# pc_badge_hrv.net
KiCad netlist of a schematic drawn in EAGLE
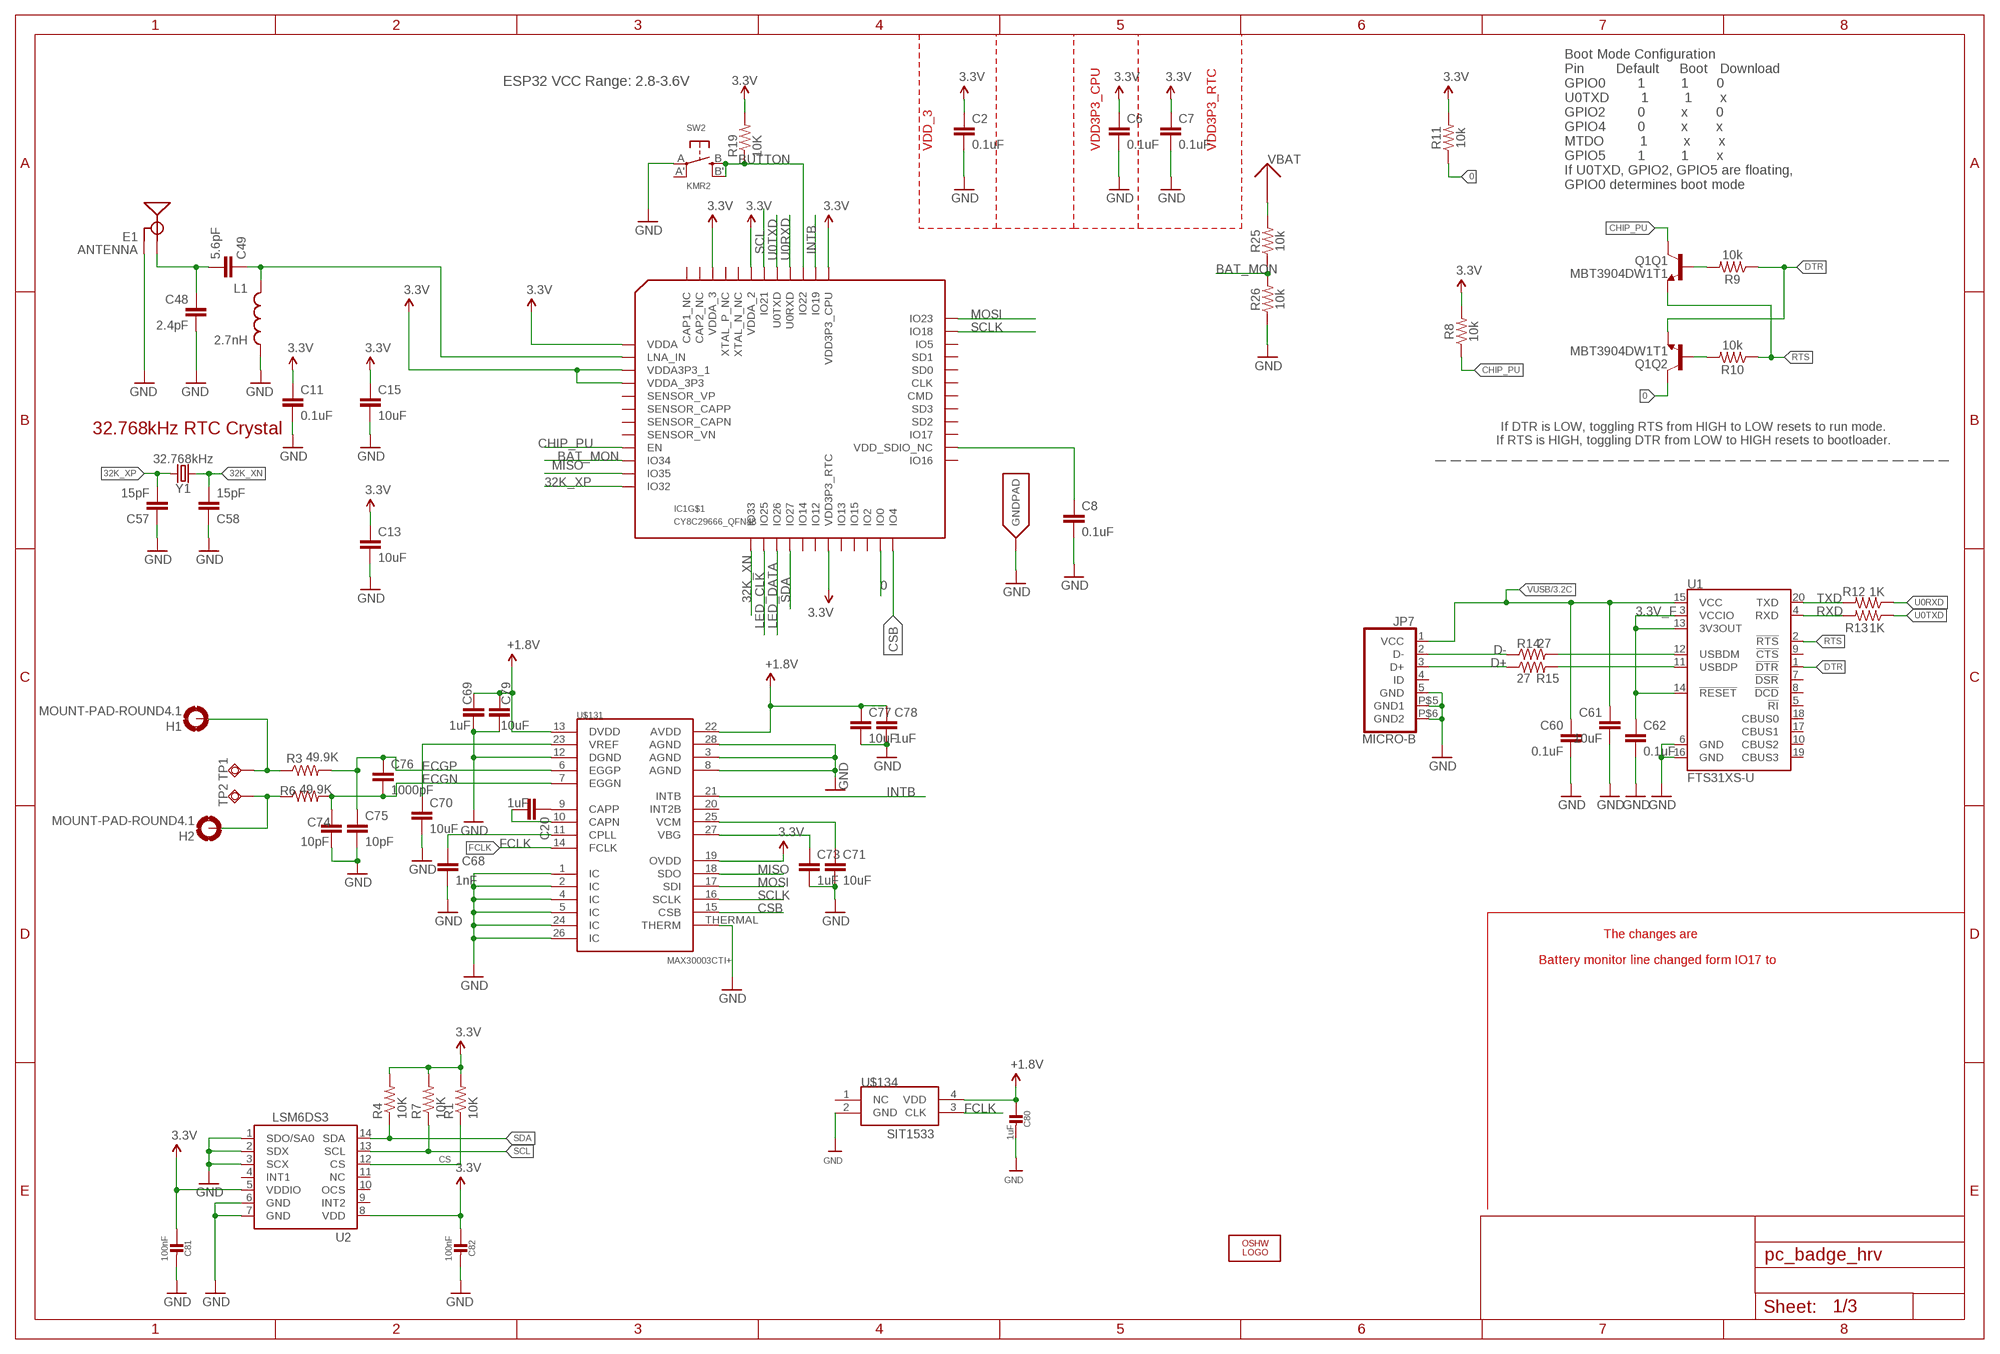
[diagram p0: schematic, sheet 1]
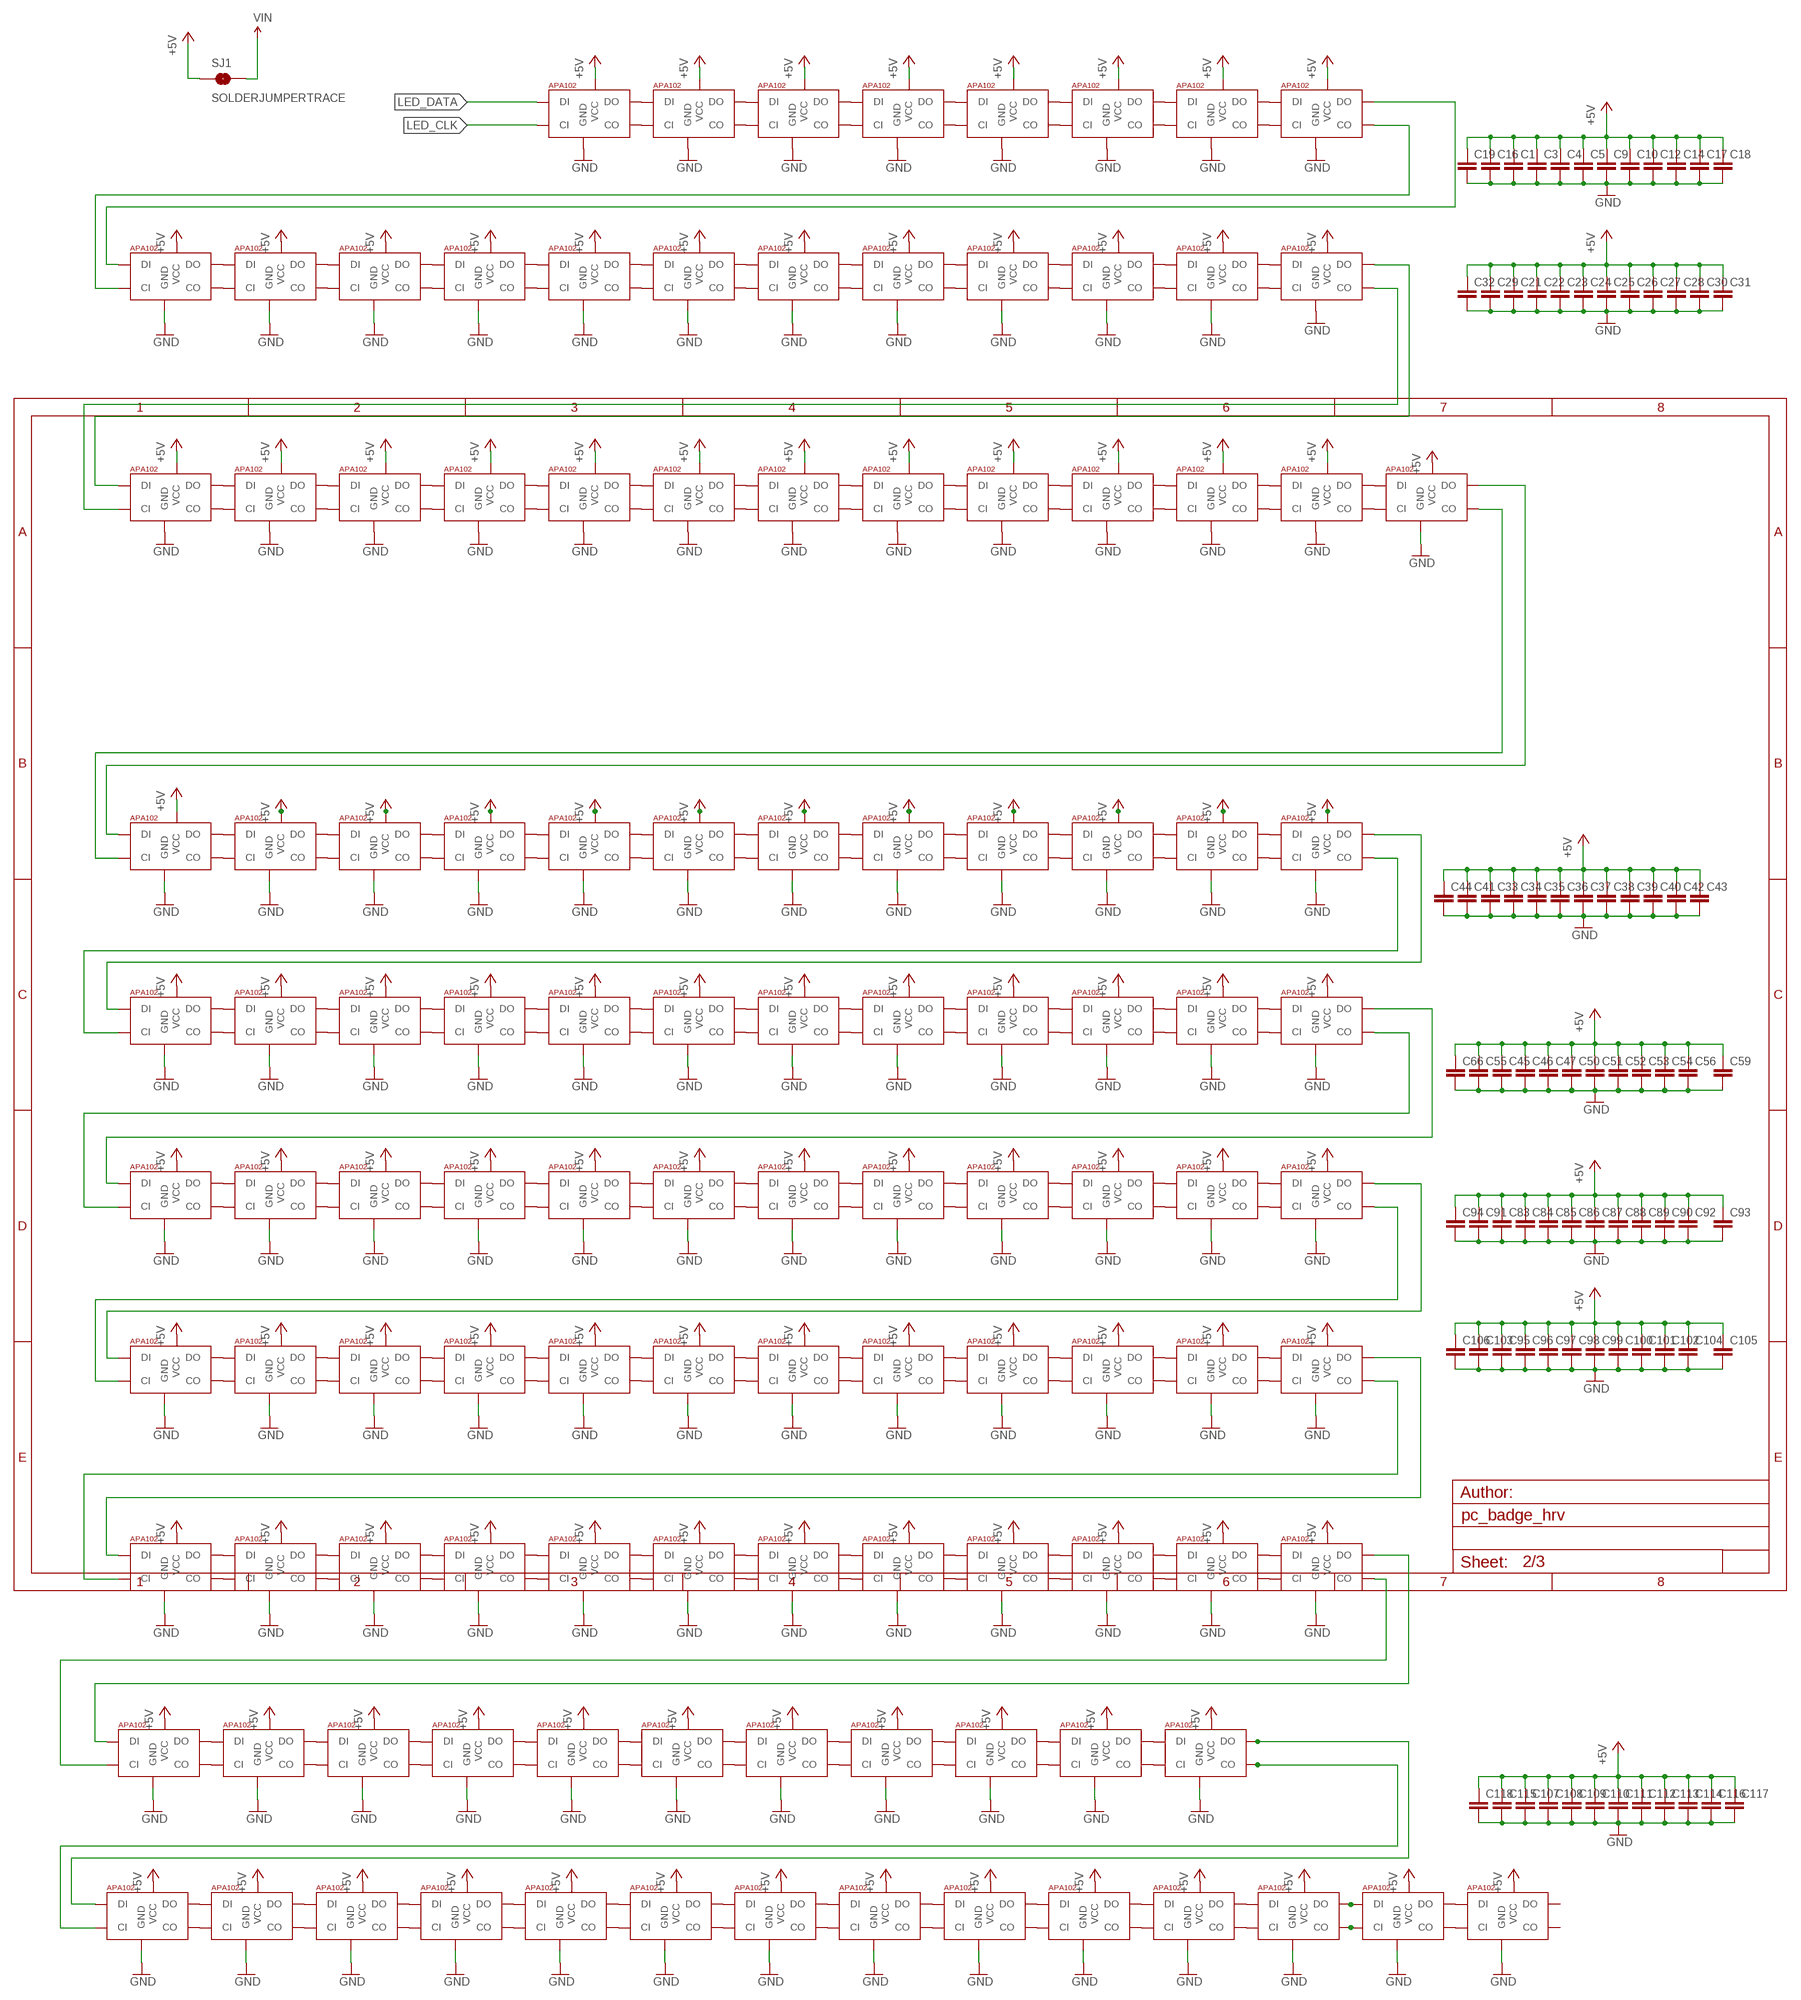
[diagram p1: schematic, sheet 2]
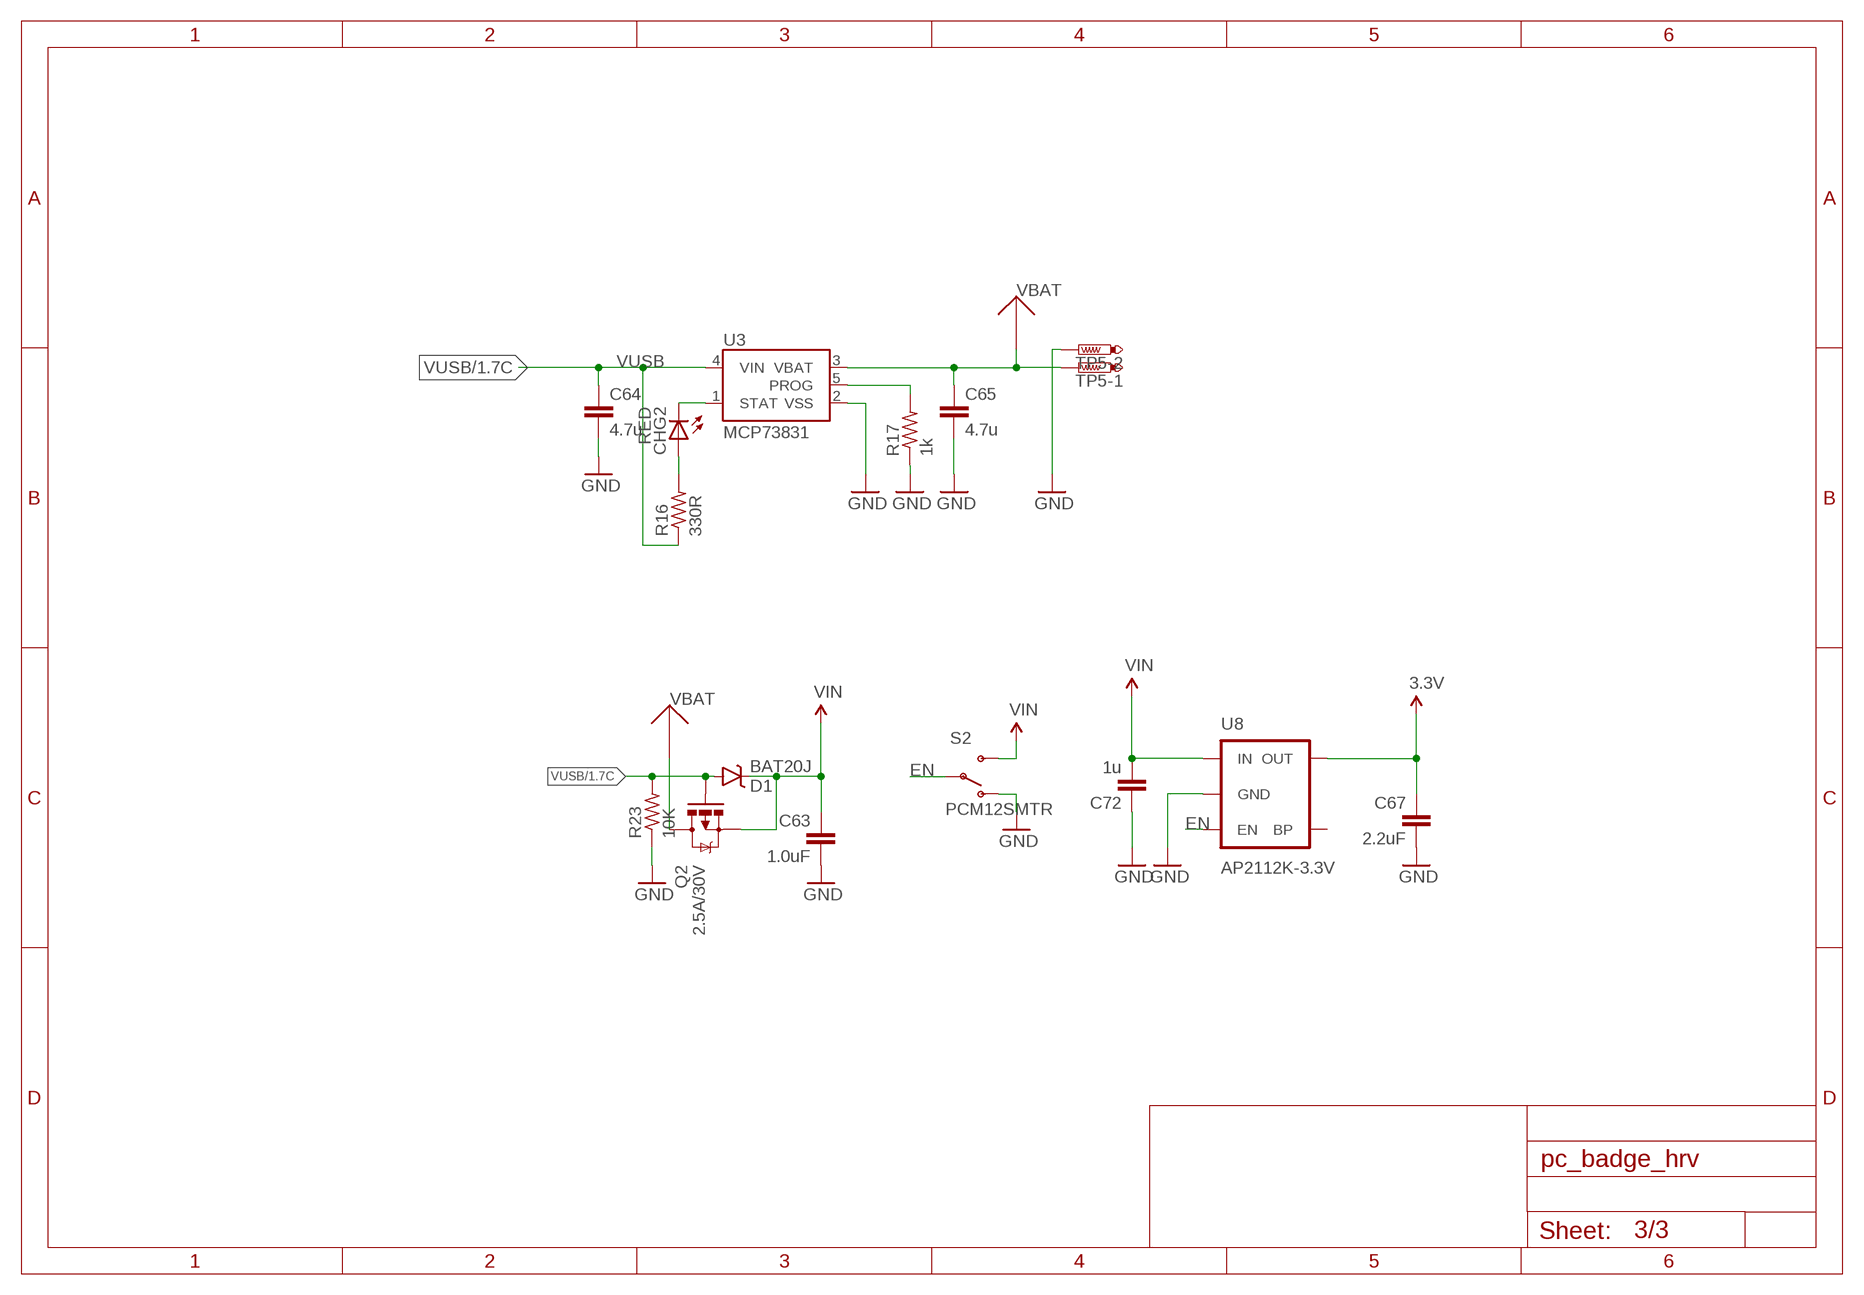
[diagram p2: schematic, sheet 3]

(export (version "E")
  (design (tool "Eeschema 10.0.6"))
  (components
    (comp (ref "C1")
      (value "C-EUC0402K")
      (footprint "eagle-import:C0402K")
      (libsource (lib "eagle-import") (part "C-EUC0402K"))
    )
    (comp (ref "C3")
      (value "C-EUC0402K")
      (footprint "eagle-import:C0402K")
      (libsource (lib "eagle-import") (part "C-EUC0402K"))
    )
    (comp (ref "C4")
      (value "C-EUC0402K")
      (footprint "eagle-import:C0402K")
      (libsource (lib "eagle-import") (part "C-EUC0402K"))
    )
    (comp (ref "C5")
      (value "C-EUC0402K")
      (footprint "eagle-import:C0402K")
      (libsource (lib "eagle-import") (part "C-EUC0402K"))
    )
    (comp (ref "C9")
      (value "C-EUC0402K")
      (footprint "eagle-import:C0402K")
      (libsource (lib "eagle-import") (part "C-EUC0402K"))
    )
    (comp (ref "C10")
      (value "C-EUC0402K")
      (footprint "eagle-import:C0402K")
      (libsource (lib "eagle-import") (part "C-EUC0402K"))
    )
    (comp (ref "C12")
      (value "C-EUC0402K")
      (footprint "eagle-import:C0402K")
      (libsource (lib "eagle-import") (part "C-EUC0402K"))
    )
    (comp (ref "C14")
      (value "C-EUC0402K")
      (footprint "eagle-import:C0402K")
      (libsource (lib "eagle-import") (part "C-EUC0402K"))
    )
    (comp (ref "C16")
      (value "C-EUC0402K")
      (footprint "eagle-import:C0402K")
      (libsource (lib "eagle-import") (part "C-EUC0402K"))
    )
    (comp (ref "C17")
      (value "C-EUC0402K")
      (footprint "eagle-import:C0402K")
      (libsource (lib "eagle-import") (part "C-EUC0402K"))
    )
    (comp (ref "C18")
      (value "C-EUC0402K")
      (footprint "eagle-import:C0402K")
      (libsource (lib "eagle-import") (part "C-EUC0402K"))
    )
    (comp (ref "C19")
      (value "C-EUC0402K")
      (footprint "eagle-import:C0402K")
      (libsource (lib "eagle-import") (part "C-EUC0402K"))
    )
    (comp (ref "C21")
      (value "C-EUC0402K")
      (footprint "eagle-import:C0402K")
      (libsource (lib "eagle-import") (part "C-EUC0402K"))
    )
    (comp (ref "C22")
      (value "C-EUC0402K")
      (footprint "eagle-import:C0402K")
      (libsource (lib "eagle-import") (part "C-EUC0402K"))
    )
    (comp (ref "C23")
      (value "C-EUC0402K")
      (footprint "eagle-import:C0402K")
      (libsource (lib "eagle-import") (part "C-EUC0402K"))
    )
    (comp (ref "C24")
      (value "C-EUC0402K")
      (footprint "eagle-import:C0402K")
      (libsource (lib "eagle-import") (part "C-EUC0402K"))
    )
    (comp (ref "C25")
      (value "C-EUC0402K")
      (footprint "eagle-import:C0402K")
      (libsource (lib "eagle-import") (part "C-EUC0402K"))
    )
    (comp (ref "C26")
      (value "C-EUC0402K")
      (footprint "eagle-import:C0402K")
      (libsource (lib "eagle-import") (part "C-EUC0402K"))
    )
    (comp (ref "C27")
      (value "C-EUC0402K")
      (footprint "eagle-import:C0402K")
      (libsource (lib "eagle-import") (part "C-EUC0402K"))
    )
    (comp (ref "C28")
      (value "C-EUC0402K")
      (footprint "eagle-import:C0402K")
      (libsource (lib "eagle-import") (part "C-EUC0402K"))
    )
    (comp (ref "C29")
      (value "C-EUC0402K")
      (footprint "eagle-import:C0402K")
      (libsource (lib "eagle-import") (part "C-EUC0402K"))
    )
    (comp (ref "C30")
      (value "C-EUC0402K")
      (footprint "eagle-import:C0402K")
      (libsource (lib "eagle-import") (part "C-EUC0402K"))
    )
    (comp (ref "C31")
      (value "C-EUC0402K")
      (footprint "eagle-import:C0402K")
      (libsource (lib "eagle-import") (part "C-EUC0402K"))
    )
    (comp (ref "C32")
      (value "C-EUC0402K")
      (footprint "eagle-import:C0402K")
      (libsource (lib "eagle-import") (part "C-EUC0402K"))
    )
    (comp (ref "C33")
      (value "C-EUC0402K")
      (footprint "eagle-import:C0402K")
      (libsource (lib "eagle-import") (part "C-EUC0402K"))
    )
    (comp (ref "C34")
      (value "C-EUC0402K")
      (footprint "eagle-import:C0402K")
      (libsource (lib "eagle-import") (part "C-EUC0402K"))
    )
    (comp (ref "C35")
      (value "C-EUC0402K")
      (footprint "eagle-import:C0402K")
      (libsource (lib "eagle-import") (part "C-EUC0402K"))
    )
    (comp (ref "C36")
      (value "C-EUC0402K")
      (footprint "eagle-import:C0402K")
      (libsource (lib "eagle-import") (part "C-EUC0402K"))
    )
    (comp (ref "C37")
      (value "C-EUC0402K")
      (footprint "eagle-import:C0402K")
      (libsource (lib "eagle-import") (part "C-EUC0402K"))
    )
    (comp (ref "C38")
      (value "C-EUC0402K")
      (footprint "eagle-import:C0402K")
      (libsource (lib "eagle-import") (part "C-EUC0402K"))
    )
    (comp (ref "C39")
      (value "C-EUC0402K")
      (footprint "eagle-import:C0402K")
      (libsource (lib "eagle-import") (part "C-EUC0402K"))
    )
    (comp (ref "C40")
      (value "C-EUC0402K")
      (footprint "eagle-import:C0402K")
      (libsource (lib "eagle-import") (part "C-EUC0402K"))
    )
    (comp (ref "C41")
      (value "C-EUC0402K")
      (footprint "eagle-import:C0402K")
      (libsource (lib "eagle-import") (part "C-EUC0402K"))
    )
    (comp (ref "C42")
      (value "C-EUC0402K")
      (footprint "eagle-import:C0402K")
      (libsource (lib "eagle-import") (part "C-EUC0402K"))
    )
    (comp (ref "C43")
      (value "C-EUC0402K")
      (footprint "eagle-import:C0402K")
      (libsource (lib "eagle-import") (part "C-EUC0402K"))
    )
    (comp (ref "C44")
      (value "C-EUC0402K")
      (footprint "eagle-import:C0402K")
      (libsource (lib "eagle-import") (part "C-EUC0402K"))
    )
    (comp (ref "C45")
      (value "C-EUC0402K")
      (footprint "eagle-import:C0402K")
      (libsource (lib "eagle-import") (part "C-EUC0402K"))
    )
    (comp (ref "C46")
      (value "C-EUC0402K")
      (footprint "eagle-import:C0402K")
      (libsource (lib "eagle-import") (part "C-EUC0402K"))
    )
    (comp (ref "C47")
      (value "C-EUC0402K")
      (footprint "eagle-import:C0402K")
      (libsource (lib "eagle-import") (part "C-EUC0402K"))
    )
    (comp (ref "C50")
      (value "C-EUC0402K")
      (footprint "eagle-import:C0402K")
      (libsource (lib "eagle-import") (part "C-EUC0402K"))
    )
    (comp (ref "C51")
      (value "C-EUC0402K")
      (footprint "eagle-import:C0402K")
      (libsource (lib "eagle-import") (part "C-EUC0402K"))
    )
    (comp (ref "C52")
      (value "C-EUC0402K")
      (footprint "eagle-import:C0402K")
      (libsource (lib "eagle-import") (part "C-EUC0402K"))
    )
    (comp (ref "C53")
      (value "C-EUC0402K")
      (footprint "eagle-import:C0402K")
      (libsource (lib "eagle-import") (part "C-EUC0402K"))
    )
    (comp (ref "C54")
      (value "C-EUC0402K")
      (footprint "eagle-import:C0402K")
      (libsource (lib "eagle-import") (part "C-EUC0402K"))
    )
    (comp (ref "C55")
      (value "C-EUC0402K")
      (footprint "eagle-import:C0402K")
      (libsource (lib "eagle-import") (part "C-EUC0402K"))
    )
    (comp (ref "C56")
      (value "C-EUC0402K")
      (footprint "eagle-import:C0402K")
      (libsource (lib "eagle-import") (part "C-EUC0402K"))
    )
    (comp (ref "C59")
      (value "C-EUC0402K")
      (footprint "eagle-import:C0402K")
      (libsource (lib "eagle-import") (part "C-EUC0402K"))
    )
    (comp (ref "C66")
      (value "C-EUC0402K")
      (footprint "eagle-import:C0402K")
      (libsource (lib "eagle-import") (part "C-EUC0402K"))
    )
    (comp (ref "C83")
      (value "C-EUC0402K")
      (footprint "eagle-import:C0402K")
      (libsource (lib "eagle-import") (part "C-EUC0402K"))
    )
    (comp (ref "C84")
      (value "C-EUC0402K")
      (footprint "eagle-import:C0402K")
      (libsource (lib "eagle-import") (part "C-EUC0402K"))
    )
    (comp (ref "C85")
      (value "C-EUC0402K")
      (footprint "eagle-import:C0402K")
      (libsource (lib "eagle-import") (part "C-EUC0402K"))
    )
    (comp (ref "C86")
      (value "C-EUC0402K")
      (footprint "eagle-import:C0402K")
      (libsource (lib "eagle-import") (part "C-EUC0402K"))
    )
    (comp (ref "C87")
      (value "C-EUC0402K")
      (footprint "eagle-import:C0402K")
      (libsource (lib "eagle-import") (part "C-EUC0402K"))
    )
    (comp (ref "C88")
      (value "C-EUC0402K")
      (footprint "eagle-import:C0402K")
      (libsource (lib "eagle-import") (part "C-EUC0402K"))
    )
    (comp (ref "C89")
      (value "C-EUC0402K")
      (footprint "eagle-import:C0402K")
      (libsource (lib "eagle-import") (part "C-EUC0402K"))
    )
    (comp (ref "C90")
      (value "C-EUC0402K")
      (footprint "eagle-import:C0402K")
      (libsource (lib "eagle-import") (part "C-EUC0402K"))
    )
    (comp (ref "C91")
      (value "C-EUC0402K")
      (footprint "eagle-import:C0402K")
      (libsource (lib "eagle-import") (part "C-EUC0402K"))
    )
    (comp (ref "C92")
      (value "C-EUC0402K")
      (footprint "eagle-import:C0402K")
      (libsource (lib "eagle-import") (part "C-EUC0402K"))
    )
    (comp (ref "C93")
      (value "C-EUC0402K")
      (footprint "eagle-import:C0402K")
      (libsource (lib "eagle-import") (part "C-EUC0402K"))
    )
    (comp (ref "C94")
      (value "C-EUC0402K")
      (footprint "eagle-import:C0402K")
      (libsource (lib "eagle-import") (part "C-EUC0402K"))
    )
    (comp (ref "C95")
      (value "C-EUC0402K")
      (footprint "eagle-import:C0402K")
      (libsource (lib "eagle-import") (part "C-EUC0402K"))
    )
    (comp (ref "C96")
      (value "C-EUC0402K")
      (footprint "eagle-import:C0402K")
      (libsource (lib "eagle-import") (part "C-EUC0402K"))
    )
    (comp (ref "C97")
      (value "C-EUC0402K")
      (footprint "eagle-import:C0402K")
      (libsource (lib "eagle-import") (part "C-EUC0402K"))
    )
    (comp (ref "C98")
      (value "C-EUC0402K")
      (footprint "eagle-import:C0402K")
      (libsource (lib "eagle-import") (part "C-EUC0402K"))
    )
    (comp (ref "C99")
      (value "C-EUC0402K")
      (footprint "eagle-import:C0402K")
      (libsource (lib "eagle-import") (part "C-EUC0402K"))
    )
    (comp (ref "C100")
      (value "C-EUC0402K")
      (footprint "eagle-import:C0402K")
      (libsource (lib "eagle-import") (part "C-EUC0402K"))
    )
    (comp (ref "C101")
      (value "C-EUC0402K")
      (footprint "eagle-import:C0402K")
      (libsource (lib "eagle-import") (part "C-EUC0402K"))
    )
    (comp (ref "C102")
      (value "C-EUC0402K")
      (footprint "eagle-import:C0402K")
      (libsource (lib "eagle-import") (part "C-EUC0402K"))
    )
    (comp (ref "C103")
      (value "C-EUC0402K")
      (footprint "eagle-import:C0402K")
      (libsource (lib "eagle-import") (part "C-EUC0402K"))
    )
    (comp (ref "C104")
      (value "C-EUC0402K")
      (footprint "eagle-import:C0402K")
      (libsource (lib "eagle-import") (part "C-EUC0402K"))
    )
    (comp (ref "C105")
      (value "C-EUC0402K")
      (footprint "eagle-import:C0402K")
      (libsource (lib "eagle-import") (part "C-EUC0402K"))
    )
    (comp (ref "C106")
      (value "C-EUC0402K")
      (footprint "eagle-import:C0402K")
      (libsource (lib "eagle-import") (part "C-EUC0402K"))
    )
    (comp (ref "C107")
      (value "C-EUC0402K")
      (footprint "eagle-import:C0402K")
      (libsource (lib "eagle-import") (part "C-EUC0402K"))
    )
    (comp (ref "C108")
      (value "C-EUC0402K")
      (footprint "eagle-import:C0402K")
      (libsource (lib "eagle-import") (part "C-EUC0402K"))
    )
    (comp (ref "C109")
      (value "C-EUC0402K")
      (footprint "eagle-import:C0402K")
      (libsource (lib "eagle-import") (part "C-EUC0402K"))
    )
    (comp (ref "C110")
      (value "C-EUC0402K")
      (footprint "eagle-import:C0402K")
      (libsource (lib "eagle-import") (part "C-EUC0402K"))
    )
    (comp (ref "C111")
      (value "C-EUC0402K")
      (footprint "eagle-import:C0402K")
      (libsource (lib "eagle-import") (part "C-EUC0402K"))
    )
    (comp (ref "C112")
      (value "C-EUC0402K")
      (footprint "eagle-import:C0402K")
      (libsource (lib "eagle-import") (part "C-EUC0402K"))
    )
    (comp (ref "C113")
      (value "C-EUC0402K")
      (footprint "eagle-import:C0402K")
      (libsource (lib "eagle-import") (part "C-EUC0402K"))
    )
    (comp (ref "C114")
      (value "C-EUC0402K")
      (footprint "eagle-import:C0402K")
      (libsource (lib "eagle-import") (part "C-EUC0402K"))
    )
    (comp (ref "C115")
      (value "C-EUC0402K")
      (footprint "eagle-import:C0402K")
      (libsource (lib "eagle-import") (part "C-EUC0402K"))
    )
    (comp (ref "C116")
      (value "C-EUC0402K")
      (footprint "eagle-import:C0402K")
      (libsource (lib "eagle-import") (part "C-EUC0402K"))
    )
    (comp (ref "C117")
      (value "C-EUC0402K")
      (footprint "eagle-import:C0402K")
      (libsource (lib "eagle-import") (part "C-EUC0402K"))
    )
    (comp (ref "C118")
      (value "C-EUC0402K")
      (footprint "eagle-import:C0402K")
      (libsource (lib "eagle-import") (part "C-EUC0402K"))
    )
    (comp (ref "SJ1")
      (value "SOLDERJUMPERTRACE")
      (footprint "eagle-import:SJ_2S-TRACE")
      (libsource (lib "eagle-import") (part "SOLDERJUMPERTRACE"))
    )
    (comp (ref "U$9")
      (value "APA1022020")
      (footprint "eagle-import:APA102_2020")
      (libsource (lib "eagle-import") (part "APA1022020"))
    )
    (comp (ref "U$10")
      (value "APA1022020")
      (footprint "eagle-import:APA102_2020")
      (libsource (lib "eagle-import") (part "APA1022020"))
    )
    (comp (ref "U$11")
      (value "APA1022020")
      (footprint "eagle-import:APA102_2020")
      (libsource (lib "eagle-import") (part "APA1022020"))
    )
    (comp (ref "U$12")
      (value "APA1022020")
      (footprint "eagle-import:APA102_2020")
      (libsource (lib "eagle-import") (part "APA1022020"))
    )
    (comp (ref "U$13")
      (value "APA1022020")
      (footprint "eagle-import:APA102_2020")
      (libsource (lib "eagle-import") (part "APA1022020"))
    )
    (comp (ref "U$14")
      (value "APA1022020")
      (footprint "eagle-import:APA102_2020")
      (libsource (lib "eagle-import") (part "APA1022020"))
    )
    (comp (ref "U$15")
      (value "APA1022020")
      (footprint "eagle-import:APA102_2020")
      (libsource (lib "eagle-import") (part "APA1022020"))
    )
    (comp (ref "U$18")
      (value "APA1022020")
      (footprint "eagle-import:APA102_2020")
      (libsource (lib "eagle-import") (part "APA1022020"))
    )
    (comp (ref "U$19")
      (value "APA1022020")
      (footprint "eagle-import:APA102_2020")
      (libsource (lib "eagle-import") (part "APA1022020"))
    )
    (comp (ref "U$20")
      (value "APA1022020")
      (footprint "eagle-import:APA102_2020")
      (libsource (lib "eagle-import") (part "APA1022020"))
    )
    (comp (ref "U$21")
      (value "APA1022020")
      (footprint "eagle-import:APA102_2020")
      (libsource (lib "eagle-import") (part "APA1022020"))
    )
    (comp (ref "U$22")
      (value "APA1022020")
      (footprint "eagle-import:APA102_2020")
      (libsource (lib "eagle-import") (part "APA1022020"))
    )
    (comp (ref "U$24")
      (value "APA1022020")
      (footprint "eagle-import:APA102_2020")
      (libsource (lib "eagle-import") (part "APA1022020"))
    )
    (comp (ref "U$25")
      (value "APA1022020")
      (footprint "eagle-import:APA102_2020")
      (libsource (lib "eagle-import") (part "APA1022020"))
    )
    (comp (ref "U$27")
      (value "APA1022020")
      (footprint "eagle-import:APA102_2020")
      (libsource (lib "eagle-import") (part "APA1022020"))
    )
    (comp (ref "U$28")
      (value "APA1022020")
      (footprint "eagle-import:APA102_2020")
      (libsource (lib "eagle-import") (part "APA1022020"))
    )
    (comp (ref "U$29")
      (value "APA1022020")
      (footprint "eagle-import:APA102_2020")
      (libsource (lib "eagle-import") (part "APA1022020"))
    )
    (comp (ref "U$30")
      (value "APA1022020")
      (footprint "eagle-import:APA102_2020")
      (libsource (lib "eagle-import") (part "APA1022020"))
    )
    (comp (ref "U$31")
      (value "APA1022020")
      (footprint "eagle-import:APA102_2020")
      (libsource (lib "eagle-import") (part "APA1022020"))
    )
    (comp (ref "U$32")
      (value "APA1022020")
      (footprint "eagle-import:APA102_2020")
      (libsource (lib "eagle-import") (part "APA1022020"))
    )
    (comp (ref "U$33")
      (value "APA1022020")
      (footprint "eagle-import:APA102_2020")
      (libsource (lib "eagle-import") (part "APA1022020"))
    )
    (comp (ref "U$34")
      (value "APA1022020")
      (footprint "eagle-import:APA102_2020")
      (libsource (lib "eagle-import") (part "APA1022020"))
    )
    (comp (ref "U$35")
      (value "APA1022020")
      (footprint "eagle-import:APA102_2020")
      (libsource (lib "eagle-import") (part "APA1022020"))
    )
    (comp (ref "U$36")
      (value "APA1022020")
      (footprint "eagle-import:APA102_2020")
      (libsource (lib "eagle-import") (part "APA1022020"))
    )
    (comp (ref "U$37")
      (value "APA1022020")
      (footprint "eagle-import:APA102_2020")
      (libsource (lib "eagle-import") (part "APA1022020"))
    )
    (comp (ref "U$38")
      (value "APA1022020")
      (footprint "eagle-import:APA102_2020")
      (libsource (lib "eagle-import") (part "APA1022020"))
    )
    (comp (ref "U$39")
      (value "APA1022020")
      (footprint "eagle-import:APA102_2020")
      (libsource (lib "eagle-import") (part "APA1022020"))
    )
    (comp (ref "U$40")
      (value "APA1022020")
      (footprint "eagle-import:APA102_2020")
      (libsource (lib "eagle-import") (part "APA1022020"))
    )
    (comp (ref "U$41")
      (value "APA1022020")
      (footprint "eagle-import:APA102_2020")
      (libsource (lib "eagle-import") (part "APA1022020"))
    )
    (comp (ref "U$42")
      (value "APA1022020")
      (footprint "eagle-import:APA102_2020")
      (libsource (lib "eagle-import") (part "APA1022020"))
    )
    (comp (ref "U$43")
      (value "APA1022020")
      (footprint "eagle-import:APA102_2020")
      (libsource (lib "eagle-import") (part "APA1022020"))
    )
    (comp (ref "U$44")
      (value "APA1022020")
      (footprint "eagle-import:APA102_2020")
      (libsource (lib "eagle-import") (part "APA1022020"))
    )
    (comp (ref "U$45")
      (value "APA1022020")
      (footprint "eagle-import:APA102_2020")
      (libsource (lib "eagle-import") (part "APA1022020"))
    )
    (comp (ref "U$46")
      (value "APA1022020")
      (footprint "eagle-import:APA102_2020")
      (libsource (lib "eagle-import") (part "APA1022020"))
    )
    (comp (ref "U$47")
      (value "APA1022020")
      (footprint "eagle-import:APA102_2020")
      (libsource (lib "eagle-import") (part "APA1022020"))
    )
    (comp (ref "U$48")
      (value "APA1022020")
      (footprint "eagle-import:APA102_2020")
      (libsource (lib "eagle-import") (part "APA1022020"))
    )
    (comp (ref "U$49")
      (value "APA1022020")
      (footprint "eagle-import:APA102_2020")
      (libsource (lib "eagle-import") (part "APA1022020"))
    )
    (comp (ref "U$50")
      (value "APA1022020")
      (footprint "eagle-import:APA102_2020")
      (libsource (lib "eagle-import") (part "APA1022020"))
    )
    (comp (ref "U$51")
      (value "APA1022020")
      (footprint "eagle-import:APA102_2020")
      (libsource (lib "eagle-import") (part "APA1022020"))
    )
    (comp (ref "U$52")
      (value "APA1022020")
      (footprint "eagle-import:APA102_2020")
      (libsource (lib "eagle-import") (part "APA1022020"))
    )
    (comp (ref "U$53")
      (value "APA1022020")
      (footprint "eagle-import:APA102_2020")
      (libsource (lib "eagle-import") (part "APA1022020"))
    )
    (comp (ref "U$54")
      (value "APA1022020")
      (footprint "eagle-import:APA102_2020")
      (libsource (lib "eagle-import") (part "APA1022020"))
    )
    (comp (ref "U$55")
      (value "APA1022020")
      (footprint "eagle-import:APA102_2020")
      (libsource (lib "eagle-import") (part "APA1022020"))
    )
    (comp (ref "U$56")
      (value "APA1022020")
      (footprint "eagle-import:APA102_2020")
      (libsource (lib "eagle-import") (part "APA1022020"))
    )
    (comp (ref "U$57")
      (value "APA1022020")
      (footprint "eagle-import:APA102_2020")
      (libsource (lib "eagle-import") (part "APA1022020"))
    )
    (comp (ref "U$58")
      (value "APA1022020")
      (footprint "eagle-import:APA102_2020")
      (libsource (lib "eagle-import") (part "APA1022020"))
    )
    (comp (ref "U$59")
      (value "APA1022020")
      (footprint "eagle-import:APA102_2020")
      (libsource (lib "eagle-import") (part "APA1022020"))
    )
    (comp (ref "U$60")
      (value "APA1022020")
      (footprint "eagle-import:APA102_2020")
      (libsource (lib "eagle-import") (part "APA1022020"))
    )
    (comp (ref "U$61")
      (value "APA1022020")
      (footprint "eagle-import:APA102_2020")
      (libsource (lib "eagle-import") (part "APA1022020"))
    )
    (comp (ref "U$62")
      (value "APA1022020")
      (footprint "eagle-import:APA102_2020")
      (libsource (lib "eagle-import") (part "APA1022020"))
    )
    (comp (ref "U$63")
      (value "APA1022020")
      (footprint "eagle-import:APA102_2020")
      (libsource (lib "eagle-import") (part "APA1022020"))
    )
    (comp (ref "U$64")
      (value "APA1022020")
      (footprint "eagle-import:APA102_2020")
      (libsource (lib "eagle-import") (part "APA1022020"))
    )
    (comp (ref "U$65")
      (value "APA1022020")
      (footprint "eagle-import:APA102_2020")
      (libsource (lib "eagle-import") (part "APA1022020"))
    )
    (comp (ref "U$66")
      (value "APA1022020")
      (footprint "eagle-import:APA102_2020")
      (libsource (lib "eagle-import") (part "APA1022020"))
    )
    (comp (ref "U$67")
      (value "APA1022020")
      (footprint "eagle-import:APA102_2020")
      (libsource (lib "eagle-import") (part "APA1022020"))
    )
    (comp (ref "U$68")
      (value "APA1022020")
      (footprint "eagle-import:APA102_2020")
      (libsource (lib "eagle-import") (part "APA1022020"))
    )
    (comp (ref "U$69")
      (value "APA1022020")
      (footprint "eagle-import:APA102_2020")
      (libsource (lib "eagle-import") (part "APA1022020"))
    )
    (comp (ref "U$70")
      (value "APA1022020")
      (footprint "eagle-import:APA102_2020")
      (libsource (lib "eagle-import") (part "APA1022020"))
    )
    (comp (ref "U$71")
      (value "APA1022020")
      (footprint "eagle-import:APA102_2020")
      (libsource (lib "eagle-import") (part "APA1022020"))
    )
    (comp (ref "U$72")
      (value "APA1022020")
      (footprint "eagle-import:APA102_2020")
      (libsource (lib "eagle-import") (part "APA1022020"))
    )
    (comp (ref "U$73")
      (value "APA1022020")
      (footprint "eagle-import:APA102_2020")
      (libsource (lib "eagle-import") (part "APA1022020"))
    )
    (comp (ref "U$74")
      (value "APA1022020")
      (footprint "eagle-import:APA102_2020")
      (libsource (lib "eagle-import") (part "APA1022020"))
    )
    (comp (ref "U$75")
      (value "APA1022020")
      (footprint "eagle-import:APA102_2020")
      (libsource (lib "eagle-import") (part "APA1022020"))
    )
    (comp (ref "U$76")
      (value "APA1022020")
      (footprint "eagle-import:APA102_2020")
      (libsource (lib "eagle-import") (part "APA1022020"))
    )
    (comp (ref "U$77")
      (value "APA1022020")
      (footprint "eagle-import:APA102_2020")
      (libsource (lib "eagle-import") (part "APA1022020"))
    )
    (comp (ref "U$78")
      (value "APA1022020")
      (footprint "eagle-import:APA102_2020")
      (libsource (lib "eagle-import") (part "APA1022020"))
    )
    (comp (ref "U$79")
      (value "APA1022020")
      (footprint "eagle-import:APA102_2020")
      (libsource (lib "eagle-import") (part "APA1022020"))
    )
    (comp (ref "U$80")
      (value "APA1022020")
      (footprint "eagle-import:APA102_2020")
      (libsource (lib "eagle-import") (part "APA1022020"))
    )
    (comp (ref "U$81")
      (value "APA1022020")
      (footprint "eagle-import:APA102_2020")
      (libsource (lib "eagle-import") (part "APA1022020"))
    )
    (comp (ref "U$82")
      (value "APA1022020")
      (footprint "eagle-import:APA102_2020")
      (libsource (lib "eagle-import") (part "APA1022020"))
    )
    (comp (ref "U$83")
      (value "APA1022020")
      (footprint "eagle-import:APA102_2020")
      (libsource (lib "eagle-import") (part "APA1022020"))
    )
    (comp (ref "U$84")
      (value "APA1022020")
      (footprint "eagle-import:APA102_2020")
      (libsource (lib "eagle-import") (part "APA1022020"))
    )
    (comp (ref "U$85")
      (value "APA1022020")
      (footprint "eagle-import:APA102_2020")
      (libsource (lib "eagle-import") (part "APA1022020"))
    )
    (comp (ref "U$86")
      (value "APA1022020")
      (footprint "eagle-import:APA102_2020")
      (libsource (lib "eagle-import") (part "APA1022020"))
    )
    (comp (ref "U$87")
      (value "APA1022020")
      (footprint "eagle-import:APA102_2020")
      (libsource (lib "eagle-import") (part "APA1022020"))
    )
    (comp (ref "U$88")
      (value "APA1022020")
      (footprint "eagle-import:APA102_2020")
      (libsource (lib "eagle-import") (part "APA1022020"))
    )
    (comp (ref "U$89")
      (value "APA1022020")
      (footprint "eagle-import:APA102_2020")
      (libsource (lib "eagle-import") (part "APA1022020"))
    )
    (comp (ref "U$90")
      (value "APA1022020")
      (footprint "eagle-import:APA102_2020")
      (libsource (lib "eagle-import") (part "APA1022020"))
    )
    (comp (ref "U$91")
      (value "APA1022020")
      (footprint "eagle-import:APA102_2020")
      (libsource (lib "eagle-import") (part "APA1022020"))
    )
    (comp (ref "U$92")
      (value "APA1022020")
      (footprint "eagle-import:APA102_2020")
      (libsource (lib "eagle-import") (part "APA1022020"))
    )
    (comp (ref "U$93")
      (value "APA1022020")
      (footprint "eagle-import:APA102_2020")
      (libsource (lib "eagle-import") (part "APA1022020"))
    )
    (comp (ref "U$94")
      (value "APA1022020")
      (footprint "eagle-import:APA102_2020")
      (libsource (lib "eagle-import") (part "APA1022020"))
    )
    (comp (ref "U$95")
      (value "APA1022020")
      (footprint "eagle-import:APA102_2020")
      (libsource (lib "eagle-import") (part "APA1022020"))
    )
    (comp (ref "U$96")
      (value "APA1022020")
      (footprint "eagle-import:APA102_2020")
      (libsource (lib "eagle-import") (part "APA1022020"))
    )
    (comp (ref "U$97")
      (value "APA1022020")
      (footprint "eagle-import:APA102_2020")
      (libsource (lib "eagle-import") (part "APA1022020"))
    )
    (comp (ref "U$98")
      (value "APA1022020")
      (footprint "eagle-import:APA102_2020")
      (libsource (lib "eagle-import") (part "APA1022020"))
    )
    (comp (ref "U$99")
      (value "APA1022020")
      (footprint "eagle-import:APA102_2020")
      (libsource (lib "eagle-import") (part "APA1022020"))
    )
    (comp (ref "U$100")
      (value "APA1022020")
      (footprint "eagle-import:APA102_2020")
      (libsource (lib "eagle-import") (part "APA1022020"))
    )
    (comp (ref "U$101")
      (value "APA1022020")
      (footprint "eagle-import:APA102_2020")
      (libsource (lib "eagle-import") (part "APA1022020"))
    )
    (comp (ref "U$102")
      (value "APA1022020")
      (footprint "eagle-import:APA102_2020")
      (libsource (lib "eagle-import") (part "APA1022020"))
    )
    (comp (ref "U$103")
      (value "APA1022020")
      (footprint "eagle-import:APA102_2020")
      (libsource (lib "eagle-import") (part "APA1022020"))
    )
    (comp (ref "U$104")
      (value "APA1022020")
      (footprint "eagle-import:APA102_2020")
      (libsource (lib "eagle-import") (part "APA1022020"))
    )
    (comp (ref "U$105")
      (value "APA1022020")
      (footprint "eagle-import:APA102_2020")
      (libsource (lib "eagle-import") (part "APA1022020"))
    )
    (comp (ref "U$106")
      (value "APA1022020")
      (footprint "eagle-import:APA102_2020")
      (libsource (lib "eagle-import") (part "APA1022020"))
    )
    (comp (ref "U$107")
      (value "APA1022020")
      (footprint "eagle-import:APA102_2020")
      (libsource (lib "eagle-import") (part "APA1022020"))
    )
    (comp (ref "U$108")
      (value "APA1022020")
      (footprint "eagle-import:APA102_2020")
      (libsource (lib "eagle-import") (part "APA1022020"))
    )
    (comp (ref "U$109")
      (value "APA1022020")
      (footprint "eagle-import:APA102_2020")
      (libsource (lib "eagle-import") (part "APA1022020"))
    )
    (comp (ref "U$110")
      (value "APA1022020")
      (footprint "eagle-import:APA102_2020")
      (libsource (lib "eagle-import") (part "APA1022020"))
    )
    (comp (ref "U$111")
      (value "APA1022020")
      (footprint "eagle-import:APA102_2020")
      (libsource (lib "eagle-import") (part "APA1022020"))
    )
    (comp (ref "U$112")
      (value "APA1022020")
      (footprint "eagle-import:APA102_2020")
      (libsource (lib "eagle-import") (part "APA1022020"))
    )
    (comp (ref "U$113")
      (value "APA1022020")
      (footprint "eagle-import:APA102_2020")
      (libsource (lib "eagle-import") (part "APA1022020"))
    )
    (comp (ref "U$114")
      (value "APA1022020")
      (footprint "eagle-import:APA102_2020")
      (libsource (lib "eagle-import") (part "APA1022020"))
    )
    (comp (ref "U$115")
      (value "APA1022020")
      (footprint "eagle-import:APA102_2020")
      (libsource (lib "eagle-import") (part "APA1022020"))
    )
    (comp (ref "U$116")
      (value "APA1022020")
      (footprint "eagle-import:APA102_2020")
      (libsource (lib "eagle-import") (part "APA1022020"))
    )
    (comp (ref "U$117")
      (value "APA1022020")
      (footprint "eagle-import:APA102_2020")
      (libsource (lib "eagle-import") (part "APA1022020"))
    )
    (comp (ref "U$118")
      (value "APA1022020")
      (footprint "eagle-import:APA102_2020")
      (libsource (lib "eagle-import") (part "APA1022020"))
    )
    (comp (ref "U$119")
      (value "APA1022020")
      (footprint "eagle-import:APA102_2020")
      (libsource (lib "eagle-import") (part "APA1022020"))
    )
    (comp (ref "U$120")
      (value "APA1022020")
      (footprint "eagle-import:APA102_2020")
      (libsource (lib "eagle-import") (part "APA1022020"))
    )
    (comp (ref "U$121")
      (value "APA1022020")
      (footprint "eagle-import:APA102_2020")
      (libsource (lib "eagle-import") (part "APA1022020"))
    )
    (comp (ref "U$122")
      (value "APA1022020")
      (footprint "eagle-import:APA102_2020")
      (libsource (lib "eagle-import") (part "APA1022020"))
    )
    (comp (ref "U$123")
      (value "APA1022020")
      (footprint "eagle-import:APA102_2020")
      (libsource (lib "eagle-import") (part "APA1022020"))
    )
    (comp (ref "U$124")
      (value "APA1022020")
      (footprint "eagle-import:APA102_2020")
      (libsource (lib "eagle-import") (part "APA1022020"))
    )
    (comp (ref "U$125")
      (value "APA1022020")
      (footprint "eagle-import:APA102_2020")
      (libsource (lib "eagle-import") (part "APA1022020"))
    )
    (comp (ref "U$126")
      (value "APA1022020")
      (footprint "eagle-import:APA102_2020")
      (libsource (lib "eagle-import") (part "APA1022020"))
    )
    (comp (ref "U$127")
      (value "APA1022020")
      (footprint "eagle-import:APA102_2020")
      (libsource (lib "eagle-import") (part "APA1022020"))
    )
    (comp (ref "U$128")
      (value "APA1022020")
      (footprint "eagle-import:APA102_2020")
      (libsource (lib "eagle-import") (part "APA1022020"))
    )
    (comp (ref "U$129")
      (value "APA1022020")
      (footprint "eagle-import:APA102_2020")
      (libsource (lib "eagle-import") (part "APA1022020"))
    )
    (comp (ref "U$130")
      (value "APA1022020")
      (footprint "eagle-import:APA102_2020")
      (libsource (lib "eagle-import") (part "APA1022020"))
    )
    (comp (ref "C2")
      (value "0.1uF")
      (footprint "eagle-import:0402")
      (libsource (lib "eagle-import") (part "0.1UF-0402-16V-10%"))
    )
    (comp (ref "C6")
      (value "0.1uF")
      (footprint "eagle-import:0402")
      (libsource (lib "eagle-import") (part "0.1UF-0402-16V-10%"))
    )
    (comp (ref "C7")
      (value "0.1uF")
      (footprint "eagle-import:0402")
      (libsource (lib "eagle-import") (part "0.1UF-0402-16V-10%"))
    )
    (comp (ref "C8")
      (value "0.1uF")
      (footprint "eagle-import:0402")
      (libsource (lib "eagle-import") (part "0.1UF-0402-16V-10%"))
    )
    (comp (ref "C11")
      (value "0.1uF")
      (footprint "eagle-import:0402")
      (libsource (lib "eagle-import") (part "0.1UF-0402-16V-10%"))
    )
    (comp (ref "C13")
      (value "10uF")
      (footprint "eagle-import:0603")
      (libsource (lib "eagle-import") (part "10UF-0603-6.3V-20%"))
    )
    (comp (ref "C15")
      (value "10uF")
      (footprint "eagle-import:0603")
      (libsource (lib "eagle-import") (part "10UF-0603-6.3V-20%"))
    )
    (comp (ref "C20")
      (value "1uF")
      (footprint "eagle-import:C0402")
      (libsource (lib "eagle-import") (part "C-EUC0402"))
    )
    (comp (ref "C48")
      (value "2.4pF")
      (footprint "eagle-import:0603")
      (libsource (lib "eagle-import") (part "2.4PF-0603-50V-5%"))
    )
    (comp (ref "C49")
      (value "5.6pF")
      (footprint "eagle-import:0603")
      (libsource (lib "eagle-import") (part "5.6PF-50V-5%(0603)"))
    )
    (comp (ref "C57")
      (value "15pF")
      (footprint "eagle-import:0603")
      (libsource (lib "eagle-import") (part "15PF-0603-50V-5%"))
    )
    (comp (ref "C58")
      (value "15pF")
      (footprint "eagle-import:0603")
      (libsource (lib "eagle-import") (part "15PF-0603-50V-5%"))
    )
    (comp (ref "C60")
      (value "0.1uF")
      (footprint "eagle-import:C0402")
      (libsource (lib "eagle-import") (part "C-EUC0402"))
    )
    (comp (ref "C61")
      (value "10uF")
      (footprint "eagle-import:C0805")
      (libsource (lib "eagle-import") (part "C-EUC0805"))
    )
    (comp (ref "C62")
      (value "0.1uF")
      (footprint "eagle-import:C0402")
      (libsource (lib "eagle-import") (part "C-EUC0402"))
    )
    (comp (ref "C68")
      (value "1nF")
      (footprint "eagle-import:C0402")
      (libsource (lib "eagle-import") (part "C-EUC0402"))
    )
    (comp (ref "C69")
      (value "1uF")
      (footprint "eagle-import:C0402")
      (libsource (lib "eagle-import") (part "C-EUC0402"))
    )
    (comp (ref "C70")
      (value "10uF")
      (footprint "eagle-import:C0402")
      (libsource (lib "eagle-import") (part "C-EUC0402"))
    )
    (comp (ref "C71")
      (value "10uF")
      (footprint "eagle-import:C0402")
      (libsource (lib "eagle-import") (part "C-EUC0402"))
    )
    (comp (ref "C73")
      (value "1uF")
      (footprint "eagle-import:C0402")
      (libsource (lib "eagle-import") (part "C-EUC0402"))
    )
    (comp (ref "C74")
      (value "10pF")
      (footprint "eagle-import:C0402")
      (libsource (lib "eagle-import") (part "C-EUC0402"))
    )
    (comp (ref "C75")
      (value "10pF")
      (footprint "eagle-import:C0402")
      (libsource (lib "eagle-import") (part "C-EUC0402"))
    )
    (comp (ref "C76")
      (value "1000pF")
      (footprint "eagle-import:C0402")
      (libsource (lib "eagle-import") (part "C-EUC0402"))
    )
    (comp (ref "C77")
      (value "10uF")
      (footprint "eagle-import:C0402")
      (libsource (lib "eagle-import") (part "C-EUC0402"))
    )
    (comp (ref "C78")
      (value "1uF")
      (footprint "eagle-import:C0402")
      (libsource (lib "eagle-import") (part "C-EUC0402"))
    )
    (comp (ref "C79")
      (value "10uF")
      (footprint "eagle-import:C0402")
      (libsource (lib "eagle-import") (part "C-EUC0402"))
    )
    (comp (ref "C80")
      (value "1uF")
      (footprint "eagle-import:_0402")
      (libsource (lib "eagle-import") (part "CAP_CERAMIC_0402"))
    )
    (comp (ref "C81")
      (value "100nF")
      (footprint "eagle-import:_0402")
      (libsource (lib "eagle-import") (part "CAP_CERAMIC_0402"))
    )
    (comp (ref "C82")
      (value "100nF")
      (footprint "eagle-import:_0402")
      (libsource (lib "eagle-import") (part "CAP_CERAMIC_0402"))
    )
    (comp (ref "E1")
      (value "ANTENNA")
      (footprint "eagle-import:TRACE_ANTENNA_2.4GHZ_25.7MM_TUNED")
      (libsource (lib "eagle-import") (part "ANTENNATRACE-TUNED"))
    )
    (comp (ref "H1")
      (value "MOUNT-PAD-ROUND4.1")
      (footprint "eagle-import:4,1-PAD")
      (libsource (lib "eagle-import") (part "MOUNT-PAD-ROUND4.1"))
    )
    (comp (ref "H2")
      (value "MOUNT-PAD-ROUND4.1")
      (footprint "eagle-import:4,1-PAD")
      (libsource (lib "eagle-import") (part "MOUNT-PAD-ROUND4.1"))
    )
    (comp (ref "IC1")
      (value "CY8C29666_QFN48")
      (footprint "eagle-import:QFN48")
      (libsource (lib "eagle-import") (part "CY8C29666_QFN48"))
    )
    (comp (ref "JP7")
      (value "MICRO-B")
      (footprint "eagle-import:MICRO-B")
      (libsource (lib "eagle-import") (part "MICRO-B"))
    )
    (comp (ref "L1")
      (value "2.7nH")
      (footprint "eagle-import:0603")
      (libsource (lib "eagle-import") (part "INDUCTOR0603"))
    )
    (comp (ref "LOGO3")
      (value "OSHW_LOGO_FILLX0200-NT")
      (footprint "eagle-import:OSHW_FILLX200_NOTEXT")
      (libsource (lib "eagle-import") (part "OSHW_LOGO_FILLX0200-NT"))
    )
    (comp (ref "Q1")
      (value "MBT3904DW1T1")
      (footprint "eagle-import:SC70-6")
      (libsource (lib "eagle-import") (part "MBT3904DW1T1"))
    )
    (comp (ref "R1")
      (value "10K")
      (footprint "eagle-import:0402-RES")
      (libsource (lib "eagle-import") (part "RESISTOR0402-RES"))
    )
    (comp (ref "R3")
      (value "49.9K")
      (footprint "eagle-import:0402-RES")
      (libsource (lib "eagle-import") (part "RESISTOR0402-RES"))
    )
    (comp (ref "R4")
      (value "10K")
      (footprint "eagle-import:0402-RES")
      (libsource (lib "eagle-import") (part "RESISTOR0402-RES"))
    )
    (comp (ref "R6")
      (value "49.9K")
      (footprint "eagle-import:0402-RES")
      (libsource (lib "eagle-import") (part "RESISTOR0402-RES"))
    )
    (comp (ref "R7")
      (value "10K")
      (footprint "eagle-import:0402-RES")
      (libsource (lib "eagle-import") (part "RESISTOR0402-RES"))
    )
    (comp (ref "R8")
      (value "10k")
      (footprint "eagle-import:0603")
      (libsource (lib "eagle-import") (part "10KOHM-1/10W-1%(0603)0603"))
    )
    (comp (ref "R9")
      (value "10k")
      (footprint "eagle-import:0603")
      (libsource (lib "eagle-import") (part "10KOHM-0603-1/10W-1%"))
    )
    (comp (ref "R10")
      (value "10k")
      (footprint "eagle-import:0603")
      (libsource (lib "eagle-import") (part "10KOHM-0603-1/10W-1%"))
    )
    (comp (ref "R11")
      (value "10k")
      (footprint "eagle-import:0603")
      (libsource (lib "eagle-import") (part "10KOHM-1/10W-1%(0603)0603"))
    )
    (comp (ref "R12")
      (value "1K")
      (footprint "eagle-import:R0402")
      (libsource (lib "eagle-import") (part "R-US_R0402"))
    )
    (comp (ref "R13")
      (value "1K")
      (footprint "eagle-import:R0402")
      (libsource (lib "eagle-import") (part "R-US_R0402"))
    )
    (comp (ref "R14")
      (value "27")
      (footprint "eagle-import:R0402")
      (libsource (lib "eagle-import") (part "R-US_R0402"))
    )
    (comp (ref "R15")
      (value "27")
      (footprint "eagle-import:R0402")
      (libsource (lib "eagle-import") (part "R-US_R0402"))
    )
    (comp (ref "R19")
      (value "10K")
      (footprint "eagle-import:R0402")
      (libsource (lib "eagle-import") (part "R-US_R0402"))
    )
    (comp (ref "R25")
      (value "10k")
      (footprint "eagle-import:0603")
      (libsource (lib "eagle-import") (part "10KOHM-1/10W-1%(0603)0603"))
    )
    (comp (ref "R26")
      (value "10k")
      (footprint "eagle-import:0603")
      (libsource (lib "eagle-import") (part "10KOHM-1/10W-1%(0603)0603"))
    )
    (comp (ref "SW2")
      (value "KMR2")
      (footprint "eagle-import:BTN_KMR2_4.6X2.8")
      (libsource (lib "eagle-import") (part "SWITCH_TACT_SMT4.6X2.8"))
    )
    (comp (ref "TP1")
      (value "TPSQTP11R")
      (footprint "eagle-import:TP11R")
      (libsource (lib "eagle-import") (part "TPSQTP11R"))
    )
    (comp (ref "TP2")
      (value "TPSQTP11R")
      (footprint "eagle-import:TP11R")
      (libsource (lib "eagle-import") (part "TPSQTP11R"))
    )
    (comp (ref "U$131")
      (value "MAX30003CTI+")
      (footprint "eagle-import:QFN-28")
      (libsource (lib "eagle-import") (part "MAX30003"))
    )
    (comp (ref "U$134")
      (value "SIT1533")
      (footprint "eagle-import:SIT1533")
      (libsource (lib "eagle-import") (part "SIT1533"))
    )
    (comp (ref "U1")
      (value "FTS31XS-U")
      (footprint "eagle-import:SSOP20_L")
      (libsource (lib "eagle-import") (part "FT231XS"))
    )
    (comp (ref "U2")
      (value "LSM6DS3")
      (footprint "eagle-import:LGA14L")
      (libsource (lib "eagle-import") (part "LSM6DS3"))
    )
    (comp (ref "Y1")
      (value "32.768kHz")
      (footprint "eagle-import:CRYSTAL-SMD-3.2X1.5MM")
      (libsource (lib "eagle-import") (part "CRYSTAL-32.768KHZSMD-3.2X1.5"))
    )
    (comp (ref "C63")
      (value "1.0uF")
      (footprint "eagle-import:C0402")
      (libsource (lib "eagle-import") (part "C-EUC0402"))
    )
    (comp (ref "C64")
      (value "4.7u")
      (footprint "eagle-import:C0805")
      (libsource (lib "eagle-import") (part "C-EUC0805"))
    )
    (comp (ref "C65")
      (value "4.7u")
      (footprint "eagle-import:C0805")
      (libsource (lib "eagle-import") (part "C-EUC0805"))
    )
    (comp (ref "C67")
      (value "2.2uF")
      (footprint "eagle-import:C0402")
      (libsource (lib "eagle-import") (part "C-EUC0402"))
    )
    (comp (ref "C72")
      (value "1u")
      (footprint "eagle-import:C0402")
      (libsource (lib "eagle-import") (part "C-EUC0402"))
    )
    (comp (ref "CHG2")
      (value "RED")
      (footprint "eagle-import:CHIPLED_0603")
      (libsource (lib "eagle-import") (part "LEDCHIPLED_0603"))
    )
    (comp (ref "D1")
      (value "BAT20J")
      (footprint "eagle-import:SOD-323")
      (libsource (lib "eagle-import") (part "DIODE-SCHOTTKY-BAT20J"))
    )
    (comp (ref "Q2")
      (value "2.5A/30V")
      (footprint "eagle-import:SOT23-3")
      (libsource (lib "eagle-import") (part "MOSFET-PCHANNELDMG2307L"))
    )
    (comp (ref "R16")
      (value "330R")
      (footprint "eagle-import:R0402")
      (libsource (lib "eagle-import") (part "R-US_R0402"))
    )
    (comp (ref "R17")
      (value "1k")
      (footprint "eagle-import:R0402")
      (libsource (lib "eagle-import") (part "R-US_R0402"))
    )
    (comp (ref "R23")
      (value "10K")
      (footprint "eagle-import:R0402")
      (libsource (lib "eagle-import") (part "R-US_R0402"))
    )
    (comp (ref "S2")
      (value "PCM12SMTR")
      (footprint "eagle-import:SWITCH-SPST-SMD-A")
      (libsource (lib "eagle-import") (part "SWITCH-SPDT-SMD-A"))
    )
    (comp (ref "TP5")
      (value "PTR2")
      (footprint "eagle-import:P2-38-17")
      (libsource (lib "eagle-import") (part "PTR2"))
    )
    (comp (ref "U3")
      (value "MCP73831")
      (footprint "eagle-import:SOT23-5")
      (libsource (lib "eagle-import") (part "MCP73831"))
    )
    (comp (ref "U8")
      (value "AP2112K-3.3V")
      (footprint "eagle-import:SOT23-5")
      (libsource (lib "eagle-import") (part "V_REG_LDOSMD"))
    )
  )
  (nets
    (net (code "1") (name "+1.8V") (class "Default")
      (node (ref "C69") (pin "1") (pinfunction "1_1") (pintype "passive"))
      (node (ref "C77") (pin "1") (pinfunction "1_1") (pintype "passive"))
      (node (ref "C78") (pin "1") (pinfunction "1_1") (pintype "passive"))
      (node (ref "C79") (pin "1") (pinfunction "1_1") (pintype "passive"))
      (node (ref "C80") (pin "1") (pinfunction "1_1") (pintype "passive"))
      (node (ref "U$131") (pin "13") (pinfunction "DVDD_13") (pintype "bidirectional"))
      (node (ref "U$131") (pin "22") (pinfunction "AVDD_22") (pintype "bidirectional"))
      (node (ref "U$134") (pin "4") (pinfunction "VDD_4") (pintype "bidirectional"))
    )
    (net (code "2") (name "+5V") (class "Default")
      (node (ref "C1") (pin "1") (pinfunction "1_1") (pintype "passive"))
      (node (ref "C10") (pin "1") (pinfunction "1_1") (pintype "passive"))
      (node (ref "C100") (pin "1") (pinfunction "1_1") (pintype "passive"))
      (node (ref "C101") (pin "1") (pinfunction "1_1") (pintype "passive"))
      (node (ref "C102") (pin "1") (pinfunction "1_1") (pintype "passive"))
      (node (ref "C103") (pin "1") (pinfunction "1_1") (pintype "passive"))
      (node (ref "C104") (pin "1") (pinfunction "1_1") (pintype "passive"))
      (node (ref "C105") (pin "1") (pinfunction "1_1") (pintype "passive"))
      (node (ref "C106") (pin "1") (pinfunction "1_1") (pintype "passive"))
      (node (ref "C107") (pin "1") (pinfunction "1_1") (pintype "passive"))
      (node (ref "C108") (pin "1") (pinfunction "1_1") (pintype "passive"))
      (node (ref "C109") (pin "1") (pinfunction "1_1") (pintype "passive"))
      (node (ref "C110") (pin "1") (pinfunction "1_1") (pintype "passive"))
      (node (ref "C111") (pin "1") (pinfunction "1_1") (pintype "passive"))
      (node (ref "C112") (pin "1") (pinfunction "1_1") (pintype "passive"))
      (node (ref "C113") (pin "1") (pinfunction "1_1") (pintype "passive"))
      (node (ref "C114") (pin "1") (pinfunction "1_1") (pintype "passive"))
      (node (ref "C115") (pin "1") (pinfunction "1_1") (pintype "passive"))
      (node (ref "C116") (pin "1") (pinfunction "1_1") (pintype "passive"))
      (node (ref "C117") (pin "1") (pinfunction "1_1") (pintype "passive"))
      (node (ref "C118") (pin "1") (pinfunction "1_1") (pintype "passive"))
      (node (ref "C12") (pin "1") (pinfunction "1_1") (pintype "passive"))
      (node (ref "C14") (pin "1") (pinfunction "1_1") (pintype "passive"))
      (node (ref "C16") (pin "1") (pinfunction "1_1") (pintype "passive"))
      (node (ref "C17") (pin "1") (pinfunction "1_1") (pintype "passive"))
      (node (ref "C18") (pin "1") (pinfunction "1_1") (pintype "passive"))
      (node (ref "C19") (pin "1") (pinfunction "1_1") (pintype "passive"))
      (node (ref "C21") (pin "1") (pinfunction "1_1") (pintype "passive"))
      (node (ref "C22") (pin "1") (pinfunction "1_1") (pintype "passive"))
      (node (ref "C23") (pin "1") (pinfunction "1_1") (pintype "passive"))
      (node (ref "C24") (pin "1") (pinfunction "1_1") (pintype "passive"))
      (node (ref "C25") (pin "1") (pinfunction "1_1") (pintype "passive"))
      (node (ref "C26") (pin "1") (pinfunction "1_1") (pintype "passive"))
      (node (ref "C27") (pin "1") (pinfunction "1_1") (pintype "passive"))
      (node (ref "C28") (pin "1") (pinfunction "1_1") (pintype "passive"))
      (node (ref "C29") (pin "1") (pinfunction "1_1") (pintype "passive"))
      (node (ref "C3") (pin "1") (pinfunction "1_1") (pintype "passive"))
      (node (ref "C30") (pin "1") (pinfunction "1_1") (pintype "passive"))
      (node (ref "C31") (pin "1") (pinfunction "1_1") (pintype "passive"))
      (node (ref "C32") (pin "1") (pinfunction "1_1") (pintype "passive"))
      (node (ref "C33") (pin "1") (pinfunction "1_1") (pintype "passive"))
      (node (ref "C34") (pin "1") (pinfunction "1_1") (pintype "passive"))
      (node (ref "C35") (pin "1") (pinfunction "1_1") (pintype "passive"))
      (node (ref "C36") (pin "1") (pinfunction "1_1") (pintype "passive"))
      (node (ref "C37") (pin "1") (pinfunction "1_1") (pintype "passive"))
      (node (ref "C38") (pin "1") (pinfunction "1_1") (pintype "passive"))
      (node (ref "C39") (pin "1") (pinfunction "1_1") (pintype "passive"))
      (node (ref "C4") (pin "1") (pinfunction "1_1") (pintype "passive"))
      (node (ref "C40") (pin "1") (pinfunction "1_1") (pintype "passive"))
      (node (ref "C41") (pin "1") (pinfunction "1_1") (pintype "passive"))
      (node (ref "C42") (pin "1") (pinfunction "1_1") (pintype "passive"))
      (node (ref "C43") (pin "1") (pinfunction "1_1") (pintype "passive"))
      (node (ref "C44") (pin "1") (pinfunction "1_1") (pintype "passive"))
      (node (ref "C45") (pin "1") (pinfunction "1_1") (pintype "passive"))
      (node (ref "C46") (pin "1") (pinfunction "1_1") (pintype "passive"))
      (node (ref "C47") (pin "1") (pinfunction "1_1") (pintype "passive"))
      (node (ref "C5") (pin "1") (pinfunction "1_1") (pintype "passive"))
      (node (ref "C50") (pin "1") (pinfunction "1_1") (pintype "passive"))
      (node (ref "C51") (pin "1") (pinfunction "1_1") (pintype "passive"))
      (node (ref "C52") (pin "1") (pinfunction "1_1") (pintype "passive"))
      (node (ref "C53") (pin "1") (pinfunction "1_1") (pintype "passive"))
      (node (ref "C54") (pin "1") (pinfunction "1_1") (pintype "passive"))
      (node (ref "C55") (pin "1") (pinfunction "1_1") (pintype "passive"))
      (node (ref "C56") (pin "1") (pinfunction "1_1") (pintype "passive"))
      (node (ref "C59") (pin "1") (pinfunction "1_1") (pintype "passive"))
      (node (ref "C66") (pin "1") (pinfunction "1_1") (pintype "passive"))
      (node (ref "C83") (pin "1") (pinfunction "1_1") (pintype "passive"))
      (node (ref "C84") (pin "1") (pinfunction "1_1") (pintype "passive"))
      (node (ref "C85") (pin "1") (pinfunction "1_1") (pintype "passive"))
      (node (ref "C86") (pin "1") (pinfunction "1_1") (pintype "passive"))
      (node (ref "C87") (pin "1") (pinfunction "1_1") (pintype "passive"))
      (node (ref "C88") (pin "1") (pinfunction "1_1") (pintype "passive"))
      (node (ref "C89") (pin "1") (pinfunction "1_1") (pintype "passive"))
      (node (ref "C9") (pin "1") (pinfunction "1_1") (pintype "passive"))
      (node (ref "C90") (pin "1") (pinfunction "1_1") (pintype "passive"))
      (node (ref "C91") (pin "1") (pinfunction "1_1") (pintype "passive"))
      (node (ref "C92") (pin "1") (pinfunction "1_1") (pintype "passive"))
      (node (ref "C93") (pin "1") (pinfunction "1_1") (pintype "passive"))
      (node (ref "C94") (pin "1") (pinfunction "1_1") (pintype "passive"))
      (node (ref "C95") (pin "1") (pinfunction "1_1") (pintype "passive"))
      (node (ref "C96") (pin "1") (pinfunction "1_1") (pintype "passive"))
      (node (ref "C97") (pin "1") (pinfunction "1_1") (pintype "passive"))
      (node (ref "C98") (pin "1") (pinfunction "1_1") (pintype "passive"))
      (node (ref "C99") (pin "1") (pinfunction "1_1") (pintype "passive"))
      (node (ref "SJ1") (pin "1") (pinfunction "1_1") (pintype "passive"))
      (node (ref "U$10") (pin "V_CC") (pinfunction "VCC_V_CC") (pintype "bidirectional"))
      (node (ref "U$100") (pin "V_CC") (pinfunction "VCC_V_CC") (pintype "bidirectional"))
      (node (ref "U$101") (pin "V_CC") (pinfunction "VCC_V_CC") (pintype "bidirectional"))
      (node (ref "U$102") (pin "V_CC") (pinfunction "VCC_V_CC") (pintype "bidirectional"))
      (node (ref "U$103") (pin "V_CC") (pinfunction "VCC_V_CC") (pintype "bidirectional"))
      (node (ref "U$104") (pin "V_CC") (pinfunction "VCC_V_CC") (pintype "bidirectional"))
      (node (ref "U$105") (pin "V_CC") (pinfunction "VCC_V_CC") (pintype "bidirectional"))
      (node (ref "U$106") (pin "V_CC") (pinfunction "VCC_V_CC") (pintype "bidirectional"))
      (node (ref "U$107") (pin "V_CC") (pinfunction "VCC_V_CC") (pintype "bidirectional"))
      (node (ref "U$108") (pin "V_CC") (pinfunction "VCC_V_CC") (pintype "bidirectional"))
      (node (ref "U$109") (pin "V_CC") (pinfunction "VCC_V_CC") (pintype "bidirectional"))
      (node (ref "U$11") (pin "V_CC") (pinfunction "VCC_V_CC") (pintype "bidirectional"))
      (node (ref "U$110") (pin "V_CC") (pinfunction "VCC_V_CC") (pintype "bidirectional"))
      (node (ref "U$111") (pin "V_CC") (pinfunction "VCC_V_CC") (pintype "bidirectional"))
      (node (ref "U$112") (pin "V_CC") (pinfunction "VCC_V_CC") (pintype "bidirectional"))
      (node (ref "U$113") (pin "V_CC") (pinfunction "VCC_V_CC") (pintype "bidirectional"))
      (node (ref "U$114") (pin "V_CC") (pinfunction "VCC_V_CC") (pintype "bidirectional"))
      (node (ref "U$115") (pin "V_CC") (pinfunction "VCC_V_CC") (pintype "bidirectional"))
      (node (ref "U$116") (pin "V_CC") (pinfunction "VCC_V_CC") (pintype "bidirectional"))
      (node (ref "U$117") (pin "V_CC") (pinfunction "VCC_V_CC") (pintype "bidirectional"))
      (node (ref "U$118") (pin "V_CC") (pinfunction "VCC_V_CC") (pintype "bidirectional"))
      (node (ref "U$119") (pin "V_CC") (pinfunction "VCC_V_CC") (pintype "bidirectional"))
      (node (ref "U$12") (pin "V_CC") (pinfunction "VCC_V_CC") (pintype "bidirectional"))
      (node (ref "U$120") (pin "V_CC") (pinfunction "VCC_V_CC") (pintype "bidirectional"))
      (node (ref "U$121") (pin "V_CC") (pinfunction "VCC_V_CC") (pintype "bidirectional"))
      (node (ref "U$122") (pin "V_CC") (pinfunction "VCC_V_CC") (pintype "bidirectional"))
      (node (ref "U$123") (pin "V_CC") (pinfunction "VCC_V_CC") (pintype "bidirectional"))
      (node (ref "U$124") (pin "V_CC") (pinfunction "VCC_V_CC") (pintype "bidirectional"))
      (node (ref "U$125") (pin "V_CC") (pinfunction "VCC_V_CC") (pintype "bidirectional"))
      (node (ref "U$126") (pin "V_CC") (pinfunction "VCC_V_CC") (pintype "bidirectional"))
      (node (ref "U$127") (pin "V_CC") (pinfunction "VCC_V_CC") (pintype "bidirectional"))
      (node (ref "U$128") (pin "V_CC") (pinfunction "VCC_V_CC") (pintype "bidirectional"))
      (node (ref "U$129") (pin "V_CC") (pinfunction "VCC_V_CC") (pintype "bidirectional"))
      (node (ref "U$13") (pin "V_CC") (pinfunction "VCC_V_CC") (pintype "bidirectional"))
      (node (ref "U$130") (pin "V_CC") (pinfunction "VCC_V_CC") (pintype "bidirectional"))
      (node (ref "U$14") (pin "V_CC") (pinfunction "VCC_V_CC") (pintype "bidirectional"))
      (node (ref "U$15") (pin "V_CC") (pinfunction "VCC_V_CC") (pintype "bidirectional"))
      (node (ref "U$18") (pin "V_CC") (pinfunction "VCC_V_CC") (pintype "bidirectional"))
      (node (ref "U$19") (pin "V_CC") (pinfunction "VCC_V_CC") (pintype "bidirectional"))
      (node (ref "U$20") (pin "V_CC") (pinfunction "VCC_V_CC") (pintype "bidirectional"))
      (node (ref "U$21") (pin "V_CC") (pinfunction "VCC_V_CC") (pintype "bidirectional"))
      (node (ref "U$22") (pin "V_CC") (pinfunction "VCC_V_CC") (pintype "bidirectional"))
      (node (ref "U$24") (pin "V_CC") (pinfunction "VCC_V_CC") (pintype "bidirectional"))
      (node (ref "U$25") (pin "V_CC") (pinfunction "VCC_V_CC") (pintype "bidirectional"))
      (node (ref "U$27") (pin "V_CC") (pinfunction "VCC_V_CC") (pintype "bidirectional"))
      (node (ref "U$28") (pin "V_CC") (pinfunction "VCC_V_CC") (pintype "bidirectional"))
      (node (ref "U$29") (pin "V_CC") (pinfunction "VCC_V_CC") (pintype "bidirectional"))
      (node (ref "U$30") (pin "V_CC") (pinfunction "VCC_V_CC") (pintype "bidirectional"))
      (node (ref "U$31") (pin "V_CC") (pinfunction "VCC_V_CC") (pintype "bidirectional"))
      (node (ref "U$32") (pin "V_CC") (pinfunction "VCC_V_CC") (pintype "bidirectional"))
      (node (ref "U$33") (pin "V_CC") (pinfunction "VCC_V_CC") (pintype "bidirectional"))
      (node (ref "U$34") (pin "V_CC") (pinfunction "VCC_V_CC") (pintype "bidirectional"))
      (node (ref "U$35") (pin "V_CC") (pinfunction "VCC_V_CC") (pintype "bidirectional"))
      (node (ref "U$36") (pin "V_CC") (pinfunction "VCC_V_CC") (pintype "bidirectional"))
      (node (ref "U$37") (pin "V_CC") (pinfunction "VCC_V_CC") (pintype "bidirectional"))
      (node (ref "U$38") (pin "V_CC") (pinfunction "VCC_V_CC") (pintype "bidirectional"))
      (node (ref "U$39") (pin "V_CC") (pinfunction "VCC_V_CC") (pintype "bidirectional"))
      (node (ref "U$40") (pin "V_CC") (pinfunction "VCC_V_CC") (pintype "bidirectional"))
      (node (ref "U$41") (pin "V_CC") (pinfunction "VCC_V_CC") (pintype "bidirectional"))
      (node (ref "U$42") (pin "V_CC") (pinfunction "VCC_V_CC") (pintype "bidirectional"))
      (node (ref "U$43") (pin "V_CC") (pinfunction "VCC_V_CC") (pintype "bidirectional"))
      (node (ref "U$44") (pin "V_CC") (pinfunction "VCC_V_CC") (pintype "bidirectional"))
      (node (ref "U$45") (pin "V_CC") (pinfunction "VCC_V_CC") (pintype "bidirectional"))
      (node (ref "U$46") (pin "V_CC") (pinfunction "VCC_V_CC") (pintype "bidirectional"))
      (node (ref "U$47") (pin "V_CC") (pinfunction "VCC_V_CC") (pintype "bidirectional"))
      (node (ref "U$48") (pin "V_CC") (pinfunction "VCC_V_CC") (pintype "bidirectional"))
      (node (ref "U$49") (pin "V_CC") (pinfunction "VCC_V_CC") (pintype "bidirectional"))
      (node (ref "U$50") (pin "V_CC") (pinfunction "VCC_V_CC") (pintype "bidirectional"))
      (node (ref "U$51") (pin "V_CC") (pinfunction "VCC_V_CC") (pintype "bidirectional"))
      (node (ref "U$52") (pin "V_CC") (pinfunction "VCC_V_CC") (pintype "bidirectional"))
      (node (ref "U$53") (pin "V_CC") (pinfunction "VCC_V_CC") (pintype "bidirectional"))
      (node (ref "U$54") (pin "V_CC") (pinfunction "VCC_V_CC") (pintype "bidirectional"))
      (node (ref "U$55") (pin "V_CC") (pinfunction "VCC_V_CC") (pintype "bidirectional"))
      (node (ref "U$56") (pin "V_CC") (pinfunction "VCC_V_CC") (pintype "bidirectional"))
      (node (ref "U$57") (pin "V_CC") (pinfunction "VCC_V_CC") (pintype "bidirectional"))
      (node (ref "U$58") (pin "V_CC") (pinfunction "VCC_V_CC") (pintype "bidirectional"))
      (node (ref "U$59") (pin "V_CC") (pinfunction "VCC_V_CC") (pintype "bidirectional"))
      (node (ref "U$60") (pin "V_CC") (pinfunction "VCC_V_CC") (pintype "bidirectional"))
      (node (ref "U$61") (pin "V_CC") (pinfunction "VCC_V_CC") (pintype "bidirectional"))
      (node (ref "U$62") (pin "V_CC") (pinfunction "VCC_V_CC") (pintype "bidirectional"))
      (node (ref "U$63") (pin "V_CC") (pinfunction "VCC_V_CC") (pintype "bidirectional"))
      (node (ref "U$64") (pin "V_CC") (pinfunction "VCC_V_CC") (pintype "bidirectional"))
      (node (ref "U$65") (pin "V_CC") (pinfunction "VCC_V_CC") (pintype "bidirectional"))
      (node (ref "U$66") (pin "V_CC") (pinfunction "VCC_V_CC") (pintype "bidirectional"))
      (node (ref "U$67") (pin "V_CC") (pinfunction "VCC_V_CC") (pintype "bidirectional"))
      (node (ref "U$68") (pin "V_CC") (pinfunction "VCC_V_CC") (pintype "bidirectional"))
      (node (ref "U$69") (pin "V_CC") (pinfunction "VCC_V_CC") (pintype "bidirectional"))
      (node (ref "U$70") (pin "V_CC") (pinfunction "VCC_V_CC") (pintype "bidirectional"))
      (node (ref "U$71") (pin "V_CC") (pinfunction "VCC_V_CC") (pintype "bidirectional"))
      (node (ref "U$72") (pin "V_CC") (pinfunction "VCC_V_CC") (pintype "bidirectional"))
      (node (ref "U$73") (pin "V_CC") (pinfunction "VCC_V_CC") (pintype "bidirectional"))
      (node (ref "U$74") (pin "V_CC") (pinfunction "VCC_V_CC") (pintype "bidirectional"))
      (node (ref "U$75") (pin "V_CC") (pinfunction "VCC_V_CC") (pintype "bidirectional"))
      (node (ref "U$76") (pin "V_CC") (pinfunction "VCC_V_CC") (pintype "bidirectional"))
      (node (ref "U$77") (pin "V_CC") (pinfunction "VCC_V_CC") (pintype "bidirectional"))
      (node (ref "U$78") (pin "V_CC") (pinfunction "VCC_V_CC") (pintype "bidirectional"))
      (node (ref "U$79") (pin "V_CC") (pinfunction "VCC_V_CC") (pintype "bidirectional"))
      (node (ref "U$80") (pin "V_CC") (pinfunction "VCC_V_CC") (pintype "bidirectional"))
      (node (ref "U$81") (pin "V_CC") (pinfunction "VCC_V_CC") (pintype "bidirectional"))
      (node (ref "U$82") (pin "V_CC") (pinfunction "VCC_V_CC") (pintype "bidirectional"))
      (node (ref "U$83") (pin "V_CC") (pinfunction "VCC_V_CC") (pintype "bidirectional"))
      (node (ref "U$84") (pin "V_CC") (pinfunction "VCC_V_CC") (pintype "bidirectional"))
      (node (ref "U$85") (pin "V_CC") (pinfunction "VCC_V_CC") (pintype "bidirectional"))
      (node (ref "U$86") (pin "V_CC") (pinfunction "VCC_V_CC") (pintype "bidirectional"))
      (node (ref "U$87") (pin "V_CC") (pinfunction "VCC_V_CC") (pintype "bidirectional"))
      (node (ref "U$88") (pin "V_CC") (pinfunction "VCC_V_CC") (pintype "bidirectional"))
      (node (ref "U$89") (pin "V_CC") (pinfunction "VCC_V_CC") (pintype "bidirectional"))
      (node (ref "U$9") (pin "V_CC") (pinfunction "VCC_V_CC") (pintype "bidirectional"))
      (node (ref "U$90") (pin "V_CC") (pinfunction "VCC_V_CC") (pintype "bidirectional"))
      (node (ref "U$91") (pin "V_CC") (pinfunction "VCC_V_CC") (pintype "bidirectional"))
      (node (ref "U$92") (pin "V_CC") (pinfunction "VCC_V_CC") (pintype "bidirectional"))
      (node (ref "U$93") (pin "V_CC") (pinfunction "VCC_V_CC") (pintype "bidirectional"))
      (node (ref "U$94") (pin "V_CC") (pinfunction "VCC_V_CC") (pintype "bidirectional"))
      (node (ref "U$95") (pin "V_CC") (pinfunction "VCC_V_CC") (pintype "bidirectional"))
      (node (ref "U$96") (pin "V_CC") (pinfunction "VCC_V_CC") (pintype "bidirectional"))
      (node (ref "U$97") (pin "V_CC") (pinfunction "VCC_V_CC") (pintype "bidirectional"))
      (node (ref "U$98") (pin "V_CC") (pinfunction "VCC_V_CC") (pintype "bidirectional"))
      (node (ref "U$99") (pin "V_CC") (pinfunction "VCC_V_CC") (pintype "bidirectional"))
    )
    (net (code "3") (name "0") (class "Default")
      (node (ref "IC1") (pin "23") (pinfunction "IO0_23") (pintype "bidirectional"))
      (node (ref "Q1") (pin "6") (pinfunction "C_6") (pintype "passive"))
      (node (ref "R11") (pin "1") (pinfunction "1_1") (pintype "passive"))
    )
    (net (code "4") (name "3.3V") (class "Default")
      (node (ref "C11") (pin "1") (pinfunction "1_1") (pintype "passive"))
      (node (ref "C13") (pin "1") (pinfunction "1_1") (pintype "passive"))
      (node (ref "C15") (pin "1") (pinfunction "1_1") (pintype "passive"))
      (node (ref "C2") (pin "1") (pinfunction "1_1") (pintype "passive"))
      (node (ref "C6") (pin "1") (pinfunction "1_1") (pintype "passive"))
      (node (ref "C67") (pin "1") (pinfunction "1_1") (pintype "passive"))
      (node (ref "C7") (pin "1") (pinfunction "1_1") (pintype "passive"))
      (node (ref "C81") (pin "1") (pinfunction "1_1") (pintype "passive"))
      (node (ref "C82") (pin "1") (pinfunction "1_1") (pintype "passive"))
      (node (ref "IC1") (pin "1") (pinfunction "VDDA_1") (pintype "bidirectional"))
      (node (ref "IC1") (pin "19") (pinfunction "VDD3P3_RTC_19") (pintype "bidirectional"))
      (node (ref "IC1") (pin "3") (pinfunction "VDDA3P3_1_3") (pintype "bidirectional"))
      (node (ref "IC1") (pin "37") (pinfunction "VDD3P3_CPU_37") (pintype "bidirectional"))
      (node (ref "IC1") (pin "4") (pinfunction "VDDA_3P3_4") (pintype "bidirectional"))
      (node (ref "IC1") (pin "43") (pinfunction "VDDA_2_43") (pintype "bidirectional"))
      (node (ref "IC1") (pin "46") (pinfunction "VDDA_3_46") (pintype "bidirectional"))
      (node (ref "R1") (pin "2") (pinfunction "2_2") (pintype "passive"))
      (node (ref "R11") (pin "2") (pinfunction "2_2") (pintype "passive"))
      (node (ref "R19") (pin "2") (pinfunction "2_2") (pintype "passive"))
      (node (ref "R4") (pin "2") (pinfunction "2_2") (pintype "passive"))
      (node (ref "R7") (pin "2") (pinfunction "2_2") (pintype "passive"))
      (node (ref "R8") (pin "2") (pinfunction "2_2") (pintype "passive"))
      (node (ref "U$131") (pin "19") (pinfunction "OVDD_19") (pintype "bidirectional"))
      (node (ref "U2") (pin "5") (pinfunction "VDDIO_5") (pintype "bidirectional"))
      (node (ref "U2") (pin "8") (pinfunction "VDD_8") (pintype "bidirectional"))
      (node (ref "U8") (pin "5") (pinfunction "OUT_5") (pintype "passive"))
    )
    (net (code "5") (name "3.3V_F") (class "Default")
      (node (ref "C62") (pin "1") (pinfunction "1_1") (pintype "passive"))
      (node (ref "U1") (pin "13") (pinfunction "3V3OUT_13") (pintype "bidirectional"))
      (node (ref "U1") (pin "14") (pinfunction "~{RESET}_14") (pintype "bidirectional"))
      (node (ref "U1") (pin "3") (pinfunction "VCCIO_3") (pintype "bidirectional"))
    )
    (net (code "6") (name "32K_XN") (class "Default")
      (node (ref "C58") (pin "2") (pinfunction "2_2") (pintype "passive"))
      (node (ref "IC1") (pin "13") (pinfunction "IO33_13") (pintype "bidirectional"))
      (node (ref "Y1") (pin "P$2") (pinfunction "2_P$2") (pintype "passive"))
    )
    (net (code "7") (name "32K_XP") (class "Default")
      (node (ref "C57") (pin "2") (pinfunction "2_2") (pintype "passive"))
      (node (ref "IC1") (pin "12") (pinfunction "IO32_12") (pintype "bidirectional"))
      (node (ref "Y1") (pin "P$1") (pinfunction "1_P$1") (pintype "passive"))
    )
    (net (code "8") (name "BAT_MON") (class "Default")
      (node (ref "IC1") (pin "10") (pinfunction "IO34_10") (pintype "bidirectional"))
      (node (ref "R25") (pin "1") (pinfunction "1_1") (pintype "passive"))
      (node (ref "R26") (pin "2") (pinfunction "2_2") (pintype "passive"))
    )
    (net (code "9") (name "BUTTON") (class "Default")
      (node (ref "IC1") (pin "39") (pinfunction "IO22_39") (pintype "bidirectional"))
      (node (ref "R19") (pin "1") (pinfunction "1_1") (pintype "passive"))
      (node (ref "SW2") (pin "B") (pinfunction "S_B") (pintype "passive"))
      (node (ref "SW2") (pin "B'") (pinfunction "S1_B'") (pintype "passive"))
    )
    (net (code "10") (name "CHIP_PU") (class "Default")
      (node (ref "IC1") (pin "9") (pinfunction "EN_9") (pintype "bidirectional"))
      (node (ref "Q1") (pin "3") (pinfunction "C_3") (pintype "passive"))
      (node (ref "R8") (pin "1") (pinfunction "1_1") (pintype "passive"))
    )
    (net (code "11") (name "CS") (class "Default")
      (node (ref "R1") (pin "1") (pinfunction "1_1") (pintype "passive"))
      (node (ref "U2") (pin "12") (pinfunction "CS_12") (pintype "bidirectional"))
    )
    (net (code "12") (name "CSB") (class "Default")
      (node (ref "IC1") (pin "24") (pinfunction "IO4_24") (pintype "bidirectional"))
      (node (ref "U$131") (pin "15") (pinfunction "CSB_15") (pintype "bidirectional"))
    )
    (net (code "13") (name "D+") (class "Default")
      (node (ref "JP7") (pin "3") (pinfunction "D+_3") (pintype "bidirectional"))
      (node (ref "R15") (pin "1") (pinfunction "1_1") (pintype "passive"))
    )
    (net (code "14") (name "D-") (class "Default")
      (node (ref "JP7") (pin "2") (pinfunction "D-_2") (pintype "bidirectional"))
      (node (ref "R14") (pin "1") (pinfunction "1_1") (pintype "passive"))
    )
    (net (code "15") (name "DTR") (class "Default")
      (node (ref "Q1") (pin "1") (pinfunction "E_1") (pintype "passive"))
      (node (ref "R9") (pin "1") (pinfunction "1_1") (pintype "passive"))
      (node (ref "U1") (pin "1") (pinfunction "~{DTR}_1") (pintype "bidirectional"))
    )
    (net (code "16") (name "ECGN") (class "Default")
      (node (ref "C74") (pin "1") (pinfunction "1_1") (pintype "passive"))
      (node (ref "C76") (pin "2") (pinfunction "2_2") (pintype "passive"))
      (node (ref "R6") (pin "2") (pinfunction "2_2") (pintype "passive"))
      (node (ref "U$131") (pin "7") (pinfunction "EGGN_7") (pintype "bidirectional"))
    )
    (net (code "17") (name "ECGP") (class "Default")
      (node (ref "C75") (pin "1") (pinfunction "1_1") (pintype "passive"))
      (node (ref "C76") (pin "1") (pinfunction "1_1") (pintype "passive"))
      (node (ref "R3") (pin "2") (pinfunction "2_2") (pintype "passive"))
      (node (ref "U$131") (pin "6") (pinfunction "EGGP_6") (pintype "bidirectional"))
    )
    (net (code "18") (name "EN") (class "Default")
      (node (ref "S2") (pin "2") (pinfunction "P_2") (pintype "passive"))
      (node (ref "U8") (pin "3") (pinfunction "EN_3") (pintype "input"))
    )
    (net (code "19") (name "FCLK") (class "Default")
      (node (ref "U$131") (pin "14") (pinfunction "FCLK_14") (pintype "bidirectional"))
      (node (ref "U$134") (pin "3") (pinfunction "CLK_3") (pintype "bidirectional"))
    )
    (net (code "20") (name "GND") (class "Default")
      (node (ref "C1") (pin "2") (pinfunction "2_2") (pintype "passive"))
      (node (ref "C10") (pin "2") (pinfunction "2_2") (pintype "passive"))
      (node (ref "C100") (pin "2") (pinfunction "2_2") (pintype "passive"))
      (node (ref "C101") (pin "2") (pinfunction "2_2") (pintype "passive"))
      (node (ref "C102") (pin "2") (pinfunction "2_2") (pintype "passive"))
      (node (ref "C103") (pin "2") (pinfunction "2_2") (pintype "passive"))
      (node (ref "C104") (pin "2") (pinfunction "2_2") (pintype "passive"))
      (node (ref "C105") (pin "2") (pinfunction "2_2") (pintype "passive"))
      (node (ref "C106") (pin "2") (pinfunction "2_2") (pintype "passive"))
      (node (ref "C107") (pin "2") (pinfunction "2_2") (pintype "passive"))
      (node (ref "C108") (pin "2") (pinfunction "2_2") (pintype "passive"))
      (node (ref "C109") (pin "2") (pinfunction "2_2") (pintype "passive"))
      (node (ref "C11") (pin "2") (pinfunction "2_2") (pintype "passive"))
      (node (ref "C110") (pin "2") (pinfunction "2_2") (pintype "passive"))
      (node (ref "C111") (pin "2") (pinfunction "2_2") (pintype "passive"))
      (node (ref "C112") (pin "2") (pinfunction "2_2") (pintype "passive"))
      (node (ref "C113") (pin "2") (pinfunction "2_2") (pintype "passive"))
      (node (ref "C114") (pin "2") (pinfunction "2_2") (pintype "passive"))
      (node (ref "C115") (pin "2") (pinfunction "2_2") (pintype "passive"))
      (node (ref "C116") (pin "2") (pinfunction "2_2") (pintype "passive"))
      (node (ref "C117") (pin "2") (pinfunction "2_2") (pintype "passive"))
      (node (ref "C118") (pin "2") (pinfunction "2_2") (pintype "passive"))
      (node (ref "C12") (pin "2") (pinfunction "2_2") (pintype "passive"))
      (node (ref "C13") (pin "2") (pinfunction "2_2") (pintype "passive"))
      (node (ref "C14") (pin "2") (pinfunction "2_2") (pintype "passive"))
      (node (ref "C15") (pin "2") (pinfunction "2_2") (pintype "passive"))
      (node (ref "C16") (pin "2") (pinfunction "2_2") (pintype "passive"))
      (node (ref "C17") (pin "2") (pinfunction "2_2") (pintype "passive"))
      (node (ref "C18") (pin "2") (pinfunction "2_2") (pintype "passive"))
      (node (ref "C19") (pin "2") (pinfunction "2_2") (pintype "passive"))
      (node (ref "C2") (pin "2") (pinfunction "2_2") (pintype "passive"))
      (node (ref "C21") (pin "2") (pinfunction "2_2") (pintype "passive"))
      (node (ref "C22") (pin "2") (pinfunction "2_2") (pintype "passive"))
      (node (ref "C23") (pin "2") (pinfunction "2_2") (pintype "passive"))
      (node (ref "C24") (pin "2") (pinfunction "2_2") (pintype "passive"))
      (node (ref "C25") (pin "2") (pinfunction "2_2") (pintype "passive"))
      (node (ref "C26") (pin "2") (pinfunction "2_2") (pintype "passive"))
      (node (ref "C27") (pin "2") (pinfunction "2_2") (pintype "passive"))
      (node (ref "C28") (pin "2") (pinfunction "2_2") (pintype "passive"))
      (node (ref "C29") (pin "2") (pinfunction "2_2") (pintype "passive"))
      (node (ref "C3") (pin "2") (pinfunction "2_2") (pintype "passive"))
      (node (ref "C30") (pin "2") (pinfunction "2_2") (pintype "passive"))
      (node (ref "C31") (pin "2") (pinfunction "2_2") (pintype "passive"))
      (node (ref "C32") (pin "2") (pinfunction "2_2") (pintype "passive"))
      (node (ref "C33") (pin "2") (pinfunction "2_2") (pintype "passive"))
      (node (ref "C34") (pin "2") (pinfunction "2_2") (pintype "passive"))
      (node (ref "C35") (pin "2") (pinfunction "2_2") (pintype "passive"))
      (node (ref "C36") (pin "2") (pinfunction "2_2") (pintype "passive"))
      (node (ref "C37") (pin "2") (pinfunction "2_2") (pintype "passive"))
      (node (ref "C38") (pin "2") (pinfunction "2_2") (pintype "passive"))
      (node (ref "C39") (pin "2") (pinfunction "2_2") (pintype "passive"))
      (node (ref "C4") (pin "2") (pinfunction "2_2") (pintype "passive"))
      (node (ref "C40") (pin "2") (pinfunction "2_2") (pintype "passive"))
      (node (ref "C41") (pin "2") (pinfunction "2_2") (pintype "passive"))
      (node (ref "C42") (pin "2") (pinfunction "2_2") (pintype "passive"))
      (node (ref "C43") (pin "2") (pinfunction "2_2") (pintype "passive"))
      (node (ref "C44") (pin "2") (pinfunction "2_2") (pintype "passive"))
      (node (ref "C45") (pin "2") (pinfunction "2_2") (pintype "passive"))
      (node (ref "C46") (pin "2") (pinfunction "2_2") (pintype "passive"))
      (node (ref "C47") (pin "2") (pinfunction "2_2") (pintype "passive"))
      (node (ref "C48") (pin "2") (pinfunction "2_2") (pintype "passive"))
      (node (ref "C5") (pin "2") (pinfunction "2_2") (pintype "passive"))
      (node (ref "C50") (pin "2") (pinfunction "2_2") (pintype "passive"))
      (node (ref "C51") (pin "2") (pinfunction "2_2") (pintype "passive"))
      (node (ref "C52") (pin "2") (pinfunction "2_2") (pintype "passive"))
      (node (ref "C53") (pin "2") (pinfunction "2_2") (pintype "passive"))
      (node (ref "C54") (pin "2") (pinfunction "2_2") (pintype "passive"))
      (node (ref "C55") (pin "2") (pinfunction "2_2") (pintype "passive"))
      (node (ref "C56") (pin "2") (pinfunction "2_2") (pintype "passive"))
      (node (ref "C57") (pin "1") (pinfunction "1_1") (pintype "passive"))
      (node (ref "C58") (pin "1") (pinfunction "1_1") (pintype "passive"))
      (node (ref "C59") (pin "2") (pinfunction "2_2") (pintype "passive"))
      (node (ref "C6") (pin "2") (pinfunction "2_2") (pintype "passive"))
      (node (ref "C60") (pin "2") (pinfunction "2_2") (pintype "passive"))
      (node (ref "C61") (pin "2") (pinfunction "2_2") (pintype "passive"))
      (node (ref "C62") (pin "2") (pinfunction "2_2") (pintype "passive"))
      (node (ref "C63") (pin "2") (pinfunction "2_2") (pintype "passive"))
      (node (ref "C64") (pin "2") (pinfunction "2_2") (pintype "passive"))
      (node (ref "C65") (pin "2") (pinfunction "2_2") (pintype "passive"))
      (node (ref "C66") (pin "2") (pinfunction "2_2") (pintype "passive"))
      (node (ref "C67") (pin "2") (pinfunction "2_2") (pintype "passive"))
      (node (ref "C68") (pin "2") (pinfunction "2_2") (pintype "passive"))
      (node (ref "C69") (pin "2") (pinfunction "2_2") (pintype "passive"))
      (node (ref "C7") (pin "2") (pinfunction "2_2") (pintype "passive"))
      (node (ref "C70") (pin "2") (pinfunction "2_2") (pintype "passive"))
      (node (ref "C71") (pin "2") (pinfunction "2_2") (pintype "passive"))
      (node (ref "C72") (pin "1") (pinfunction "1_1") (pintype "passive"))
      (node (ref "C73") (pin "2") (pinfunction "2_2") (pintype "passive"))
      (node (ref "C74") (pin "2") (pinfunction "2_2") (pintype "passive"))
      (node (ref "C75") (pin "2") (pinfunction "2_2") (pintype "passive"))
      (node (ref "C77") (pin "2") (pinfunction "2_2") (pintype "passive"))
      (node (ref "C78") (pin "2") (pinfunction "2_2") (pintype "passive"))
      (node (ref "C79") (pin "2") (pinfunction "2_2") (pintype "passive"))
      (node (ref "C8") (pin "2") (pinfunction "2_2") (pintype "passive"))
      (node (ref "C80") (pin "2") (pinfunction "2_2") (pintype "passive"))
      (node (ref "C81") (pin "2") (pinfunction "2_2") (pintype "passive"))
      (node (ref "C82") (pin "2") (pinfunction "2_2") (pintype "passive"))
      (node (ref "C83") (pin "2") (pinfunction "2_2") (pintype "passive"))
      (node (ref "C84") (pin "2") (pinfunction "2_2") (pintype "passive"))
      (node (ref "C85") (pin "2") (pinfunction "2_2") (pintype "passive"))
      (node (ref "C86") (pin "2") (pinfunction "2_2") (pintype "passive"))
      (node (ref "C87") (pin "2") (pinfunction "2_2") (pintype "passive"))
      (node (ref "C88") (pin "2") (pinfunction "2_2") (pintype "passive"))
      (node (ref "C89") (pin "2") (pinfunction "2_2") (pintype "passive"))
      (node (ref "C9") (pin "2") (pinfunction "2_2") (pintype "passive"))
      (node (ref "C90") (pin "2") (pinfunction "2_2") (pintype "passive"))
      (node (ref "C91") (pin "2") (pinfunction "2_2") (pintype "passive"))
      (node (ref "C92") (pin "2") (pinfunction "2_2") (pintype "passive"))
      (node (ref "C93") (pin "2") (pinfunction "2_2") (pintype "passive"))
      (node (ref "C94") (pin "2") (pinfunction "2_2") (pintype "passive"))
      (node (ref "C95") (pin "2") (pinfunction "2_2") (pintype "passive"))
      (node (ref "C96") (pin "2") (pinfunction "2_2") (pintype "passive"))
      (node (ref "C97") (pin "2") (pinfunction "2_2") (pintype "passive"))
      (node (ref "C98") (pin "2") (pinfunction "2_2") (pintype "passive"))
      (node (ref "C99") (pin "2") (pinfunction "2_2") (pintype "passive"))
      (node (ref "E1") (pin "GND") (pinfunction "GND_GND") (pintype "bidirectional"))
      (node (ref "E1") (pin "GND2") (pinfunction "GND_GND2") (pintype "bidirectional"))
      (node (ref "IC1") (pin "EXP") (pinfunction "GNDPAD_EXP") (pintype "power_in"))
      (node (ref "JP7") (pin "5") (pinfunction "GND_5") (pintype "bidirectional"))
      (node (ref "JP7") (pin "P$5") (pinfunction "GND1_P$5") (pintype "bidirectional"))
      (node (ref "JP7") (pin "P$6") (pinfunction "GND2_P$6") (pintype "bidirectional"))
      (node (ref "L1") (pin "2") (pinfunction "2_2") (pintype "passive"))
      (node (ref "R17") (pin "1") (pinfunction "1_1") (pintype "passive"))
      (node (ref "R23") (pin "1") (pinfunction "1_1") (pintype "passive"))
      (node (ref "R26") (pin "1") (pinfunction "1_1") (pintype "passive"))
      (node (ref "S2") (pin "1") (pinfunction "O_1") (pintype "passive"))
      (node (ref "SW2") (pin "A") (pinfunction "P_A") (pintype "passive"))
      (node (ref "TP5") (pin "TP-2") (pinfunction "TP_TP-2") (pintype "input"))
      (node (ref "U$10") (pin "GND") (pinfunction "GND_GND") (pintype "bidirectional"))
      (node (ref "U$100") (pin "GND") (pinfunction "GND_GND") (pintype "bidirectional"))
      (node (ref "U$101") (pin "GND") (pinfunction "GND_GND") (pintype "bidirectional"))
      (node (ref "U$102") (pin "GND") (pinfunction "GND_GND") (pintype "bidirectional"))
      (node (ref "U$103") (pin "GND") (pinfunction "GND_GND") (pintype "bidirectional"))
      (node (ref "U$104") (pin "GND") (pinfunction "GND_GND") (pintype "bidirectional"))
      (node (ref "U$105") (pin "GND") (pinfunction "GND_GND") (pintype "bidirectional"))
      (node (ref "U$106") (pin "GND") (pinfunction "GND_GND") (pintype "bidirectional"))
      (node (ref "U$107") (pin "GND") (pinfunction "GND_GND") (pintype "bidirectional"))
      (node (ref "U$108") (pin "GND") (pinfunction "GND_GND") (pintype "bidirectional"))
      (node (ref "U$109") (pin "GND") (pinfunction "GND_GND") (pintype "bidirectional"))
      (node (ref "U$11") (pin "GND") (pinfunction "GND_GND") (pintype "bidirectional"))
      (node (ref "U$110") (pin "GND") (pinfunction "GND_GND") (pintype "bidirectional"))
      (node (ref "U$111") (pin "GND") (pinfunction "GND_GND") (pintype "bidirectional"))
      (node (ref "U$112") (pin "GND") (pinfunction "GND_GND") (pintype "bidirectional"))
      (node (ref "U$113") (pin "GND") (pinfunction "GND_GND") (pintype "bidirectional"))
      (node (ref "U$114") (pin "GND") (pinfunction "GND_GND") (pintype "bidirectional"))
      (node (ref "U$115") (pin "GND") (pinfunction "GND_GND") (pintype "bidirectional"))
      (node (ref "U$116") (pin "GND") (pinfunction "GND_GND") (pintype "bidirectional"))
      (node (ref "U$117") (pin "GND") (pinfunction "GND_GND") (pintype "bidirectional"))
      (node (ref "U$118") (pin "GND") (pinfunction "GND_GND") (pintype "bidirectional"))
      (node (ref "U$119") (pin "GND") (pinfunction "GND_GND") (pintype "bidirectional"))
      (node (ref "U$12") (pin "GND") (pinfunction "GND_GND") (pintype "bidirectional"))
      (node (ref "U$120") (pin "GND") (pinfunction "GND_GND") (pintype "bidirectional"))
      (node (ref "U$121") (pin "GND") (pinfunction "GND_GND") (pintype "bidirectional"))
      (node (ref "U$122") (pin "GND") (pinfunction "GND_GND") (pintype "bidirectional"))
      (node (ref "U$123") (pin "GND") (pinfunction "GND_GND") (pintype "bidirectional"))
      (node (ref "U$124") (pin "GND") (pinfunction "GND_GND") (pintype "bidirectional"))
      (node (ref "U$125") (pin "GND") (pinfunction "GND_GND") (pintype "bidirectional"))
      (node (ref "U$126") (pin "GND") (pinfunction "GND_GND") (pintype "bidirectional"))
      (node (ref "U$127") (pin "GND") (pinfunction "GND_GND") (pintype "bidirectional"))
      (node (ref "U$128") (pin "GND") (pinfunction "GND_GND") (pintype "bidirectional"))
      (node (ref "U$129") (pin "GND") (pinfunction "GND_GND") (pintype "bidirectional"))
      (node (ref "U$13") (pin "GND") (pinfunction "GND_GND") (pintype "bidirectional"))
      (node (ref "U$130") (pin "GND") (pinfunction "GND_GND") (pintype "bidirectional"))
      (node (ref "U$131") (pin "1") (pinfunction "IC_1") (pintype "bidirectional"))
      (node (ref "U$131") (pin "12") (pinfunction "DGND_12") (pintype "bidirectional"))
      (node (ref "U$131") (pin "2") (pinfunction "IC_2") (pintype "bidirectional"))
      (node (ref "U$131") (pin "24") (pinfunction "IC_24") (pintype "bidirectional"))
      (node (ref "U$131") (pin "26") (pinfunction "IC_26") (pintype "bidirectional"))
      (node (ref "U$131") (pin "28") (pinfunction "AGND_28") (pintype "bidirectional"))
      (node (ref "U$131") (pin "3") (pinfunction "AGND_3") (pintype "bidirectional"))
      (node (ref "U$131") (pin "4") (pinfunction "IC_4") (pintype "bidirectional"))
      (node (ref "U$131") (pin "5") (pinfunction "IC_5") (pintype "bidirectional"))
      (node (ref "U$131") (pin "8") (pinfunction "AGND_8") (pintype "bidirectional"))
      (node (ref "U$131") (pin "THERMAL") (pinfunction "THERM_THERMAL") (pintype "bidirectional"))
      (node (ref "U$134") (pin "2") (pinfunction "GND_2") (pintype "bidirectional"))
      (node (ref "U$14") (pin "GND") (pinfunction "GND_GND") (pintype "bidirectional"))
      (node (ref "U$15") (pin "GND") (pinfunction "GND_GND") (pintype "bidirectional"))
      (node (ref "U$18") (pin "GND") (pinfunction "GND_GND") (pintype "bidirectional"))
      (node (ref "U$19") (pin "GND") (pinfunction "GND_GND") (pintype "bidirectional"))
      (node (ref "U$20") (pin "GND") (pinfunction "GND_GND") (pintype "bidirectional"))
      (node (ref "U$21") (pin "GND") (pinfunction "GND_GND") (pintype "bidirectional"))
      (node (ref "U$22") (pin "GND") (pinfunction "GND_GND") (pintype "bidirectional"))
      (node (ref "U$24") (pin "GND") (pinfunction "GND_GND") (pintype "bidirectional"))
      (node (ref "U$25") (pin "GND") (pinfunction "GND_GND") (pintype "bidirectional"))
      (node (ref "U$27") (pin "GND") (pinfunction "GND_GND") (pintype "bidirectional"))
      (node (ref "U$28") (pin "GND") (pinfunction "GND_GND") (pintype "bidirectional"))
      (node (ref "U$29") (pin "GND") (pinfunction "GND_GND") (pintype "bidirectional"))
      (node (ref "U$30") (pin "GND") (pinfunction "GND_GND") (pintype "bidirectional"))
      (node (ref "U$31") (pin "GND") (pinfunction "GND_GND") (pintype "bidirectional"))
      (node (ref "U$32") (pin "GND") (pinfunction "GND_GND") (pintype "bidirectional"))
      (node (ref "U$33") (pin "GND") (pinfunction "GND_GND") (pintype "bidirectional"))
      (node (ref "U$34") (pin "GND") (pinfunction "GND_GND") (pintype "bidirectional"))
      (node (ref "U$35") (pin "GND") (pinfunction "GND_GND") (pintype "bidirectional"))
      (node (ref "U$36") (pin "GND") (pinfunction "GND_GND") (pintype "bidirectional"))
      (node (ref "U$37") (pin "GND") (pinfunction "GND_GND") (pintype "bidirectional"))
      (node (ref "U$38") (pin "GND") (pinfunction "GND_GND") (pintype "bidirectional"))
      (node (ref "U$39") (pin "GND") (pinfunction "GND_GND") (pintype "bidirectional"))
      (node (ref "U$40") (pin "GND") (pinfunction "GND_GND") (pintype "bidirectional"))
      (node (ref "U$41") (pin "GND") (pinfunction "GND_GND") (pintype "bidirectional"))
      (node (ref "U$42") (pin "GND") (pinfunction "GND_GND") (pintype "bidirectional"))
      (node (ref "U$43") (pin "GND") (pinfunction "GND_GND") (pintype "bidirectional"))
      (node (ref "U$44") (pin "GND") (pinfunction "GND_GND") (pintype "bidirectional"))
      (node (ref "U$45") (pin "GND") (pinfunction "GND_GND") (pintype "bidirectional"))
      (node (ref "U$46") (pin "GND") (pinfunction "GND_GND") (pintype "bidirectional"))
      (node (ref "U$47") (pin "GND") (pinfunction "GND_GND") (pintype "bidirectional"))
      (node (ref "U$48") (pin "GND") (pinfunction "GND_GND") (pintype "bidirectional"))
      (node (ref "U$49") (pin "GND") (pinfunction "GND_GND") (pintype "bidirectional"))
      (node (ref "U$50") (pin "GND") (pinfunction "GND_GND") (pintype "bidirectional"))
      (node (ref "U$51") (pin "GND") (pinfunction "GND_GND") (pintype "bidirectional"))
      (node (ref "U$52") (pin "GND") (pinfunction "GND_GND") (pintype "bidirectional"))
      (node (ref "U$53") (pin "GND") (pinfunction "GND_GND") (pintype "bidirectional"))
      (node (ref "U$54") (pin "GND") (pinfunction "GND_GND") (pintype "bidirectional"))
      (node (ref "U$55") (pin "GND") (pinfunction "GND_GND") (pintype "bidirectional"))
      (node (ref "U$56") (pin "GND") (pinfunction "GND_GND") (pintype "bidirectional"))
      (node (ref "U$57") (pin "GND") (pinfunction "GND_GND") (pintype "bidirectional"))
      (node (ref "U$58") (pin "GND") (pinfunction "GND_GND") (pintype "bidirectional"))
      (node (ref "U$59") (pin "GND") (pinfunction "GND_GND") (pintype "bidirectional"))
      (node (ref "U$60") (pin "GND") (pinfunction "GND_GND") (pintype "bidirectional"))
      (node (ref "U$61") (pin "GND") (pinfunction "GND_GND") (pintype "bidirectional"))
      (node (ref "U$62") (pin "GND") (pinfunction "GND_GND") (pintype "bidirectional"))
      (node (ref "U$63") (pin "GND") (pinfunction "GND_GND") (pintype "bidirectional"))
      (node (ref "U$64") (pin "GND") (pinfunction "GND_GND") (pintype "bidirectional"))
      (node (ref "U$65") (pin "GND") (pinfunction "GND_GND") (pintype "bidirectional"))
      (node (ref "U$66") (pin "GND") (pinfunction "GND_GND") (pintype "bidirectional"))
      (node (ref "U$67") (pin "GND") (pinfunction "GND_GND") (pintype "bidirectional"))
      (node (ref "U$68") (pin "GND") (pinfunction "GND_GND") (pintype "bidirectional"))
      (node (ref "U$69") (pin "GND") (pinfunction "GND_GND") (pintype "bidirectional"))
      (node (ref "U$70") (pin "GND") (pinfunction "GND_GND") (pintype "bidirectional"))
      (node (ref "U$71") (pin "GND") (pinfunction "GND_GND") (pintype "bidirectional"))
      (node (ref "U$72") (pin "GND") (pinfunction "GND_GND") (pintype "bidirectional"))
      (node (ref "U$73") (pin "GND") (pinfunction "GND_GND") (pintype "bidirectional"))
      (node (ref "U$74") (pin "GND") (pinfunction "GND_GND") (pintype "bidirectional"))
      (node (ref "U$75") (pin "GND") (pinfunction "GND_GND") (pintype "bidirectional"))
      (node (ref "U$76") (pin "GND") (pinfunction "GND_GND") (pintype "bidirectional"))
      (node (ref "U$77") (pin "GND") (pinfunction "GND_GND") (pintype "bidirectional"))
      (node (ref "U$78") (pin "GND") (pinfunction "GND_GND") (pintype "bidirectional"))
      (node (ref "U$79") (pin "GND") (pinfunction "GND_GND") (pintype "bidirectional"))
      (node (ref "U$80") (pin "GND") (pinfunction "GND_GND") (pintype "bidirectional"))
      (node (ref "U$81") (pin "GND") (pinfunction "GND_GND") (pintype "bidirectional"))
      (node (ref "U$82") (pin "GND") (pinfunction "GND_GND") (pintype "bidirectional"))
      (node (ref "U$83") (pin "GND") (pinfunction "GND_GND") (pintype "bidirectional"))
      (node (ref "U$84") (pin "GND") (pinfunction "GND_GND") (pintype "bidirectional"))
      (node (ref "U$85") (pin "GND") (pinfunction "GND_GND") (pintype "bidirectional"))
      (node (ref "U$86") (pin "GND") (pinfunction "GND_GND") (pintype "bidirectional"))
      (node (ref "U$87") (pin "GND") (pinfunction "GND_GND") (pintype "bidirectional"))
      (node (ref "U$88") (pin "GND") (pinfunction "GND_GND") (pintype "bidirectional"))
      (node (ref "U$89") (pin "GND") (pinfunction "GND_GND") (pintype "bidirectional"))
      (node (ref "U$9") (pin "GND") (pinfunction "GND_GND") (pintype "bidirectional"))
      (node (ref "U$90") (pin "GND") (pinfunction "GND_GND") (pintype "bidirectional"))
      (node (ref "U$91") (pin "GND") (pinfunction "GND_GND") (pintype "bidirectional"))
      (node (ref "U$92") (pin "GND") (pinfunction "GND_GND") (pintype "bidirectional"))
      (node (ref "U$93") (pin "GND") (pinfunction "GND_GND") (pintype "bidirectional"))
      (node (ref "U$94") (pin "GND") (pinfunction "GND_GND") (pintype "bidirectional"))
      (node (ref "U$95") (pin "GND") (pinfunction "GND_GND") (pintype "bidirectional"))
      (node (ref "U$96") (pin "GND") (pinfunction "GND_GND") (pintype "bidirectional"))
      (node (ref "U$97") (pin "GND") (pinfunction "GND_GND") (pintype "bidirectional"))
      (node (ref "U$98") (pin "GND") (pinfunction "GND_GND") (pintype "bidirectional"))
      (node (ref "U$99") (pin "GND") (pinfunction "GND_GND") (pintype "bidirectional"))
      (node (ref "U1") (pin "16") (pinfunction "GND_16") (pintype "bidirectional"))
      (node (ref "U1") (pin "6") (pinfunction "GND_6") (pintype "bidirectional"))
      (node (ref "U2") (pin "1") (pinfunction "SDO/SA0_1") (pintype "bidirectional"))
      (node (ref "U2") (pin "2") (pinfunction "SDX_2") (pintype "bidirectional"))
      (node (ref "U2") (pin "3") (pinfunction "SCX_3") (pintype "bidirectional"))
      (node (ref "U2") (pin "6") (pinfunction "GND_6") (pintype "bidirectional"))
      (node (ref "U2") (pin "7") (pinfunction "GND_7") (pintype "bidirectional"))
      (node (ref "U3") (pin "2") (pinfunction "VSS_2") (pintype "power_in"))
      (node (ref "U8") (pin "2") (pinfunction "GND_2") (pintype "input"))
    )
    (net (code "21") (name "INTB") (class "Default")
      (node (ref "IC1") (pin "38") (pinfunction "IO19_38") (pintype "bidirectional"))
      (node (ref "U$131") (pin "21") (pinfunction "INTB_21") (pintype "bidirectional"))
    )
    (net (code "22") (name "IO12") (class "Default")
      (node (ref "IC1") (pin "18") (pinfunction "IO12_18") (pintype "power_in"))
    )
    (net (code "23") (name "LED_CLK") (class "Default")
      (node (ref "IC1") (pin "14") (pinfunction "IO25_14") (pintype "bidirectional"))
      (node (ref "U$9") (pin "C_IN") (pinfunction "CI_C_IN") (pintype "bidirectional"))
    )
    (net (code "24") (name "LED_DATA") (class "Default")
      (node (ref "IC1") (pin "15") (pinfunction "IO26_15") (pintype "bidirectional"))
      (node (ref "U$9") (pin "D_IN") (pinfunction "DI_D_IN") (pintype "bidirectional"))
    )
    (net (code "25") (name "MISO") (class "Default")
      (node (ref "IC1") (pin "11") (pinfunction "IO35_11") (pintype "bidirectional"))
      (node (ref "U$131") (pin "18") (pinfunction "SDO_18") (pintype "bidirectional"))
    )
    (net (code "26") (name "MOSI") (class "Default")
      (node (ref "IC1") (pin "36") (pinfunction "IO23_36") (pintype "bidirectional"))
      (node (ref "U$131") (pin "17") (pinfunction "SDI_17") (pintype "bidirectional"))
    )
    (net (code "27") (name "Net-(CHG2-PadA)") (class "Default")
      (node (ref "CHG2") (pin "A") (pinfunction "A_A") (pintype "passive"))
      (node (ref "R16") (pin "2") (pinfunction "2_2") (pintype "passive"))
    )
    (net (code "28") (name "Net-(E1-SIGNAL)") (class "Default")
      (node (ref "C48") (pin "1") (pinfunction "1_1") (pintype "passive"))
      (node (ref "C49") (pin "2") (pinfunction "2_2") (pintype "passive"))
      (node (ref "E1") (pin "ANT") (pinfunction "SIGNAL_ANT") (pintype "bidirectional"))
    )
    (net (code "29") (name "Net-(H1-MOUNT)") (class "Default")
      (node (ref "H1") (pin "B4,1") (pinfunction "MOUNT_B4,1") (pintype "passive"))
      (node (ref "R3") (pin "1") (pinfunction "1_1") (pintype "passive"))
      (node (ref "TP1") (pin "TP") (pinfunction "TP_TP") (pintype "input"))
    )
    (net (code "30") (name "Net-(H2-MOUNT)") (class "Default")
      (node (ref "H2") (pin "B4,1") (pinfunction "MOUNT_B4,1") (pintype "passive"))
      (node (ref "R6") (pin "1") (pinfunction "1_1") (pintype "passive"))
      (node (ref "TP2") (pin "TP") (pinfunction "TP_TP") (pintype "input"))
    )
    (net (code "31") (name "Net-(IC1A-LNA_IN)") (class "Default")
      (node (ref "C49") (pin "1") (pinfunction "1_1") (pintype "passive"))
      (node (ref "IC1") (pin "2") (pinfunction "LNA_IN_2") (pintype "bidirectional"))
      (node (ref "L1") (pin "1") (pinfunction "1_1") (pintype "passive"))
    )
    (net (code "32") (name "Net-(IC1A-VDD_SDIO_NC)") (class "Default")
      (node (ref "C8") (pin "1") (pinfunction "1_1") (pintype "passive"))
      (node (ref "IC1") (pin "26") (pinfunction "VDD_SDIO_NC_26") (pintype "bidirectional"))
    )
    (net (code "33") (name "Net-(Q1A-B)") (class "Default")
      (node (ref "Q1") (pin "5") (pinfunction "B_5") (pintype "passive"))
      (node (ref "R9") (pin "2") (pinfunction "2_2") (pintype "passive"))
    )
    (net (code "34") (name "Net-(Q1B-B)") (class "Default")
      (node (ref "Q1") (pin "2") (pinfunction "B_2") (pintype "passive"))
      (node (ref "R10") (pin "2") (pinfunction "2_2") (pintype "passive"))
    )
    (net (code "35") (name "Net-(U$10-CI)") (class "Default")
      (node (ref "U$10") (pin "C_IN") (pinfunction "CI_C_IN") (pintype "bidirectional"))
      (node (ref "U$9") (pin "CL_OUT") (pinfunction "CO_CL_OUT") (pintype "bidirectional"))
    )
    (net (code "36") (name "Net-(U$10-CO)") (class "Default")
      (node (ref "U$10") (pin "CL_OUT") (pinfunction "CO_CL_OUT") (pintype "bidirectional"))
      (node (ref "U$11") (pin "C_IN") (pinfunction "CI_C_IN") (pintype "bidirectional"))
    )
    (net (code "37") (name "Net-(U$10-DI)") (class "Default")
      (node (ref "U$10") (pin "D_IN") (pinfunction "DI_D_IN") (pintype "bidirectional"))
      (node (ref "U$9") (pin "D_OUT") (pinfunction "DO_D_OUT") (pintype "bidirectional"))
    )
    (net (code "38") (name "Net-(U$10-DO)") (class "Default")
      (node (ref "U$10") (pin "D_OUT") (pinfunction "DO_D_OUT") (pintype "bidirectional"))
      (node (ref "U$11") (pin "D_IN") (pinfunction "DI_D_IN") (pintype "bidirectional"))
    )
    (net (code "39") (name "Net-(U$11-CO)") (class "Default")
      (node (ref "U$11") (pin "CL_OUT") (pinfunction "CO_CL_OUT") (pintype "bidirectional"))
      (node (ref "U$12") (pin "C_IN") (pinfunction "CI_C_IN") (pintype "bidirectional"))
    )
    (net (code "40") (name "Net-(U$11-DO)") (class "Default")
      (node (ref "U$11") (pin "D_OUT") (pinfunction "DO_D_OUT") (pintype "bidirectional"))
      (node (ref "U$12") (pin "D_IN") (pinfunction "DI_D_IN") (pintype "bidirectional"))
    )
    (net (code "41") (name "Net-(U$12-CO)") (class "Default")
      (node (ref "U$12") (pin "CL_OUT") (pinfunction "CO_CL_OUT") (pintype "bidirectional"))
      (node (ref "U$13") (pin "C_IN") (pinfunction "CI_C_IN") (pintype "bidirectional"))
    )
    (net (code "42") (name "Net-(U$12-DO)") (class "Default")
      (node (ref "U$12") (pin "D_OUT") (pinfunction "DO_D_OUT") (pintype "bidirectional"))
      (node (ref "U$13") (pin "D_IN") (pinfunction "DI_D_IN") (pintype "bidirectional"))
    )
    (net (code "43") (name "Net-(U$13-CO)") (class "Default")
      (node (ref "U$13") (pin "CL_OUT") (pinfunction "CO_CL_OUT") (pintype "bidirectional"))
      (node (ref "U$14") (pin "C_IN") (pinfunction "CI_C_IN") (pintype "bidirectional"))
    )
    (net (code "44") (name "Net-(U$13-DO)") (class "Default")
      (node (ref "U$13") (pin "D_OUT") (pinfunction "DO_D_OUT") (pintype "bidirectional"))
      (node (ref "U$14") (pin "D_IN") (pinfunction "DI_D_IN") (pintype "bidirectional"))
    )
    (net (code "45") (name "Net-(U$14-CO)") (class "Default")
      (node (ref "U$14") (pin "CL_OUT") (pinfunction "CO_CL_OUT") (pintype "bidirectional"))
      (node (ref "U$15") (pin "C_IN") (pinfunction "CI_C_IN") (pintype "bidirectional"))
    )
    (net (code "46") (name "Net-(U$14-DO)") (class "Default")
      (node (ref "U$14") (pin "D_OUT") (pinfunction "DO_D_OUT") (pintype "bidirectional"))
      (node (ref "U$15") (pin "D_IN") (pinfunction "DI_D_IN") (pintype "bidirectional"))
    )
    (net (code "47") (name "Net-(U$15-CO)") (class "Default")
      (node (ref "U$15") (pin "CL_OUT") (pinfunction "CO_CL_OUT") (pintype "bidirectional"))
      (node (ref "U$18") (pin "C_IN") (pinfunction "CI_C_IN") (pintype "bidirectional"))
    )
    (net (code "48") (name "Net-(U$15-DO)") (class "Default")
      (node (ref "U$15") (pin "D_OUT") (pinfunction "DO_D_OUT") (pintype "bidirectional"))
      (node (ref "U$18") (pin "D_IN") (pinfunction "DI_D_IN") (pintype "bidirectional"))
    )
    (net (code "49") (name "Net-(U$18-CO)") (class "Default")
      (node (ref "U$18") (pin "CL_OUT") (pinfunction "CO_CL_OUT") (pintype "bidirectional"))
      (node (ref "U$19") (pin "C_IN") (pinfunction "CI_C_IN") (pintype "bidirectional"))
    )
    (net (code "50") (name "Net-(U$18-DO)") (class "Default")
      (node (ref "U$18") (pin "D_OUT") (pinfunction "DO_D_OUT") (pintype "bidirectional"))
      (node (ref "U$19") (pin "D_IN") (pinfunction "DI_D_IN") (pintype "bidirectional"))
    )
    (net (code "51") (name "Net-(U$19-CO)") (class "Default")
      (node (ref "U$19") (pin "CL_OUT") (pinfunction "CO_CL_OUT") (pintype "bidirectional"))
      (node (ref "U$20") (pin "C_IN") (pinfunction "CI_C_IN") (pintype "bidirectional"))
    )
    (net (code "52") (name "Net-(U$19-DO)") (class "Default")
      (node (ref "U$19") (pin "D_OUT") (pinfunction "DO_D_OUT") (pintype "bidirectional"))
      (node (ref "U$20") (pin "D_IN") (pinfunction "DI_D_IN") (pintype "bidirectional"))
    )
    (net (code "53") (name "Net-(U$20-CO)") (class "Default")
      (node (ref "U$20") (pin "CL_OUT") (pinfunction "CO_CL_OUT") (pintype "bidirectional"))
      (node (ref "U$21") (pin "C_IN") (pinfunction "CI_C_IN") (pintype "bidirectional"))
    )
    (net (code "54") (name "Net-(U$20-DO)") (class "Default")
      (node (ref "U$20") (pin "D_OUT") (pinfunction "DO_D_OUT") (pintype "bidirectional"))
      (node (ref "U$21") (pin "D_IN") (pinfunction "DI_D_IN") (pintype "bidirectional"))
    )
    (net (code "55") (name "Net-(U$21-CO)") (class "Default")
      (node (ref "U$21") (pin "CL_OUT") (pinfunction "CO_CL_OUT") (pintype "bidirectional"))
      (node (ref "U$22") (pin "C_IN") (pinfunction "CI_C_IN") (pintype "bidirectional"))
    )
    (net (code "56") (name "Net-(U$21-DO)") (class "Default")
      (node (ref "U$21") (pin "D_OUT") (pinfunction "DO_D_OUT") (pintype "bidirectional"))
      (node (ref "U$22") (pin "D_IN") (pinfunction "DI_D_IN") (pintype "bidirectional"))
    )
    (net (code "57") (name "Net-(U$22-CO)") (class "Default")
      (node (ref "U$22") (pin "CL_OUT") (pinfunction "CO_CL_OUT") (pintype "bidirectional"))
      (node (ref "U$24") (pin "C_IN") (pinfunction "CI_C_IN") (pintype "bidirectional"))
    )
    (net (code "58") (name "Net-(U$22-DO)") (class "Default")
      (node (ref "U$22") (pin "D_OUT") (pinfunction "DO_D_OUT") (pintype "bidirectional"))
      (node (ref "U$24") (pin "D_IN") (pinfunction "DI_D_IN") (pintype "bidirectional"))
    )
    (net (code "59") (name "Net-(U$24-CO)") (class "Default")
      (node (ref "U$24") (pin "CL_OUT") (pinfunction "CO_CL_OUT") (pintype "bidirectional"))
      (node (ref "U$25") (pin "C_IN") (pinfunction "CI_C_IN") (pintype "bidirectional"))
    )
    (net (code "60") (name "Net-(U$24-DO)") (class "Default")
      (node (ref "U$24") (pin "D_OUT") (pinfunction "DO_D_OUT") (pintype "bidirectional"))
      (node (ref "U$25") (pin "D_IN") (pinfunction "DI_D_IN") (pintype "bidirectional"))
    )
    (net (code "61") (name "Net-(U$25-CO)") (class "Default")
      (node (ref "U$25") (pin "CL_OUT") (pinfunction "CO_CL_OUT") (pintype "bidirectional"))
      (node (ref "U$27") (pin "C_IN") (pinfunction "CI_C_IN") (pintype "bidirectional"))
    )
    (net (code "62") (name "Net-(U$25-DO)") (class "Default")
      (node (ref "U$25") (pin "D_OUT") (pinfunction "DO_D_OUT") (pintype "bidirectional"))
      (node (ref "U$27") (pin "D_IN") (pinfunction "DI_D_IN") (pintype "bidirectional"))
    )
    (net (code "63") (name "Net-(U$27-CO)") (class "Default")
      (node (ref "U$27") (pin "CL_OUT") (pinfunction "CO_CL_OUT") (pintype "bidirectional"))
      (node (ref "U$28") (pin "C_IN") (pinfunction "CI_C_IN") (pintype "bidirectional"))
    )
    (net (code "64") (name "Net-(U$27-DO)") (class "Default")
      (node (ref "U$27") (pin "D_OUT") (pinfunction "DO_D_OUT") (pintype "bidirectional"))
      (node (ref "U$28") (pin "D_IN") (pinfunction "DI_D_IN") (pintype "bidirectional"))
    )
    (net (code "65") (name "Net-(U$28-CO)") (class "Default")
      (node (ref "U$28") (pin "CL_OUT") (pinfunction "CO_CL_OUT") (pintype "bidirectional"))
      (node (ref "U$29") (pin "C_IN") (pinfunction "CI_C_IN") (pintype "bidirectional"))
    )
    (net (code "66") (name "Net-(U$28-DO)") (class "Default")
      (node (ref "U$28") (pin "D_OUT") (pinfunction "DO_D_OUT") (pintype "bidirectional"))
      (node (ref "U$29") (pin "D_IN") (pinfunction "DI_D_IN") (pintype "bidirectional"))
    )
    (net (code "67") (name "Net-(U$29-CO)") (class "Default")
      (node (ref "U$29") (pin "CL_OUT") (pinfunction "CO_CL_OUT") (pintype "bidirectional"))
      (node (ref "U$30") (pin "C_IN") (pinfunction "CI_C_IN") (pintype "bidirectional"))
    )
    (net (code "68") (name "Net-(U$29-DO)") (class "Default")
      (node (ref "U$29") (pin "D_OUT") (pinfunction "DO_D_OUT") (pintype "bidirectional"))
      (node (ref "U$30") (pin "D_IN") (pinfunction "DI_D_IN") (pintype "bidirectional"))
    )
    (net (code "69") (name "Net-(U$30-CO)") (class "Default")
      (node (ref "U$30") (pin "CL_OUT") (pinfunction "CO_CL_OUT") (pintype "bidirectional"))
      (node (ref "U$31") (pin "C_IN") (pinfunction "CI_C_IN") (pintype "bidirectional"))
    )
    (net (code "70") (name "Net-(U$30-DO)") (class "Default")
      (node (ref "U$30") (pin "D_OUT") (pinfunction "DO_D_OUT") (pintype "bidirectional"))
      (node (ref "U$31") (pin "D_IN") (pinfunction "DI_D_IN") (pintype "bidirectional"))
    )
    (net (code "71") (name "Net-(U$32-CO)") (class "Default")
      (node (ref "U$32") (pin "CL_OUT") (pinfunction "CO_CL_OUT") (pintype "bidirectional"))
      (node (ref "U$33") (pin "C_IN") (pinfunction "CI_C_IN") (pintype "bidirectional"))
    )
    (net (code "72") (name "Net-(U$32-DO)") (class "Default")
      (node (ref "U$32") (pin "D_OUT") (pinfunction "DO_D_OUT") (pintype "bidirectional"))
      (node (ref "U$33") (pin "D_IN") (pinfunction "DI_D_IN") (pintype "bidirectional"))
    )
    (net (code "73") (name "Net-(U$33-CO)") (class "Default")
      (node (ref "U$33") (pin "CL_OUT") (pinfunction "CO_CL_OUT") (pintype "bidirectional"))
      (node (ref "U$34") (pin "C_IN") (pinfunction "CI_C_IN") (pintype "bidirectional"))
    )
    (net (code "74") (name "Net-(U$33-DO)") (class "Default")
      (node (ref "U$33") (pin "D_OUT") (pinfunction "DO_D_OUT") (pintype "bidirectional"))
      (node (ref "U$34") (pin "D_IN") (pinfunction "DI_D_IN") (pintype "bidirectional"))
    )
    (net (code "75") (name "Net-(U$34-CO)") (class "Default")
      (node (ref "U$34") (pin "CL_OUT") (pinfunction "CO_CL_OUT") (pintype "bidirectional"))
      (node (ref "U$35") (pin "C_IN") (pinfunction "CI_C_IN") (pintype "bidirectional"))
    )
    (net (code "76") (name "Net-(U$34-DO)") (class "Default")
      (node (ref "U$34") (pin "D_OUT") (pinfunction "DO_D_OUT") (pintype "bidirectional"))
      (node (ref "U$35") (pin "D_IN") (pinfunction "DI_D_IN") (pintype "bidirectional"))
    )
    (net (code "77") (name "Net-(U$35-CO)") (class "Default")
      (node (ref "U$35") (pin "CL_OUT") (pinfunction "CO_CL_OUT") (pintype "bidirectional"))
      (node (ref "U$36") (pin "C_IN") (pinfunction "CI_C_IN") (pintype "bidirectional"))
    )
    (net (code "78") (name "Net-(U$35-DO)") (class "Default")
      (node (ref "U$35") (pin "D_OUT") (pinfunction "DO_D_OUT") (pintype "bidirectional"))
      (node (ref "U$36") (pin "D_IN") (pinfunction "DI_D_IN") (pintype "bidirectional"))
    )
    (net (code "79") (name "Net-(U$36-CO)") (class "Default")
      (node (ref "U$36") (pin "CL_OUT") (pinfunction "CO_CL_OUT") (pintype "bidirectional"))
      (node (ref "U$37") (pin "C_IN") (pinfunction "CI_C_IN") (pintype "bidirectional"))
    )
    (net (code "80") (name "Net-(U$36-DO)") (class "Default")
      (node (ref "U$36") (pin "D_OUT") (pinfunction "DO_D_OUT") (pintype "bidirectional"))
      (node (ref "U$37") (pin "D_IN") (pinfunction "DI_D_IN") (pintype "bidirectional"))
    )
    (net (code "81") (name "Net-(U$37-CO)") (class "Default")
      (node (ref "U$37") (pin "CL_OUT") (pinfunction "CO_CL_OUT") (pintype "bidirectional"))
      (node (ref "U$38") (pin "C_IN") (pinfunction "CI_C_IN") (pintype "bidirectional"))
    )
    (net (code "82") (name "Net-(U$37-DO)") (class "Default")
      (node (ref "U$37") (pin "D_OUT") (pinfunction "DO_D_OUT") (pintype "bidirectional"))
      (node (ref "U$38") (pin "D_IN") (pinfunction "DI_D_IN") (pintype "bidirectional"))
    )
    (net (code "83") (name "Net-(U$38-CO)") (class "Default")
      (node (ref "U$38") (pin "CL_OUT") (pinfunction "CO_CL_OUT") (pintype "bidirectional"))
      (node (ref "U$39") (pin "C_IN") (pinfunction "CI_C_IN") (pintype "bidirectional"))
    )
    (net (code "84") (name "Net-(U$38-DO)") (class "Default")
      (node (ref "U$38") (pin "D_OUT") (pinfunction "DO_D_OUT") (pintype "bidirectional"))
      (node (ref "U$39") (pin "D_IN") (pinfunction "DI_D_IN") (pintype "bidirectional"))
    )
    (net (code "85") (name "Net-(U$39-CO)") (class "Default")
      (node (ref "U$39") (pin "CL_OUT") (pinfunction "CO_CL_OUT") (pintype "bidirectional"))
      (node (ref "U$40") (pin "C_IN") (pinfunction "CI_C_IN") (pintype "bidirectional"))
    )
    (net (code "86") (name "Net-(U$39-DO)") (class "Default")
      (node (ref "U$39") (pin "D_OUT") (pinfunction "DO_D_OUT") (pintype "bidirectional"))
      (node (ref "U$40") (pin "D_IN") (pinfunction "DI_D_IN") (pintype "bidirectional"))
    )
    (net (code "87") (name "Net-(U$40-CO)") (class "Default")
      (node (ref "U$40") (pin "CL_OUT") (pinfunction "CO_CL_OUT") (pintype "bidirectional"))
      (node (ref "U$41") (pin "C_IN") (pinfunction "CI_C_IN") (pintype "bidirectional"))
    )
    (net (code "88") (name "Net-(U$40-DO)") (class "Default")
      (node (ref "U$40") (pin "D_OUT") (pinfunction "DO_D_OUT") (pintype "bidirectional"))
      (node (ref "U$41") (pin "D_IN") (pinfunction "DI_D_IN") (pintype "bidirectional"))
    )
    (net (code "89") (name "Net-(U$41-CO)") (class "Default")
      (node (ref "U$41") (pin "CL_OUT") (pinfunction "CO_CL_OUT") (pintype "bidirectional"))
      (node (ref "U$42") (pin "C_IN") (pinfunction "CI_C_IN") (pintype "bidirectional"))
    )
    (net (code "90") (name "Net-(U$41-DO)") (class "Default")
      (node (ref "U$41") (pin "D_OUT") (pinfunction "DO_D_OUT") (pintype "bidirectional"))
      (node (ref "U$42") (pin "D_IN") (pinfunction "DI_D_IN") (pintype "bidirectional"))
    )
    (net (code "91") (name "Net-(U$42-CO)") (class "Default")
      (node (ref "U$42") (pin "CL_OUT") (pinfunction "CO_CL_OUT") (pintype "bidirectional"))
      (node (ref "U$43") (pin "C_IN") (pinfunction "CI_C_IN") (pintype "bidirectional"))
    )
    (net (code "92") (name "Net-(U$42-DO)") (class "Default")
      (node (ref "U$42") (pin "D_OUT") (pinfunction "DO_D_OUT") (pintype "bidirectional"))
      (node (ref "U$43") (pin "D_IN") (pinfunction "DI_D_IN") (pintype "bidirectional"))
    )
    (net (code "93") (name "Net-(U$43-CO)") (class "Default")
      (node (ref "U$43") (pin "CL_OUT") (pinfunction "CO_CL_OUT") (pintype "bidirectional"))
      (node (ref "U$44") (pin "C_IN") (pinfunction "CI_C_IN") (pintype "bidirectional"))
    )
    (net (code "94") (name "Net-(U$43-DO)") (class "Default")
      (node (ref "U$43") (pin "D_OUT") (pinfunction "DO_D_OUT") (pintype "bidirectional"))
      (node (ref "U$44") (pin "D_IN") (pinfunction "DI_D_IN") (pintype "bidirectional"))
    )
    (net (code "95") (name "Net-(U$44-CO)") (class "Default")
      (node (ref "U$44") (pin "CL_OUT") (pinfunction "CO_CL_OUT") (pintype "bidirectional"))
      (node (ref "U$45") (pin "C_IN") (pinfunction "CI_C_IN") (pintype "bidirectional"))
    )
    (net (code "96") (name "Net-(U$44-DO)") (class "Default")
      (node (ref "U$44") (pin "D_OUT") (pinfunction "DO_D_OUT") (pintype "bidirectional"))
      (node (ref "U$45") (pin "D_IN") (pinfunction "DI_D_IN") (pintype "bidirectional"))
    )
    (net (code "97") (name "Net-(U$45-CO)") (class "Default")
      (node (ref "U$45") (pin "CL_OUT") (pinfunction "CO_CL_OUT") (pintype "bidirectional"))
      (node (ref "U$46") (pin "C_IN") (pinfunction "CI_C_IN") (pintype "bidirectional"))
    )
    (net (code "98") (name "Net-(U$45-DO)") (class "Default")
      (node (ref "U$45") (pin "D_OUT") (pinfunction "DO_D_OUT") (pintype "bidirectional"))
      (node (ref "U$46") (pin "D_IN") (pinfunction "DI_D_IN") (pintype "bidirectional"))
    )
    (net (code "99") (name "Net-(U$46-CO)") (class "Default")
      (node (ref "U$46") (pin "CL_OUT") (pinfunction "CO_CL_OUT") (pintype "bidirectional"))
      (node (ref "U$47") (pin "C_IN") (pinfunction "CI_C_IN") (pintype "bidirectional"))
    )
    (net (code "100") (name "Net-(U$46-DO)") (class "Default")
      (node (ref "U$46") (pin "D_OUT") (pinfunction "DO_D_OUT") (pintype "bidirectional"))
      (node (ref "U$47") (pin "D_IN") (pinfunction "DI_D_IN") (pintype "bidirectional"))
    )
    (net (code "101") (name "Net-(U$47-CO)") (class "Default")
      (node (ref "U$47") (pin "CL_OUT") (pinfunction "CO_CL_OUT") (pintype "bidirectional"))
      (node (ref "U$48") (pin "C_IN") (pinfunction "CI_C_IN") (pintype "bidirectional"))
    )
    (net (code "102") (name "Net-(U$47-DO)") (class "Default")
      (node (ref "U$47") (pin "D_OUT") (pinfunction "DO_D_OUT") (pintype "bidirectional"))
      (node (ref "U$48") (pin "D_IN") (pinfunction "DI_D_IN") (pintype "bidirectional"))
    )
    (net (code "103") (name "Net-(U$48-CO)") (class "Default")
      (node (ref "U$48") (pin "CL_OUT") (pinfunction "CO_CL_OUT") (pintype "bidirectional"))
      (node (ref "U$49") (pin "C_IN") (pinfunction "CI_C_IN") (pintype "bidirectional"))
    )
    (net (code "104") (name "Net-(U$48-DO)") (class "Default")
      (node (ref "U$48") (pin "D_OUT") (pinfunction "DO_D_OUT") (pintype "bidirectional"))
      (node (ref "U$49") (pin "D_IN") (pinfunction "DI_D_IN") (pintype "bidirectional"))
    )
    (net (code "105") (name "Net-(U$49-CO)") (class "Default")
      (node (ref "U$49") (pin "CL_OUT") (pinfunction "CO_CL_OUT") (pintype "bidirectional"))
      (node (ref "U$50") (pin "C_IN") (pinfunction "CI_C_IN") (pintype "bidirectional"))
    )
    (net (code "106") (name "Net-(U$49-DO)") (class "Default")
      (node (ref "U$49") (pin "D_OUT") (pinfunction "DO_D_OUT") (pintype "bidirectional"))
      (node (ref "U$50") (pin "D_IN") (pinfunction "DI_D_IN") (pintype "bidirectional"))
    )
    (net (code "107") (name "Net-(U$50-CO)") (class "Default")
      (node (ref "U$50") (pin "CL_OUT") (pinfunction "CO_CL_OUT") (pintype "bidirectional"))
      (node (ref "U$51") (pin "C_IN") (pinfunction "CI_C_IN") (pintype "bidirectional"))
    )
    (net (code "108") (name "Net-(U$50-DO)") (class "Default")
      (node (ref "U$50") (pin "D_OUT") (pinfunction "DO_D_OUT") (pintype "bidirectional"))
      (node (ref "U$51") (pin "D_IN") (pinfunction "DI_D_IN") (pintype "bidirectional"))
    )
    (net (code "109") (name "Net-(U$51-CO)") (class "Default")
      (node (ref "U$51") (pin "CL_OUT") (pinfunction "CO_CL_OUT") (pintype "bidirectional"))
      (node (ref "U$52") (pin "C_IN") (pinfunction "CI_C_IN") (pintype "bidirectional"))
    )
    (net (code "110") (name "Net-(U$51-DO)") (class "Default")
      (node (ref "U$51") (pin "D_OUT") (pinfunction "DO_D_OUT") (pintype "bidirectional"))
      (node (ref "U$52") (pin "D_IN") (pinfunction "DI_D_IN") (pintype "bidirectional"))
    )
    (net (code "111") (name "Net-(U$52-CO)") (class "Default")
      (node (ref "U$52") (pin "CL_OUT") (pinfunction "CO_CL_OUT") (pintype "bidirectional"))
      (node (ref "U$53") (pin "C_IN") (pinfunction "CI_C_IN") (pintype "bidirectional"))
    )
    (net (code "112") (name "Net-(U$52-DO)") (class "Default")
      (node (ref "U$52") (pin "D_OUT") (pinfunction "DO_D_OUT") (pintype "bidirectional"))
      (node (ref "U$53") (pin "D_IN") (pinfunction "DI_D_IN") (pintype "bidirectional"))
    )
    (net (code "113") (name "Net-(U$53-CO)") (class "Default")
      (node (ref "U$53") (pin "CL_OUT") (pinfunction "CO_CL_OUT") (pintype "bidirectional"))
      (node (ref "U$54") (pin "C_IN") (pinfunction "CI_C_IN") (pintype "bidirectional"))
    )
    (net (code "114") (name "Net-(U$53-DO)") (class "Default")
      (node (ref "U$53") (pin "D_OUT") (pinfunction "DO_D_OUT") (pintype "bidirectional"))
      (node (ref "U$54") (pin "D_IN") (pinfunction "DI_D_IN") (pintype "bidirectional"))
    )
    (net (code "115") (name "Net-(U$54-CO)") (class "Default")
      (node (ref "U$54") (pin "CL_OUT") (pinfunction "CO_CL_OUT") (pintype "bidirectional"))
      (node (ref "U$55") (pin "C_IN") (pinfunction "CI_C_IN") (pintype "bidirectional"))
    )
    (net (code "116") (name "Net-(U$54-DO)") (class "Default")
      (node (ref "U$54") (pin "D_OUT") (pinfunction "DO_D_OUT") (pintype "bidirectional"))
      (node (ref "U$55") (pin "D_IN") (pinfunction "DI_D_IN") (pintype "bidirectional"))
    )
    (net (code "117") (name "Net-(U$55-CO)") (class "Default")
      (node (ref "U$55") (pin "CL_OUT") (pinfunction "CO_CL_OUT") (pintype "bidirectional"))
      (node (ref "U$56") (pin "C_IN") (pinfunction "CI_C_IN") (pintype "bidirectional"))
    )
    (net (code "118") (name "Net-(U$55-DO)") (class "Default")
      (node (ref "U$55") (pin "D_OUT") (pinfunction "DO_D_OUT") (pintype "bidirectional"))
      (node (ref "U$56") (pin "D_IN") (pinfunction "DI_D_IN") (pintype "bidirectional"))
    )
    (net (code "119") (name "Net-(U$56-CO)") (class "Default")
      (node (ref "U$56") (pin "CL_OUT") (pinfunction "CO_CL_OUT") (pintype "bidirectional"))
      (node (ref "U$57") (pin "C_IN") (pinfunction "CI_C_IN") (pintype "bidirectional"))
    )
    (net (code "120") (name "Net-(U$56-DO)") (class "Default")
      (node (ref "U$56") (pin "D_OUT") (pinfunction "DO_D_OUT") (pintype "bidirectional"))
      (node (ref "U$57") (pin "D_IN") (pinfunction "DI_D_IN") (pintype "bidirectional"))
    )
    (net (code "121") (name "Net-(U$57-CO)") (class "Default")
      (node (ref "U$57") (pin "CL_OUT") (pinfunction "CO_CL_OUT") (pintype "bidirectional"))
      (node (ref "U$58") (pin "C_IN") (pinfunction "CI_C_IN") (pintype "bidirectional"))
    )
    (net (code "122") (name "Net-(U$57-DO)") (class "Default")
      (node (ref "U$57") (pin "D_OUT") (pinfunction "DO_D_OUT") (pintype "bidirectional"))
      (node (ref "U$58") (pin "D_IN") (pinfunction "DI_D_IN") (pintype "bidirectional"))
    )
    (net (code "123") (name "Net-(U$58-CO)") (class "Default")
      (node (ref "U$58") (pin "CL_OUT") (pinfunction "CO_CL_OUT") (pintype "bidirectional"))
      (node (ref "U$59") (pin "C_IN") (pinfunction "CI_C_IN") (pintype "bidirectional"))
    )
    (net (code "124") (name "Net-(U$58-DO)") (class "Default")
      (node (ref "U$58") (pin "D_OUT") (pinfunction "DO_D_OUT") (pintype "bidirectional"))
      (node (ref "U$59") (pin "D_IN") (pinfunction "DI_D_IN") (pintype "bidirectional"))
    )
    (net (code "125") (name "Net-(U$59-CO)") (class "Default")
      (node (ref "U$59") (pin "CL_OUT") (pinfunction "CO_CL_OUT") (pintype "bidirectional"))
      (node (ref "U$60") (pin "C_IN") (pinfunction "CI_C_IN") (pintype "bidirectional"))
    )
    (net (code "126") (name "Net-(U$59-DO)") (class "Default")
      (node (ref "U$59") (pin "D_OUT") (pinfunction "DO_D_OUT") (pintype "bidirectional"))
      (node (ref "U$60") (pin "D_IN") (pinfunction "DI_D_IN") (pintype "bidirectional"))
    )
    (net (code "127") (name "Net-(U$60-CO)") (class "Default")
      (node (ref "U$60") (pin "CL_OUT") (pinfunction "CO_CL_OUT") (pintype "bidirectional"))
      (node (ref "U$61") (pin "C_IN") (pinfunction "CI_C_IN") (pintype "bidirectional"))
    )
    (net (code "128") (name "Net-(U$60-DO)") (class "Default")
      (node (ref "U$60") (pin "D_OUT") (pinfunction "DO_D_OUT") (pintype "bidirectional"))
      (node (ref "U$61") (pin "D_IN") (pinfunction "DI_D_IN") (pintype "bidirectional"))
    )
    (net (code "129") (name "Net-(U$61-CO)") (class "Default")
      (node (ref "U$61") (pin "CL_OUT") (pinfunction "CO_CL_OUT") (pintype "bidirectional"))
      (node (ref "U$62") (pin "C_IN") (pinfunction "CI_C_IN") (pintype "bidirectional"))
    )
    (net (code "130") (name "Net-(U$61-DO)") (class "Default")
      (node (ref "U$61") (pin "D_OUT") (pinfunction "DO_D_OUT") (pintype "bidirectional"))
      (node (ref "U$62") (pin "D_IN") (pinfunction "DI_D_IN") (pintype "bidirectional"))
    )
    (net (code "131") (name "Net-(U$62-CO)") (class "Default")
      (node (ref "U$62") (pin "CL_OUT") (pinfunction "CO_CL_OUT") (pintype "bidirectional"))
      (node (ref "U$63") (pin "C_IN") (pinfunction "CI_C_IN") (pintype "bidirectional"))
    )
    (net (code "132") (name "Net-(U$62-DO)") (class "Default")
      (node (ref "U$62") (pin "D_OUT") (pinfunction "DO_D_OUT") (pintype "bidirectional"))
      (node (ref "U$63") (pin "D_IN") (pinfunction "DI_D_IN") (pintype "bidirectional"))
    )
    (net (code "133") (name "Net-(U$63-CO)") (class "Default")
      (node (ref "U$63") (pin "CL_OUT") (pinfunction "CO_CL_OUT") (pintype "bidirectional"))
      (node (ref "U$64") (pin "C_IN") (pinfunction "CI_C_IN") (pintype "bidirectional"))
    )
    (net (code "134") (name "Net-(U$63-DO)") (class "Default")
      (node (ref "U$63") (pin "D_OUT") (pinfunction "DO_D_OUT") (pintype "bidirectional"))
      (node (ref "U$64") (pin "D_IN") (pinfunction "DI_D_IN") (pintype "bidirectional"))
    )
    (net (code "135") (name "Net-(U$64-CO)") (class "Default")
      (node (ref "U$64") (pin "CL_OUT") (pinfunction "CO_CL_OUT") (pintype "bidirectional"))
      (node (ref "U$65") (pin "C_IN") (pinfunction "CI_C_IN") (pintype "bidirectional"))
    )
    (net (code "136") (name "Net-(U$64-DO)") (class "Default")
      (node (ref "U$64") (pin "D_OUT") (pinfunction "DO_D_OUT") (pintype "bidirectional"))
      (node (ref "U$65") (pin "D_IN") (pinfunction "DI_D_IN") (pintype "bidirectional"))
    )
    (net (code "137") (name "Net-(U$65-CO)") (class "Default")
      (node (ref "U$65") (pin "CL_OUT") (pinfunction "CO_CL_OUT") (pintype "bidirectional"))
      (node (ref "U$66") (pin "C_IN") (pinfunction "CI_C_IN") (pintype "bidirectional"))
    )
    (net (code "138") (name "Net-(U$65-DO)") (class "Default")
      (node (ref "U$65") (pin "D_OUT") (pinfunction "DO_D_OUT") (pintype "bidirectional"))
      (node (ref "U$66") (pin "D_IN") (pinfunction "DI_D_IN") (pintype "bidirectional"))
    )
    (net (code "139") (name "Net-(U$66-CO)") (class "Default")
      (node (ref "U$66") (pin "CL_OUT") (pinfunction "CO_CL_OUT") (pintype "bidirectional"))
      (node (ref "U$67") (pin "C_IN") (pinfunction "CI_C_IN") (pintype "bidirectional"))
    )
    (net (code "140") (name "Net-(U$66-DO)") (class "Default")
      (node (ref "U$66") (pin "D_OUT") (pinfunction "DO_D_OUT") (pintype "bidirectional"))
      (node (ref "U$67") (pin "D_IN") (pinfunction "DI_D_IN") (pintype "bidirectional"))
    )
    (net (code "141") (name "Net-(U$67-CO)") (class "Default")
      (node (ref "U$67") (pin "CL_OUT") (pinfunction "CO_CL_OUT") (pintype "bidirectional"))
      (node (ref "U$68") (pin "C_IN") (pinfunction "CI_C_IN") (pintype "bidirectional"))
    )
    (net (code "142") (name "Net-(U$67-DO)") (class "Default")
      (node (ref "U$67") (pin "D_OUT") (pinfunction "DO_D_OUT") (pintype "bidirectional"))
      (node (ref "U$68") (pin "D_IN") (pinfunction "DI_D_IN") (pintype "bidirectional"))
    )
    (net (code "143") (name "Net-(U$68-CO)") (class "Default")
      (node (ref "U$68") (pin "CL_OUT") (pinfunction "CO_CL_OUT") (pintype "bidirectional"))
      (node (ref "U$69") (pin "C_IN") (pinfunction "CI_C_IN") (pintype "bidirectional"))
    )
    (net (code "144") (name "Net-(U$68-DO)") (class "Default")
      (node (ref "U$68") (pin "D_OUT") (pinfunction "DO_D_OUT") (pintype "bidirectional"))
      (node (ref "U$69") (pin "D_IN") (pinfunction "DI_D_IN") (pintype "bidirectional"))
    )
    (net (code "145") (name "Net-(U$69-CO)") (class "Default")
      (node (ref "U$69") (pin "CL_OUT") (pinfunction "CO_CL_OUT") (pintype "bidirectional"))
      (node (ref "U$70") (pin "C_IN") (pinfunction "CI_C_IN") (pintype "bidirectional"))
    )
    (net (code "146") (name "Net-(U$69-DO)") (class "Default")
      (node (ref "U$69") (pin "D_OUT") (pinfunction "DO_D_OUT") (pintype "bidirectional"))
      (node (ref "U$70") (pin "D_IN") (pinfunction "DI_D_IN") (pintype "bidirectional"))
    )
    (net (code "147") (name "Net-(U$70-CO)") (class "Default")
      (node (ref "U$70") (pin "CL_OUT") (pinfunction "CO_CL_OUT") (pintype "bidirectional"))
      (node (ref "U$71") (pin "C_IN") (pinfunction "CI_C_IN") (pintype "bidirectional"))
    )
    (net (code "148") (name "Net-(U$70-DO)") (class "Default")
      (node (ref "U$70") (pin "D_OUT") (pinfunction "DO_D_OUT") (pintype "bidirectional"))
      (node (ref "U$71") (pin "D_IN") (pinfunction "DI_D_IN") (pintype "bidirectional"))
    )
    (net (code "149") (name "Net-(U$71-CO)") (class "Default")
      (node (ref "U$71") (pin "CL_OUT") (pinfunction "CO_CL_OUT") (pintype "bidirectional"))
      (node (ref "U$72") (pin "C_IN") (pinfunction "CI_C_IN") (pintype "bidirectional"))
    )
    (net (code "150") (name "Net-(U$71-DO)") (class "Default")
      (node (ref "U$71") (pin "D_OUT") (pinfunction "DO_D_OUT") (pintype "bidirectional"))
      (node (ref "U$72") (pin "D_IN") (pinfunction "DI_D_IN") (pintype "bidirectional"))
    )
    (net (code "151") (name "Net-(U$72-CO)") (class "Default")
      (node (ref "U$72") (pin "CL_OUT") (pinfunction "CO_CL_OUT") (pintype "bidirectional"))
      (node (ref "U$73") (pin "C_IN") (pinfunction "CI_C_IN") (pintype "bidirectional"))
    )
    (net (code "152") (name "Net-(U$72-DO)") (class "Default")
      (node (ref "U$72") (pin "D_OUT") (pinfunction "DO_D_OUT") (pintype "bidirectional"))
      (node (ref "U$73") (pin "D_IN") (pinfunction "DI_D_IN") (pintype "bidirectional"))
    )
    (net (code "153") (name "Net-(U$73-CO)") (class "Default")
      (node (ref "U$73") (pin "CL_OUT") (pinfunction "CO_CL_OUT") (pintype "bidirectional"))
      (node (ref "U$74") (pin "C_IN") (pinfunction "CI_C_IN") (pintype "bidirectional"))
    )
    (net (code "154") (name "Net-(U$73-DO)") (class "Default")
      (node (ref "U$73") (pin "D_OUT") (pinfunction "DO_D_OUT") (pintype "bidirectional"))
      (node (ref "U$74") (pin "D_IN") (pinfunction "DI_D_IN") (pintype "bidirectional"))
    )
    (net (code "155") (name "Net-(U$74-CO)") (class "Default")
      (node (ref "U$74") (pin "CL_OUT") (pinfunction "CO_CL_OUT") (pintype "bidirectional"))
      (node (ref "U$75") (pin "C_IN") (pinfunction "CI_C_IN") (pintype "bidirectional"))
    )
    (net (code "156") (name "Net-(U$74-DO)") (class "Default")
      (node (ref "U$74") (pin "D_OUT") (pinfunction "DO_D_OUT") (pintype "bidirectional"))
      (node (ref "U$75") (pin "D_IN") (pinfunction "DI_D_IN") (pintype "bidirectional"))
    )
    (net (code "157") (name "Net-(U$75-CO)") (class "Default")
      (node (ref "U$75") (pin "CL_OUT") (pinfunction "CO_CL_OUT") (pintype "bidirectional"))
      (node (ref "U$76") (pin "C_IN") (pinfunction "CI_C_IN") (pintype "bidirectional"))
    )
    (net (code "158") (name "Net-(U$75-DO)") (class "Default")
      (node (ref "U$75") (pin "D_OUT") (pinfunction "DO_D_OUT") (pintype "bidirectional"))
      (node (ref "U$76") (pin "D_IN") (pinfunction "DI_D_IN") (pintype "bidirectional"))
    )
    (net (code "159") (name "Net-(U$76-CO)") (class "Default")
      (node (ref "U$76") (pin "CL_OUT") (pinfunction "CO_CL_OUT") (pintype "bidirectional"))
      (node (ref "U$77") (pin "C_IN") (pinfunction "CI_C_IN") (pintype "bidirectional"))
    )
    (net (code "160") (name "Net-(U$76-DO)") (class "Default")
      (node (ref "U$76") (pin "D_OUT") (pinfunction "DO_D_OUT") (pintype "bidirectional"))
      (node (ref "U$77") (pin "D_IN") (pinfunction "DI_D_IN") (pintype "bidirectional"))
    )
    (net (code "161") (name "Net-(U$77-CO)") (class "Default")
      (node (ref "U$77") (pin "CL_OUT") (pinfunction "CO_CL_OUT") (pintype "bidirectional"))
      (node (ref "U$78") (pin "C_IN") (pinfunction "CI_C_IN") (pintype "bidirectional"))
    )
    (net (code "162") (name "Net-(U$77-DO)") (class "Default")
      (node (ref "U$77") (pin "D_OUT") (pinfunction "DO_D_OUT") (pintype "bidirectional"))
      (node (ref "U$78") (pin "D_IN") (pinfunction "DI_D_IN") (pintype "bidirectional"))
    )
    (net (code "163") (name "Net-(U$78-CO)") (class "Default")
      (node (ref "U$78") (pin "CL_OUT") (pinfunction "CO_CL_OUT") (pintype "bidirectional"))
      (node (ref "U$79") (pin "C_IN") (pinfunction "CI_C_IN") (pintype "bidirectional"))
    )
    (net (code "164") (name "Net-(U$78-DO)") (class "Default")
      (node (ref "U$78") (pin "D_OUT") (pinfunction "DO_D_OUT") (pintype "bidirectional"))
      (node (ref "U$79") (pin "D_IN") (pinfunction "DI_D_IN") (pintype "bidirectional"))
    )
    (net (code "165") (name "Net-(U$79-CO)") (class "Default")
      (node (ref "U$79") (pin "CL_OUT") (pinfunction "CO_CL_OUT") (pintype "bidirectional"))
      (node (ref "U$80") (pin "C_IN") (pinfunction "CI_C_IN") (pintype "bidirectional"))
    )
    (net (code "166") (name "Net-(U$79-DO)") (class "Default")
      (node (ref "U$79") (pin "D_OUT") (pinfunction "DO_D_OUT") (pintype "bidirectional"))
      (node (ref "U$80") (pin "D_IN") (pinfunction "DI_D_IN") (pintype "bidirectional"))
    )
    (net (code "167") (name "Net-(U$80-CO)") (class "Default")
      (node (ref "U$80") (pin "CL_OUT") (pinfunction "CO_CL_OUT") (pintype "bidirectional"))
      (node (ref "U$81") (pin "C_IN") (pinfunction "CI_C_IN") (pintype "bidirectional"))
    )
    (net (code "168") (name "Net-(U$80-DO)") (class "Default")
      (node (ref "U$80") (pin "D_OUT") (pinfunction "DO_D_OUT") (pintype "bidirectional"))
      (node (ref "U$81") (pin "D_IN") (pinfunction "DI_D_IN") (pintype "bidirectional"))
    )
    (net (code "169") (name "Net-(U$81-CO)") (class "Default")
      (node (ref "U$81") (pin "CL_OUT") (pinfunction "CO_CL_OUT") (pintype "bidirectional"))
      (node (ref "U$82") (pin "C_IN") (pinfunction "CI_C_IN") (pintype "bidirectional"))
    )
    (net (code "170") (name "Net-(U$81-DO)") (class "Default")
      (node (ref "U$81") (pin "D_OUT") (pinfunction "DO_D_OUT") (pintype "bidirectional"))
      (node (ref "U$82") (pin "D_IN") (pinfunction "DI_D_IN") (pintype "bidirectional"))
    )
    (net (code "171") (name "Net-(U$82-CO)") (class "Default")
      (node (ref "U$82") (pin "CL_OUT") (pinfunction "CO_CL_OUT") (pintype "bidirectional"))
      (node (ref "U$83") (pin "C_IN") (pinfunction "CI_C_IN") (pintype "bidirectional"))
    )
    (net (code "172") (name "Net-(U$82-DO)") (class "Default")
      (node (ref "U$82") (pin "D_OUT") (pinfunction "DO_D_OUT") (pintype "bidirectional"))
      (node (ref "U$83") (pin "D_IN") (pinfunction "DI_D_IN") (pintype "bidirectional"))
    )
    (net (code "173") (name "Net-(U$83-CO)") (class "Default")
      (node (ref "U$83") (pin "CL_OUT") (pinfunction "CO_CL_OUT") (pintype "bidirectional"))
      (node (ref "U$84") (pin "C_IN") (pinfunction "CI_C_IN") (pintype "bidirectional"))
    )
    (net (code "174") (name "Net-(U$83-DO)") (class "Default")
      (node (ref "U$83") (pin "D_OUT") (pinfunction "DO_D_OUT") (pintype "bidirectional"))
      (node (ref "U$84") (pin "D_IN") (pinfunction "DI_D_IN") (pintype "bidirectional"))
    )
    (net (code "175") (name "Net-(U$84-CO)") (class "Default")
      (node (ref "U$84") (pin "CL_OUT") (pinfunction "CO_CL_OUT") (pintype "bidirectional"))
      (node (ref "U$85") (pin "C_IN") (pinfunction "CI_C_IN") (pintype "bidirectional"))
    )
    (net (code "176") (name "Net-(U$84-DO)") (class "Default")
      (node (ref "U$84") (pin "D_OUT") (pinfunction "DO_D_OUT") (pintype "bidirectional"))
      (node (ref "U$85") (pin "D_IN") (pinfunction "DI_D_IN") (pintype "bidirectional"))
    )
    (net (code "177") (name "Net-(U$85-CO)") (class "Default")
      (node (ref "U$85") (pin "CL_OUT") (pinfunction "CO_CL_OUT") (pintype "bidirectional"))
      (node (ref "U$86") (pin "C_IN") (pinfunction "CI_C_IN") (pintype "bidirectional"))
    )
    (net (code "178") (name "Net-(U$85-DO)") (class "Default")
      (node (ref "U$85") (pin "D_OUT") (pinfunction "DO_D_OUT") (pintype "bidirectional"))
      (node (ref "U$86") (pin "D_IN") (pinfunction "DI_D_IN") (pintype "bidirectional"))
    )
    (net (code "179") (name "Net-(U$86-CO)") (class "Default")
      (node (ref "U$86") (pin "CL_OUT") (pinfunction "CO_CL_OUT") (pintype "bidirectional"))
      (node (ref "U$87") (pin "C_IN") (pinfunction "CI_C_IN") (pintype "bidirectional"))
    )
    (net (code "180") (name "Net-(U$86-DO)") (class "Default")
      (node (ref "U$86") (pin "D_OUT") (pinfunction "DO_D_OUT") (pintype "bidirectional"))
      (node (ref "U$87") (pin "D_IN") (pinfunction "DI_D_IN") (pintype "bidirectional"))
    )
    (net (code "181") (name "Net-(U$87-CO)") (class "Default")
      (node (ref "U$87") (pin "CL_OUT") (pinfunction "CO_CL_OUT") (pintype "bidirectional"))
      (node (ref "U$88") (pin "C_IN") (pinfunction "CI_C_IN") (pintype "bidirectional"))
    )
    (net (code "182") (name "Net-(U$87-DO)") (class "Default")
      (node (ref "U$87") (pin "D_OUT") (pinfunction "DO_D_OUT") (pintype "bidirectional"))
      (node (ref "U$88") (pin "D_IN") (pinfunction "DI_D_IN") (pintype "bidirectional"))
    )
    (net (code "183") (name "Net-(U$88-CO)") (class "Default")
      (node (ref "U$88") (pin "CL_OUT") (pinfunction "CO_CL_OUT") (pintype "bidirectional"))
      (node (ref "U$89") (pin "C_IN") (pinfunction "CI_C_IN") (pintype "bidirectional"))
    )
    (net (code "184") (name "Net-(U$88-DO)") (class "Default")
      (node (ref "U$88") (pin "D_OUT") (pinfunction "DO_D_OUT") (pintype "bidirectional"))
      (node (ref "U$89") (pin "D_IN") (pinfunction "DI_D_IN") (pintype "bidirectional"))
    )
    (net (code "185") (name "Net-(U$89-CO)") (class "Default")
      (node (ref "U$89") (pin "CL_OUT") (pinfunction "CO_CL_OUT") (pintype "bidirectional"))
      (node (ref "U$90") (pin "C_IN") (pinfunction "CI_C_IN") (pintype "bidirectional"))
    )
    (net (code "186") (name "Net-(U$89-DO)") (class "Default")
      (node (ref "U$89") (pin "D_OUT") (pinfunction "DO_D_OUT") (pintype "bidirectional"))
      (node (ref "U$90") (pin "D_IN") (pinfunction "DI_D_IN") (pintype "bidirectional"))
    )
    (net (code "187") (name "Net-(U$90-CO)") (class "Default")
      (node (ref "U$90") (pin "CL_OUT") (pinfunction "CO_CL_OUT") (pintype "bidirectional"))
      (node (ref "U$91") (pin "C_IN") (pinfunction "CI_C_IN") (pintype "bidirectional"))
    )
    (net (code "188") (name "Net-(U$90-DO)") (class "Default")
      (node (ref "U$90") (pin "D_OUT") (pinfunction "DO_D_OUT") (pintype "bidirectional"))
      (node (ref "U$91") (pin "D_IN") (pinfunction "DI_D_IN") (pintype "bidirectional"))
    )
    (net (code "189") (name "Net-(U$91-CO)") (class "Default")
      (node (ref "U$91") (pin "CL_OUT") (pinfunction "CO_CL_OUT") (pintype "bidirectional"))
      (node (ref "U$92") (pin "C_IN") (pinfunction "CI_C_IN") (pintype "bidirectional"))
    )
    (net (code "190") (name "Net-(U$91-DO)") (class "Default")
      (node (ref "U$91") (pin "D_OUT") (pinfunction "DO_D_OUT") (pintype "bidirectional"))
      (node (ref "U$92") (pin "D_IN") (pinfunction "DI_D_IN") (pintype "bidirectional"))
    )
    (net (code "191") (name "Net-(U$92-CO)") (class "Default")
      (node (ref "U$92") (pin "CL_OUT") (pinfunction "CO_CL_OUT") (pintype "bidirectional"))
      (node (ref "U$93") (pin "C_IN") (pinfunction "CI_C_IN") (pintype "bidirectional"))
    )
    (net (code "192") (name "Net-(U$92-DO)") (class "Default")
      (node (ref "U$92") (pin "D_OUT") (pinfunction "DO_D_OUT") (pintype "bidirectional"))
      (node (ref "U$93") (pin "D_IN") (pinfunction "DI_D_IN") (pintype "bidirectional"))
    )
    (net (code "193") (name "Net-(U$93-CO)") (class "Default")
      (node (ref "U$93") (pin "CL_OUT") (pinfunction "CO_CL_OUT") (pintype "bidirectional"))
      (node (ref "U$94") (pin "C_IN") (pinfunction "CI_C_IN") (pintype "bidirectional"))
    )
    (net (code "194") (name "Net-(U$93-DO)") (class "Default")
      (node (ref "U$93") (pin "D_OUT") (pinfunction "DO_D_OUT") (pintype "bidirectional"))
      (node (ref "U$94") (pin "D_IN") (pinfunction "DI_D_IN") (pintype "bidirectional"))
    )
    (net (code "195") (name "Net-(U$94-CO)") (class "Default")
      (node (ref "U$94") (pin "CL_OUT") (pinfunction "CO_CL_OUT") (pintype "bidirectional"))
      (node (ref "U$95") (pin "C_IN") (pinfunction "CI_C_IN") (pintype "bidirectional"))
    )
    (net (code "196") (name "Net-(U$94-DO)") (class "Default")
      (node (ref "U$94") (pin "D_OUT") (pinfunction "DO_D_OUT") (pintype "bidirectional"))
      (node (ref "U$95") (pin "D_IN") (pinfunction "DI_D_IN") (pintype "bidirectional"))
    )
    (net (code "197") (name "Net-(U$95-CO)") (class "Default")
      (node (ref "U$95") (pin "CL_OUT") (pinfunction "CO_CL_OUT") (pintype "bidirectional"))
      (node (ref "U$96") (pin "C_IN") (pinfunction "CI_C_IN") (pintype "bidirectional"))
    )
    (net (code "198") (name "Net-(U$95-DO)") (class "Default")
      (node (ref "U$95") (pin "D_OUT") (pinfunction "DO_D_OUT") (pintype "bidirectional"))
      (node (ref "U$96") (pin "D_IN") (pinfunction "DI_D_IN") (pintype "bidirectional"))
    )
    (net (code "199") (name "Net-(U$96-CO)") (class "Default")
      (node (ref "U$96") (pin "CL_OUT") (pinfunction "CO_CL_OUT") (pintype "bidirectional"))
      (node (ref "U$97") (pin "C_IN") (pinfunction "CI_C_IN") (pintype "bidirectional"))
    )
    (net (code "200") (name "Net-(U$96-DO)") (class "Default")
      (node (ref "U$96") (pin "D_OUT") (pinfunction "DO_D_OUT") (pintype "bidirectional"))
      (node (ref "U$97") (pin "D_IN") (pinfunction "DI_D_IN") (pintype "bidirectional"))
    )
    (net (code "201") (name "Net-(U$97-CO)") (class "Default")
      (node (ref "U$97") (pin "CL_OUT") (pinfunction "CO_CL_OUT") (pintype "bidirectional"))
      (node (ref "U$98") (pin "C_IN") (pinfunction "CI_C_IN") (pintype "bidirectional"))
    )
    (net (code "202") (name "Net-(U$97-DO)") (class "Default")
      (node (ref "U$97") (pin "D_OUT") (pinfunction "DO_D_OUT") (pintype "bidirectional"))
      (node (ref "U$98") (pin "D_IN") (pinfunction "DI_D_IN") (pintype "bidirectional"))
    )
    (net (code "203") (name "Net-(U$98-CO)") (class "Default")
      (node (ref "U$98") (pin "CL_OUT") (pinfunction "CO_CL_OUT") (pintype "bidirectional"))
      (node (ref "U$99") (pin "C_IN") (pinfunction "CI_C_IN") (pintype "bidirectional"))
    )
    (net (code "204") (name "Net-(U$98-DO)") (class "Default")
      (node (ref "U$98") (pin "D_OUT") (pinfunction "DO_D_OUT") (pintype "bidirectional"))
      (node (ref "U$99") (pin "D_IN") (pinfunction "DI_D_IN") (pintype "bidirectional"))
    )
    (net (code "205") (name "Net-(U$100-CI)") (class "Default")
      (node (ref "U$100") (pin "C_IN") (pinfunction "CI_C_IN") (pintype "bidirectional"))
      (node (ref "U$99") (pin "CL_OUT") (pinfunction "CO_CL_OUT") (pintype "bidirectional"))
    )
    (net (code "206") (name "Net-(U$100-CO)") (class "Default")
      (node (ref "U$100") (pin "CL_OUT") (pinfunction "CO_CL_OUT") (pintype "bidirectional"))
      (node (ref "U$101") (pin "C_IN") (pinfunction "CI_C_IN") (pintype "bidirectional"))
    )
    (net (code "207") (name "Net-(U$100-DI)") (class "Default")
      (node (ref "U$100") (pin "D_IN") (pinfunction "DI_D_IN") (pintype "bidirectional"))
      (node (ref "U$99") (pin "D_OUT") (pinfunction "DO_D_OUT") (pintype "bidirectional"))
    )
    (net (code "208") (name "Net-(U$100-DO)") (class "Default")
      (node (ref "U$100") (pin "D_OUT") (pinfunction "DO_D_OUT") (pintype "bidirectional"))
      (node (ref "U$101") (pin "D_IN") (pinfunction "DI_D_IN") (pintype "bidirectional"))
    )
    (net (code "209") (name "Net-(U$101-CO)") (class "Default")
      (node (ref "U$101") (pin "CL_OUT") (pinfunction "CO_CL_OUT") (pintype "bidirectional"))
      (node (ref "U$102") (pin "C_IN") (pinfunction "CI_C_IN") (pintype "bidirectional"))
    )
    (net (code "210") (name "Net-(U$101-DO)") (class "Default")
      (node (ref "U$101") (pin "D_OUT") (pinfunction "DO_D_OUT") (pintype "bidirectional"))
      (node (ref "U$102") (pin "D_IN") (pinfunction "DI_D_IN") (pintype "bidirectional"))
    )
    (net (code "211") (name "Net-(U$102-CO)") (class "Default")
      (node (ref "U$102") (pin "CL_OUT") (pinfunction "CO_CL_OUT") (pintype "bidirectional"))
      (node (ref "U$103") (pin "C_IN") (pinfunction "CI_C_IN") (pintype "bidirectional"))
    )
    (net (code "212") (name "Net-(U$102-DO)") (class "Default")
      (node (ref "U$102") (pin "D_OUT") (pinfunction "DO_D_OUT") (pintype "bidirectional"))
      (node (ref "U$103") (pin "D_IN") (pinfunction "DI_D_IN") (pintype "bidirectional"))
    )
    (net (code "213") (name "Net-(U$103-CO)") (class "Default")
      (node (ref "U$103") (pin "CL_OUT") (pinfunction "CO_CL_OUT") (pintype "bidirectional"))
      (node (ref "U$105") (pin "C_IN") (pinfunction "CI_C_IN") (pintype "bidirectional"))
    )
    (net (code "214") (name "Net-(U$103-DO)") (class "Default")
      (node (ref "U$103") (pin "D_OUT") (pinfunction "DO_D_OUT") (pintype "bidirectional"))
      (node (ref "U$105") (pin "D_IN") (pinfunction "DI_D_IN") (pintype "bidirectional"))
    )
    (net (code "215") (name "Net-(U$104-CI)") (class "Default")
      (node (ref "U$104") (pin "C_IN") (pinfunction "CI_C_IN") (pintype "bidirectional"))
      (node (ref "U$130") (pin "CL_OUT") (pinfunction "CO_CL_OUT") (pintype "bidirectional"))
    )
    (net (code "216") (name "Net-(U$104-CO)") (class "Default")
      (node (ref "U$104") (pin "CL_OUT") (pinfunction "CO_CL_OUT") (pintype "bidirectional"))
      (node (ref "U$119") (pin "C_IN") (pinfunction "CI_C_IN") (pintype "bidirectional"))
    )
    (net (code "217") (name "Net-(U$104-DI)") (class "Default")
      (node (ref "U$104") (pin "D_IN") (pinfunction "DI_D_IN") (pintype "bidirectional"))
      (node (ref "U$130") (pin "D_OUT") (pinfunction "DO_D_OUT") (pintype "bidirectional"))
    )
    (net (code "218") (name "Net-(U$104-DO)") (class "Default")
      (node (ref "U$104") (pin "D_OUT") (pinfunction "DO_D_OUT") (pintype "bidirectional"))
      (node (ref "U$119") (pin "D_IN") (pinfunction "DI_D_IN") (pintype "bidirectional"))
    )
    (net (code "219") (name "Net-(U$105-CO)") (class "Default")
      (node (ref "U$105") (pin "CL_OUT") (pinfunction "CO_CL_OUT") (pintype "bidirectional"))
      (node (ref "U$106") (pin "C_IN") (pinfunction "CI_C_IN") (pintype "bidirectional"))
    )
    (net (code "220") (name "Net-(U$105-DO)") (class "Default")
      (node (ref "U$105") (pin "D_OUT") (pinfunction "DO_D_OUT") (pintype "bidirectional"))
      (node (ref "U$106") (pin "D_IN") (pinfunction "DI_D_IN") (pintype "bidirectional"))
    )
    (net (code "221") (name "Net-(U$106-CO)") (class "Default")
      (node (ref "U$106") (pin "CL_OUT") (pinfunction "CO_CL_OUT") (pintype "bidirectional"))
      (node (ref "U$107") (pin "C_IN") (pinfunction "CI_C_IN") (pintype "bidirectional"))
    )
    (net (code "222") (name "Net-(U$106-DO)") (class "Default")
      (node (ref "U$106") (pin "D_OUT") (pinfunction "DO_D_OUT") (pintype "bidirectional"))
      (node (ref "U$107") (pin "D_IN") (pinfunction "DI_D_IN") (pintype "bidirectional"))
    )
    (net (code "223") (name "Net-(U$107-CO)") (class "Default")
      (node (ref "U$107") (pin "CL_OUT") (pinfunction "CO_CL_OUT") (pintype "bidirectional"))
      (node (ref "U$108") (pin "C_IN") (pinfunction "CI_C_IN") (pintype "bidirectional"))
    )
    (net (code "224") (name "Net-(U$107-DO)") (class "Default")
      (node (ref "U$107") (pin "D_OUT") (pinfunction "DO_D_OUT") (pintype "bidirectional"))
      (node (ref "U$108") (pin "D_IN") (pinfunction "DI_D_IN") (pintype "bidirectional"))
    )
    (net (code "225") (name "Net-(U$108-CO)") (class "Default")
      (node (ref "U$108") (pin "CL_OUT") (pinfunction "CO_CL_OUT") (pintype "bidirectional"))
      (node (ref "U$109") (pin "C_IN") (pinfunction "CI_C_IN") (pintype "bidirectional"))
    )
    (net (code "226") (name "Net-(U$108-DO)") (class "Default")
      (node (ref "U$108") (pin "D_OUT") (pinfunction "DO_D_OUT") (pintype "bidirectional"))
      (node (ref "U$109") (pin "D_IN") (pinfunction "DI_D_IN") (pintype "bidirectional"))
    )
    (net (code "227") (name "Net-(U$109-CO)") (class "Default")
      (node (ref "U$109") (pin "CL_OUT") (pinfunction "CO_CL_OUT") (pintype "bidirectional"))
      (node (ref "U$110") (pin "C_IN") (pinfunction "CI_C_IN") (pintype "bidirectional"))
    )
    (net (code "228") (name "Net-(U$109-DO)") (class "Default")
      (node (ref "U$109") (pin "D_OUT") (pinfunction "DO_D_OUT") (pintype "bidirectional"))
      (node (ref "U$110") (pin "D_IN") (pinfunction "DI_D_IN") (pintype "bidirectional"))
    )
    (net (code "229") (name "Net-(U$110-CO)") (class "Default")
      (node (ref "U$110") (pin "CL_OUT") (pinfunction "CO_CL_OUT") (pintype "bidirectional"))
      (node (ref "U$111") (pin "C_IN") (pinfunction "CI_C_IN") (pintype "bidirectional"))
    )
    (net (code "230") (name "Net-(U$110-DO)") (class "Default")
      (node (ref "U$110") (pin "D_OUT") (pinfunction "DO_D_OUT") (pintype "bidirectional"))
      (node (ref "U$111") (pin "D_IN") (pinfunction "DI_D_IN") (pintype "bidirectional"))
    )
    (net (code "231") (name "Net-(U$111-CO)") (class "Default")
      (node (ref "U$111") (pin "CL_OUT") (pinfunction "CO_CL_OUT") (pintype "bidirectional"))
      (node (ref "U$112") (pin "C_IN") (pinfunction "CI_C_IN") (pintype "bidirectional"))
    )
    (net (code "232") (name "Net-(U$111-DO)") (class "Default")
      (node (ref "U$111") (pin "D_OUT") (pinfunction "DO_D_OUT") (pintype "bidirectional"))
      (node (ref "U$112") (pin "D_IN") (pinfunction "DI_D_IN") (pintype "bidirectional"))
    )
    (net (code "233") (name "Net-(U$112-CO)") (class "Default")
      (node (ref "U$112") (pin "CL_OUT") (pinfunction "CO_CL_OUT") (pintype "bidirectional"))
      (node (ref "U$113") (pin "C_IN") (pinfunction "CI_C_IN") (pintype "bidirectional"))
    )
    (net (code "234") (name "Net-(U$112-DO)") (class "Default")
      (node (ref "U$112") (pin "D_OUT") (pinfunction "DO_D_OUT") (pintype "bidirectional"))
      (node (ref "U$113") (pin "D_IN") (pinfunction "DI_D_IN") (pintype "bidirectional"))
    )
    (net (code "235") (name "Net-(U$113-CO)") (class "Default")
      (node (ref "U$113") (pin "CL_OUT") (pinfunction "CO_CL_OUT") (pintype "bidirectional"))
      (node (ref "U$114") (pin "C_IN") (pinfunction "CI_C_IN") (pintype "bidirectional"))
    )
    (net (code "236") (name "Net-(U$113-DO)") (class "Default")
      (node (ref "U$113") (pin "D_OUT") (pinfunction "DO_D_OUT") (pintype "bidirectional"))
      (node (ref "U$114") (pin "D_IN") (pinfunction "DI_D_IN") (pintype "bidirectional"))
    )
    (net (code "237") (name "Net-(U$114-CO)") (class "Default")
      (node (ref "U$114") (pin "CL_OUT") (pinfunction "CO_CL_OUT") (pintype "bidirectional"))
      (node (ref "U$115") (pin "C_IN") (pinfunction "CI_C_IN") (pintype "bidirectional"))
    )
    (net (code "238") (name "Net-(U$114-DO)") (class "Default")
      (node (ref "U$114") (pin "D_OUT") (pinfunction "DO_D_OUT") (pintype "bidirectional"))
      (node (ref "U$115") (pin "D_IN") (pinfunction "DI_D_IN") (pintype "bidirectional"))
    )
    (net (code "239") (name "Net-(U$115-CO)") (class "Default")
      (node (ref "U$115") (pin "CL_OUT") (pinfunction "CO_CL_OUT") (pintype "bidirectional"))
      (node (ref "U$116") (pin "C_IN") (pinfunction "CI_C_IN") (pintype "bidirectional"))
    )
    (net (code "240") (name "Net-(U$115-DO)") (class "Default")
      (node (ref "U$115") (pin "D_OUT") (pinfunction "DO_D_OUT") (pintype "bidirectional"))
      (node (ref "U$116") (pin "D_IN") (pinfunction "DI_D_IN") (pintype "bidirectional"))
    )
    (net (code "241") (name "Net-(U$116-CO)") (class "Default")
      (node (ref "U$116") (pin "CL_OUT") (pinfunction "CO_CL_OUT") (pintype "bidirectional"))
      (node (ref "U$117") (pin "C_IN") (pinfunction "CI_C_IN") (pintype "bidirectional"))
    )
    (net (code "242") (name "Net-(U$116-DO)") (class "Default")
      (node (ref "U$116") (pin "D_OUT") (pinfunction "DO_D_OUT") (pintype "bidirectional"))
      (node (ref "U$117") (pin "D_IN") (pinfunction "DI_D_IN") (pintype "bidirectional"))
    )
    (net (code "243") (name "Net-(U$117-CO)") (class "Default")
      (node (ref "U$117") (pin "CL_OUT") (pinfunction "CO_CL_OUT") (pintype "bidirectional"))
      (node (ref "U$118") (pin "C_IN") (pinfunction "CI_C_IN") (pintype "bidirectional"))
    )
    (net (code "244") (name "Net-(U$117-DO)") (class "Default")
      (node (ref "U$117") (pin "D_OUT") (pinfunction "DO_D_OUT") (pintype "bidirectional"))
      (node (ref "U$118") (pin "D_IN") (pinfunction "DI_D_IN") (pintype "bidirectional"))
    )
    (net (code "245") (name "Net-(U$119-CO)") (class "Default")
      (node (ref "U$119") (pin "CL_OUT") (pinfunction "CO_CL_OUT") (pintype "bidirectional"))
      (node (ref "U$120") (pin "C_IN") (pinfunction "CI_C_IN") (pintype "bidirectional"))
    )
    (net (code "246") (name "Net-(U$119-DO)") (class "Default")
      (node (ref "U$119") (pin "D_OUT") (pinfunction "DO_D_OUT") (pintype "bidirectional"))
      (node (ref "U$120") (pin "D_IN") (pinfunction "DI_D_IN") (pintype "bidirectional"))
    )
    (net (code "247") (name "Net-(U$120-CO)") (class "Default")
      (node (ref "U$120") (pin "CL_OUT") (pinfunction "CO_CL_OUT") (pintype "bidirectional"))
      (node (ref "U$121") (pin "C_IN") (pinfunction "CI_C_IN") (pintype "bidirectional"))
    )
    (net (code "248") (name "Net-(U$120-DO)") (class "Default")
      (node (ref "U$120") (pin "D_OUT") (pinfunction "DO_D_OUT") (pintype "bidirectional"))
      (node (ref "U$121") (pin "D_IN") (pinfunction "DI_D_IN") (pintype "bidirectional"))
    )
    (net (code "249") (name "Net-(U$121-CO)") (class "Default")
      (node (ref "U$121") (pin "CL_OUT") (pinfunction "CO_CL_OUT") (pintype "bidirectional"))
      (node (ref "U$122") (pin "C_IN") (pinfunction "CI_C_IN") (pintype "bidirectional"))
    )
    (net (code "250") (name "Net-(U$121-DO)") (class "Default")
      (node (ref "U$121") (pin "D_OUT") (pinfunction "DO_D_OUT") (pintype "bidirectional"))
      (node (ref "U$122") (pin "D_IN") (pinfunction "DI_D_IN") (pintype "bidirectional"))
    )
    (net (code "251") (name "Net-(U$122-CO)") (class "Default")
      (node (ref "U$122") (pin "CL_OUT") (pinfunction "CO_CL_OUT") (pintype "bidirectional"))
      (node (ref "U$123") (pin "C_IN") (pinfunction "CI_C_IN") (pintype "bidirectional"))
    )
    (net (code "252") (name "Net-(U$122-DO)") (class "Default")
      (node (ref "U$122") (pin "D_OUT") (pinfunction "DO_D_OUT") (pintype "bidirectional"))
      (node (ref "U$123") (pin "D_IN") (pinfunction "DI_D_IN") (pintype "bidirectional"))
    )
    (net (code "253") (name "Net-(U$123-CO)") (class "Default")
      (node (ref "U$123") (pin "CL_OUT") (pinfunction "CO_CL_OUT") (pintype "bidirectional"))
      (node (ref "U$124") (pin "C_IN") (pinfunction "CI_C_IN") (pintype "bidirectional"))
    )
    (net (code "254") (name "Net-(U$123-DO)") (class "Default")
      (node (ref "U$123") (pin "D_OUT") (pinfunction "DO_D_OUT") (pintype "bidirectional"))
      (node (ref "U$124") (pin "D_IN") (pinfunction "DI_D_IN") (pintype "bidirectional"))
    )
    (net (code "255") (name "Net-(U$124-CO)") (class "Default")
      (node (ref "U$124") (pin "CL_OUT") (pinfunction "CO_CL_OUT") (pintype "bidirectional"))
      (node (ref "U$125") (pin "C_IN") (pinfunction "CI_C_IN") (pintype "bidirectional"))
    )
    (net (code "256") (name "Net-(U$124-DO)") (class "Default")
      (node (ref "U$124") (pin "D_OUT") (pinfunction "DO_D_OUT") (pintype "bidirectional"))
      (node (ref "U$125") (pin "D_IN") (pinfunction "DI_D_IN") (pintype "bidirectional"))
    )
    (net (code "257") (name "Net-(U$125-CO)") (class "Default")
      (node (ref "U$125") (pin "CL_OUT") (pinfunction "CO_CL_OUT") (pintype "bidirectional"))
      (node (ref "U$126") (pin "C_IN") (pinfunction "CI_C_IN") (pintype "bidirectional"))
    )
    (net (code "258") (name "Net-(U$125-DO)") (class "Default")
      (node (ref "U$125") (pin "D_OUT") (pinfunction "DO_D_OUT") (pintype "bidirectional"))
      (node (ref "U$126") (pin "D_IN") (pinfunction "DI_D_IN") (pintype "bidirectional"))
    )
    (net (code "259") (name "Net-(U$126-CO)") (class "Default")
      (node (ref "U$126") (pin "CL_OUT") (pinfunction "CO_CL_OUT") (pintype "bidirectional"))
      (node (ref "U$127") (pin "C_IN") (pinfunction "CI_C_IN") (pintype "bidirectional"))
    )
    (net (code "260") (name "Net-(U$126-DO)") (class "Default")
      (node (ref "U$126") (pin "D_OUT") (pinfunction "DO_D_OUT") (pintype "bidirectional"))
      (node (ref "U$127") (pin "D_IN") (pinfunction "DI_D_IN") (pintype "bidirectional"))
    )
    (net (code "261") (name "Net-(U$127-CO)") (class "Default")
      (node (ref "U$127") (pin "CL_OUT") (pinfunction "CO_CL_OUT") (pintype "bidirectional"))
      (node (ref "U$128") (pin "C_IN") (pinfunction "CI_C_IN") (pintype "bidirectional"))
    )
    (net (code "262") (name "Net-(U$127-DO)") (class "Default")
      (node (ref "U$127") (pin "D_OUT") (pinfunction "DO_D_OUT") (pintype "bidirectional"))
      (node (ref "U$128") (pin "D_IN") (pinfunction "DI_D_IN") (pintype "bidirectional"))
    )
    (net (code "263") (name "Net-(U$128-CO)") (class "Default")
      (node (ref "U$128") (pin "CL_OUT") (pinfunction "CO_CL_OUT") (pintype "bidirectional"))
      (node (ref "U$129") (pin "C_IN") (pinfunction "CI_C_IN") (pintype "bidirectional"))
    )
    (net (code "264") (name "Net-(U$128-DO)") (class "Default")
      (node (ref "U$128") (pin "D_OUT") (pinfunction "DO_D_OUT") (pintype "bidirectional"))
      (node (ref "U$129") (pin "D_IN") (pinfunction "DI_D_IN") (pintype "bidirectional"))
    )
    (net (code "265") (name "Net-(U$129-CO)") (class "Default")
      (node (ref "U$129") (pin "CL_OUT") (pinfunction "CO_CL_OUT") (pintype "bidirectional"))
      (node (ref "U$32") (pin "C_IN") (pinfunction "CI_C_IN") (pintype "bidirectional"))
    )
    (net (code "266") (name "Net-(U$129-DO)") (class "Default")
      (node (ref "U$129") (pin "D_OUT") (pinfunction "DO_D_OUT") (pintype "bidirectional"))
      (node (ref "U$32") (pin "D_IN") (pinfunction "DI_D_IN") (pintype "bidirectional"))
    )
    (net (code "267") (name "Net-(U$130-CI)") (class "Default")
      (node (ref "U$130") (pin "C_IN") (pinfunction "CI_C_IN") (pintype "bidirectional"))
      (node (ref "U$31") (pin "CL_OUT") (pinfunction "CO_CL_OUT") (pintype "bidirectional"))
    )
    (net (code "268") (name "Net-(U$130-DI)") (class "Default")
      (node (ref "U$130") (pin "D_IN") (pinfunction "DI_D_IN") (pintype "bidirectional"))
      (node (ref "U$31") (pin "D_OUT") (pinfunction "DO_D_OUT") (pintype "bidirectional"))
    )
    (net (code "269") (name "Net-(U$131-CAPN)") (class "Default")
      (node (ref "C20") (pin "2") (pinfunction "2_2") (pintype "passive"))
      (node (ref "U$131") (pin "10") (pinfunction "CAPN_10") (pintype "bidirectional"))
    )
    (net (code "270") (name "Net-(U$131-CAPP)") (class "Default")
      (node (ref "C20") (pin "1") (pinfunction "1_1") (pintype "passive"))
      (node (ref "U$131") (pin "9") (pinfunction "CAPP_9") (pintype "bidirectional"))
    )
    (net (code "271") (name "Net-(U$131-CPLL)") (class "Default")
      (node (ref "C68") (pin "1") (pinfunction "1_1") (pintype "passive"))
      (node (ref "U$131") (pin "11") (pinfunction "CPLL_11") (pintype "bidirectional"))
    )
    (net (code "272") (name "Net-(U$131-VBG)") (class "Default")
      (node (ref "C73") (pin "1") (pinfunction "1_1") (pintype "passive"))
      (node (ref "U$131") (pin "27") (pinfunction "VBG_27") (pintype "bidirectional"))
    )
    (net (code "273") (name "Net-(U$131-VCM)") (class "Default")
      (node (ref "C71") (pin "1") (pinfunction "1_1") (pintype "passive"))
      (node (ref "U$131") (pin "25") (pinfunction "VCM_25") (pintype "bidirectional"))
    )
    (net (code "274") (name "Net-(U$131-VREF)") (class "Default")
      (node (ref "C70") (pin "1") (pinfunction "1_1") (pintype "passive"))
      (node (ref "U$131") (pin "23") (pinfunction "VREF_23") (pintype "bidirectional"))
    )
    (net (code "275") (name "Net-(U1-USBDM)") (class "Default")
      (node (ref "R14") (pin "2") (pinfunction "2_2") (pintype "passive"))
      (node (ref "U1") (pin "12") (pinfunction "USBDM_12") (pintype "bidirectional"))
    )
    (net (code "276") (name "Net-(U1-USBDP)") (class "Default")
      (node (ref "R15") (pin "2") (pinfunction "2_2") (pintype "passive"))
      (node (ref "U1") (pin "11") (pinfunction "USBDP_11") (pintype "bidirectional"))
    )
    (net (code "277") (name "Net-(U3-PROG)") (class "Default")
      (node (ref "R17") (pin "2") (pinfunction "2_2") (pintype "passive"))
      (node (ref "U3") (pin "5") (pinfunction "PROG_5") (pintype "input"))
    )
    (net (code "278") (name "Net-(U3-STAT)") (class "Default")
      (node (ref "CHG2") (pin "C") (pinfunction "C_C") (pintype "passive"))
      (node (ref "U3") (pin "1") (pinfunction "STAT_1") (pintype "output"))
    )
    (net (code "279") (name "RTS") (class "Default")
      (node (ref "Q1") (pin "4") (pinfunction "E_4") (pintype "passive"))
      (node (ref "R10") (pin "1") (pinfunction "1_1") (pintype "passive"))
      (node (ref "U1") (pin "2") (pinfunction "~{RTS}_2") (pintype "bidirectional"))
    )
    (net (code "280") (name "RXD") (class "Default")
      (node (ref "R13") (pin "2") (pinfunction "2_2") (pintype "passive"))
      (node (ref "U1") (pin "4") (pinfunction "RXD_4") (pintype "bidirectional"))
    )
    (net (code "281") (name "SCL") (class "Default")
      (node (ref "IC1") (pin "42") (pinfunction "IO21_42") (pintype "power_in"))
      (node (ref "R7") (pin "1") (pinfunction "1_1") (pintype "passive"))
      (node (ref "U2") (pin "13") (pinfunction "SCL_13") (pintype "bidirectional"))
    )
    (net (code "282") (name "SCLK") (class "Default")
      (node (ref "IC1") (pin "35") (pinfunction "IO18_35") (pintype "bidirectional"))
      (node (ref "U$131") (pin "16") (pinfunction "SCLK_16") (pintype "bidirectional"))
    )
    (net (code "283") (name "SDA") (class "Default")
      (node (ref "IC1") (pin "16") (pinfunction "IO27_16") (pintype "bidirectional"))
      (node (ref "R4") (pin "1") (pinfunction "1_1") (pintype "passive"))
      (node (ref "U2") (pin "14") (pinfunction "SDA_14") (pintype "bidirectional"))
    )
    (net (code "284") (name "SENSOR_CAPN") (class "Default")
      (node (ref "IC1") (pin "7") (pinfunction "SENSOR_CAPN_7") (pintype "power_in"))
    )
    (net (code "285") (name "TXD") (class "Default")
      (node (ref "R12") (pin "2") (pinfunction "2_2") (pintype "passive"))
      (node (ref "U1") (pin "20") (pinfunction "TXD_20") (pintype "bidirectional"))
    )
    (net (code "286") (name "U0RXD") (class "Default")
      (node (ref "IC1") (pin "40") (pinfunction "U0RXD_40") (pintype "bidirectional"))
      (node (ref "R12") (pin "1") (pinfunction "1_1") (pintype "passive"))
    )
    (net (code "287") (name "U0TXD") (class "Default")
      (node (ref "IC1") (pin "41") (pinfunction "U0TXD_41") (pintype "bidirectional"))
      (node (ref "R13") (pin "1") (pinfunction "1_1") (pintype "passive"))
    )
    (net (code "288") (name "VBAT") (class "Default")
      (node (ref "C65") (pin "1") (pinfunction "1_1") (pintype "passive"))
      (node (ref "Q2") (pin "3") (pinfunction "D_3") (pintype "passive"))
      (node (ref "R25") (pin "2") (pinfunction "2_2") (pintype "passive"))
      (node (ref "TP5") (pin "TP-1") (pinfunction "TP_TP-1") (pintype "input"))
      (node (ref "U3") (pin "3") (pinfunction "VBAT_3") (pintype "power_in"))
    )
    (net (code "289") (name "VIN") (class "Default")
      (node (ref "C63") (pin "1") (pinfunction "1_1") (pintype "passive"))
      (node (ref "C72") (pin "2") (pinfunction "2_2") (pintype "passive"))
      (node (ref "D1") (pin "C") (pinfunction "C_C") (pintype "passive"))
      (node (ref "Q2") (pin "2") (pinfunction "S_2") (pintype "passive"))
      (node (ref "S2") (pin "3") (pinfunction "S_3") (pintype "passive"))
      (node (ref "SJ1") (pin "2") (pinfunction "2_2") (pintype "passive"))
      (node (ref "U8") (pin "1") (pinfunction "IN_1") (pintype "input"))
    )
    (net (code "290") (name "VUSB") (class "Default")
      (node (ref "C60") (pin "1") (pinfunction "1_1") (pintype "passive"))
      (node (ref "C61") (pin "1") (pinfunction "1_1") (pintype "passive"))
      (node (ref "C64") (pin "1") (pinfunction "1_1") (pintype "passive"))
      (node (ref "D1") (pin "A") (pinfunction "A_A") (pintype "passive"))
      (node (ref "JP7") (pin "1") (pinfunction "VCC_1") (pintype "bidirectional"))
      (node (ref "Q2") (pin "1") (pinfunction "G_1") (pintype "passive"))
      (node (ref "R16") (pin "1") (pinfunction "1_1") (pintype "passive"))
      (node (ref "R23") (pin "2") (pinfunction "2_2") (pintype "passive"))
      (node (ref "U1") (pin "15") (pinfunction "VCC_15") (pintype "bidirectional"))
      (node (ref "U3") (pin "4") (pinfunction "VIN_4") (pintype "power_in"))
    )
    (net (code "291") (name "unconnected-(IC1A-CAP1_NC-Pad48)") (class "Default")
      (node (ref "IC1") (pin "48") (pinfunction "CAP1_NC_48") (pintype "bidirectional"))
    )
    (net (code "292") (name "unconnected-(IC1A-CAP2_NC-Pad47)") (class "Default")
      (node (ref "IC1") (pin "47") (pinfunction "CAP2_NC_47") (pintype "bidirectional"))
    )
    (net (code "293") (name "unconnected-(IC1A-CLK-Pad31)") (class "Default")
      (node (ref "IC1") (pin "31") (pinfunction "CLK_31") (pintype "bidirectional"))
    )
    (net (code "294") (name "unconnected-(IC1A-CMD-Pad30)") (class "Default")
      (node (ref "IC1") (pin "30") (pinfunction "CMD_30") (pintype "bidirectional"))
    )
    (net (code "295") (name "unconnected-(IC1A-IO2-Pad22)") (class "Default")
      (node (ref "IC1") (pin "22") (pinfunction "IO2_22") (pintype "bidirectional"))
    )
    (net (code "296") (name "unconnected-(IC1A-IO5-Pad34)") (class "Default")
      (node (ref "IC1") (pin "34") (pinfunction "IO5_34") (pintype "bidirectional"))
    )
    (net (code "297") (name "unconnected-(IC1A-IO13-Pad20)") (class "Default")
      (node (ref "IC1") (pin "20") (pinfunction "IO13_20") (pintype "bidirectional"))
    )
    (net (code "298") (name "unconnected-(IC1A-IO14-Pad17)") (class "Default")
      (node (ref "IC1") (pin "17") (pinfunction "IO14_17") (pintype "bidirectional"))
    )
    (net (code "299") (name "unconnected-(IC1A-IO15-Pad21)") (class "Default")
      (node (ref "IC1") (pin "21") (pinfunction "IO15_21") (pintype "bidirectional"))
    )
    (net (code "300") (name "unconnected-(IC1A-IO16-Pad25)") (class "Default")
      (node (ref "IC1") (pin "25") (pinfunction "IO16_25") (pintype "bidirectional"))
    )
    (net (code "301") (name "unconnected-(IC1A-IO17-Pad27)") (class "Default")
      (node (ref "IC1") (pin "27") (pinfunction "IO17_27") (pintype "bidirectional"))
    )
    (net (code "302") (name "unconnected-(IC1A-SD0-Pad32)") (class "Default")
      (node (ref "IC1") (pin "32") (pinfunction "SD0_32") (pintype "bidirectional"))
    )
    (net (code "303") (name "unconnected-(IC1A-SD1-Pad33)") (class "Default")
      (node (ref "IC1") (pin "33") (pinfunction "SD1_33") (pintype "bidirectional"))
    )
    (net (code "304") (name "unconnected-(IC1A-SD2-Pad28)") (class "Default")
      (node (ref "IC1") (pin "28") (pinfunction "SD2_28") (pintype "bidirectional"))
    )
    (net (code "305") (name "unconnected-(IC1A-SD3-Pad29)") (class "Default")
      (node (ref "IC1") (pin "29") (pinfunction "SD3_29") (pintype "bidirectional"))
    )
    (net (code "306") (name "unconnected-(IC1A-SENSOR_CAPP-Pad6)") (class "Default")
      (node (ref "IC1") (pin "6") (pinfunction "SENSOR_CAPP_6") (pintype "bidirectional"))
    )
    (net (code "307") (name "unconnected-(IC1A-SENSOR_VN-Pad8)") (class "Default")
      (node (ref "IC1") (pin "8") (pinfunction "SENSOR_VN_8") (pintype "bidirectional"))
    )
    (net (code "308") (name "unconnected-(IC1A-SENSOR_VP-Pad5)") (class "Default")
      (node (ref "IC1") (pin "5") (pinfunction "SENSOR_VP_5") (pintype "bidirectional"))
    )
    (net (code "309") (name "unconnected-(IC1A-XTAL_N_NC-Pad44)") (class "Default")
      (node (ref "IC1") (pin "44") (pinfunction "XTAL_N_NC_44") (pintype "bidirectional"))
    )
    (net (code "310") (name "unconnected-(IC1A-XTAL_P_NC-Pad45)") (class "Default")
      (node (ref "IC1") (pin "45") (pinfunction "XTAL_P_NC_45") (pintype "bidirectional"))
    )
    (net (code "311") (name "unconnected-(JP7-ID-Pad4)") (class "Default")
      (node (ref "JP7") (pin "4") (pinfunction "ID_4") (pintype "bidirectional"))
    )
    (net (code "312") (name "unconnected-(SW2-P1-PadA')") (class "Default")
      (node (ref "SW2") (pin "A'") (pinfunction "P1_A'") (pintype "passive"))
    )
    (net (code "313") (name "unconnected-(U$118-CO-PadCL_OUT)") (class "Default")
      (node (ref "U$118") (pin "CL_OUT") (pinfunction "CO_CL_OUT") (pintype "bidirectional"))
    )
    (net (code "314") (name "unconnected-(U$118-DO-PadD_OUT)") (class "Default")
      (node (ref "U$118") (pin "D_OUT") (pinfunction "DO_D_OUT") (pintype "bidirectional"))
    )
    (net (code "315") (name "unconnected-(U$131-INT2B-Pad20)") (class "Default")
      (node (ref "U$131") (pin "20") (pinfunction "INT2B_20") (pintype "bidirectional"))
    )
    (net (code "316") (name "unconnected-(U$134-NC-Pad1)") (class "Default")
      (node (ref "U$134") (pin "1") (pinfunction "NC_1") (pintype "bidirectional"))
    )
    (net (code "317") (name "unconnected-(U1-CBUS0-Pad18)") (class "Default")
      (node (ref "U1") (pin "18") (pinfunction "CBUS0_18") (pintype "bidirectional"))
    )
    (net (code "318") (name "unconnected-(U1-CBUS1-Pad17)") (class "Default")
      (node (ref "U1") (pin "17") (pinfunction "CBUS1_17") (pintype "bidirectional"))
    )
    (net (code "319") (name "unconnected-(U1-CBUS2-Pad10)") (class "Default")
      (node (ref "U1") (pin "10") (pinfunction "CBUS2_10") (pintype "bidirectional"))
    )
    (net (code "320") (name "unconnected-(U1-CBUS3-Pad19)") (class "Default")
      (node (ref "U1") (pin "19") (pinfunction "CBUS3_19") (pintype "bidirectional"))
    )
    (net (code "321") (name "unconnected-(U1-~{CTS}-Pad9)") (class "Default")
      (node (ref "U1") (pin "9") (pinfunction "~{CTS}_9") (pintype "bidirectional"))
    )
    (net (code "322") (name "unconnected-(U1-~{DCD}-Pad8)") (class "Default")
      (node (ref "U1") (pin "8") (pinfunction "~{DCD}_8") (pintype "bidirectional"))
    )
    (net (code "323") (name "unconnected-(U1-~{DSR}-Pad7)") (class "Default")
      (node (ref "U1") (pin "7") (pinfunction "~{DSR}_7") (pintype "bidirectional"))
    )
    (net (code "324") (name "unconnected-(U1-~{RI}-Pad5)") (class "Default")
      (node (ref "U1") (pin "5") (pinfunction "~{RI}_5") (pintype "bidirectional"))
    )
    (net (code "325") (name "unconnected-(U2-INT1-Pad4)") (class "Default")
      (node (ref "U2") (pin "4") (pinfunction "INT1_4") (pintype "bidirectional"))
    )
    (net (code "326") (name "unconnected-(U2-INT2-Pad9)") (class "Default")
      (node (ref "U2") (pin "9") (pinfunction "INT2_9") (pintype "bidirectional"))
    )
    (net (code "327") (name "unconnected-(U2-NC-Pad11)") (class "Default")
      (node (ref "U2") (pin "11") (pinfunction "NC_11") (pintype "bidirectional"))
    )
    (net (code "328") (name "unconnected-(U2-OCS-Pad10)") (class "Default")
      (node (ref "U2") (pin "10") (pinfunction "OCS_10") (pintype "bidirectional"))
    )
    (net (code "329") (name "unconnected-(U8-BP-Pad4)") (class "Default")
      (node (ref "U8") (pin "4") (pinfunction "BP_4") (pintype "input"))
    )
  )
)
